# Tommy.net
KiCad netlist of a schematic drawn in EAGLE
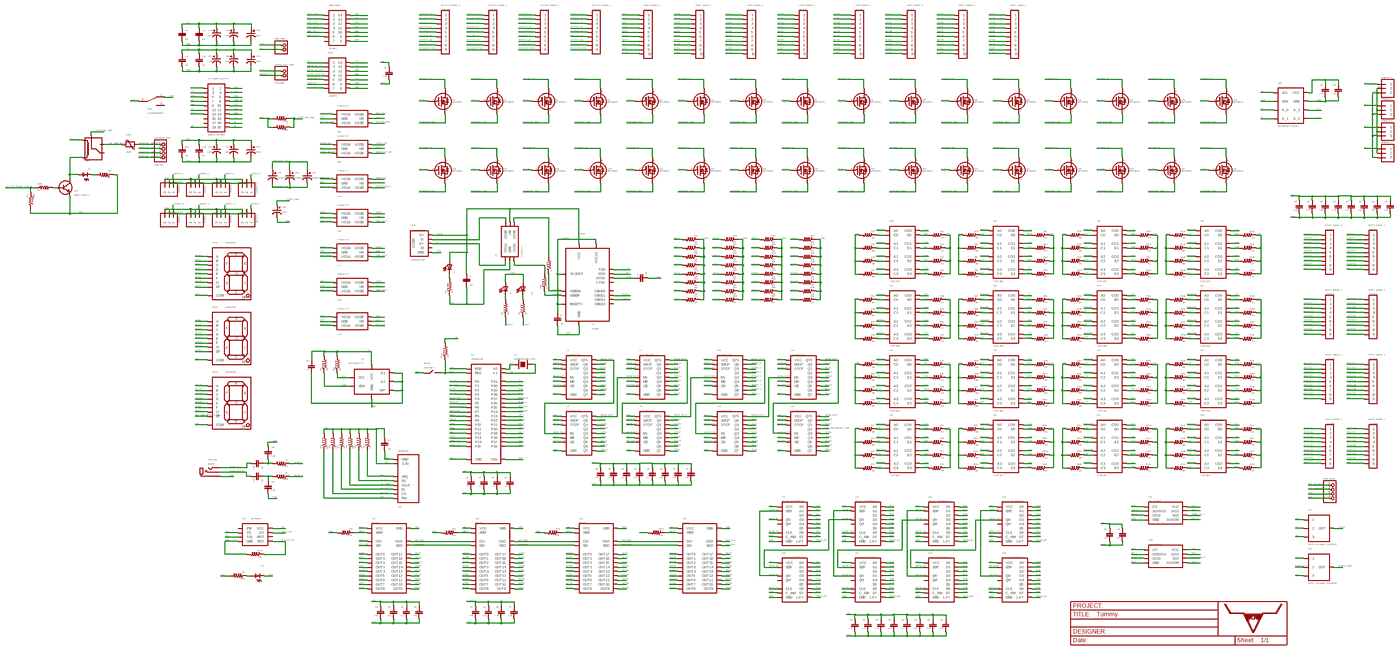
[diagram p0: schematic, sheet 1, overview]
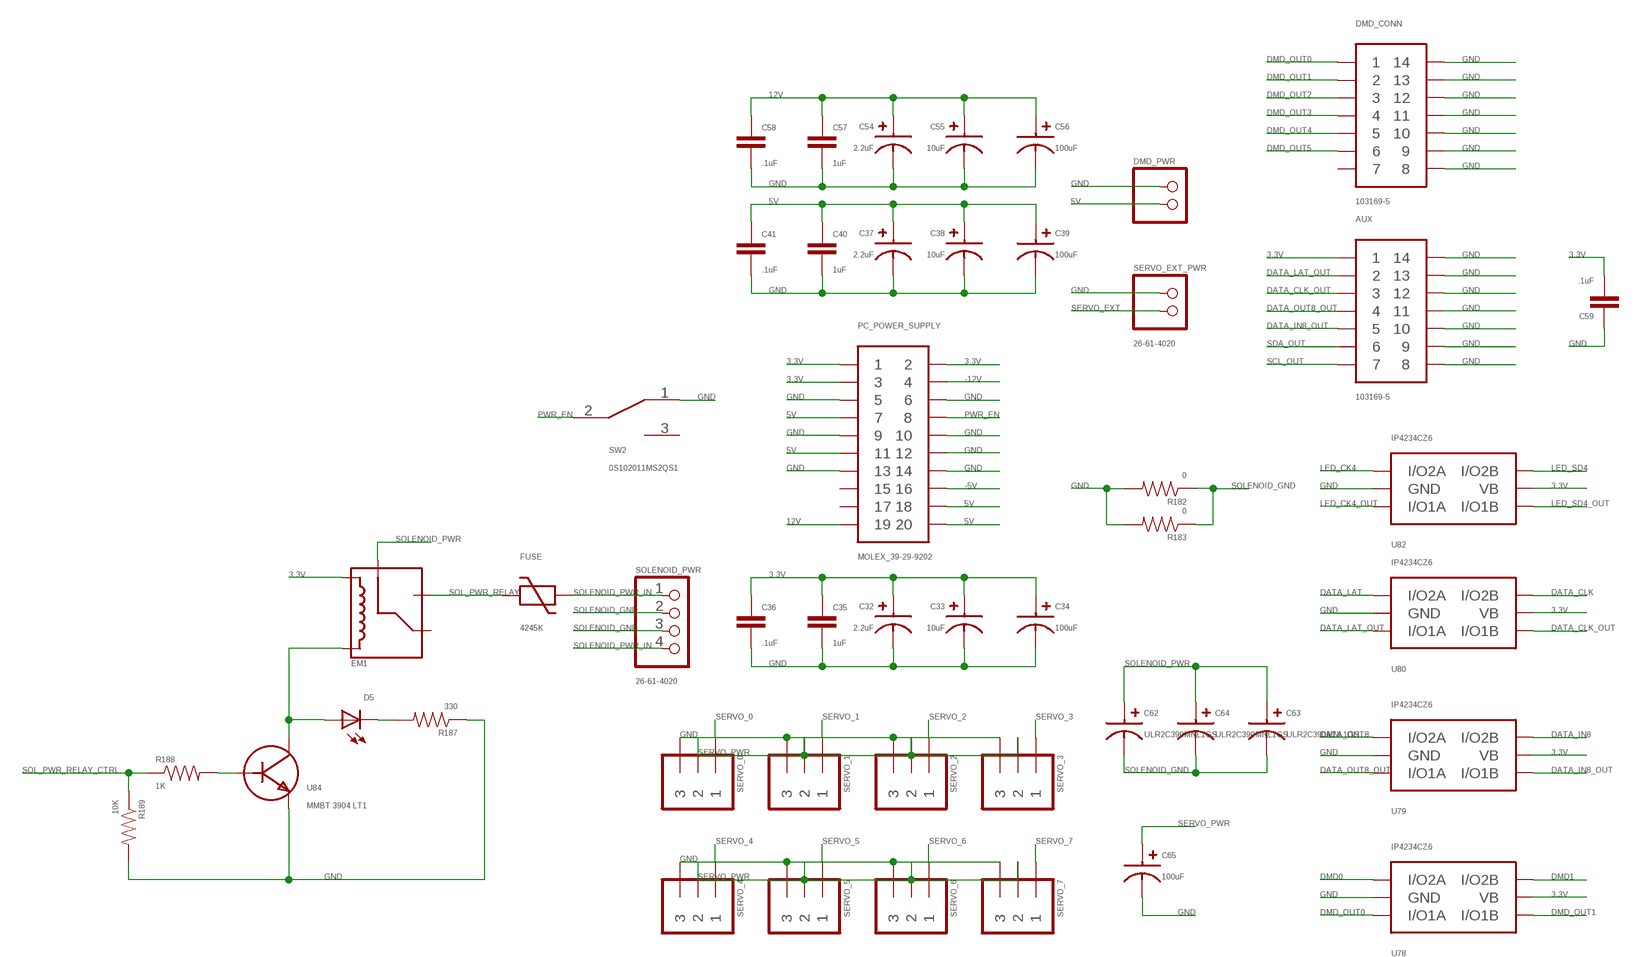
[diagram p1: schematic, sheet 1, part 1 of 9]
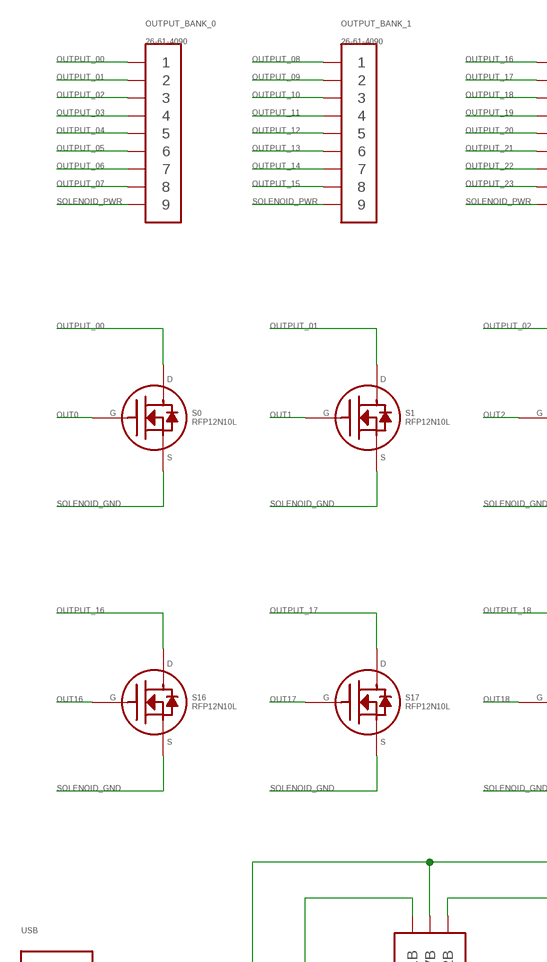
[diagram p2: schematic, sheet 1, part 2 of 9]
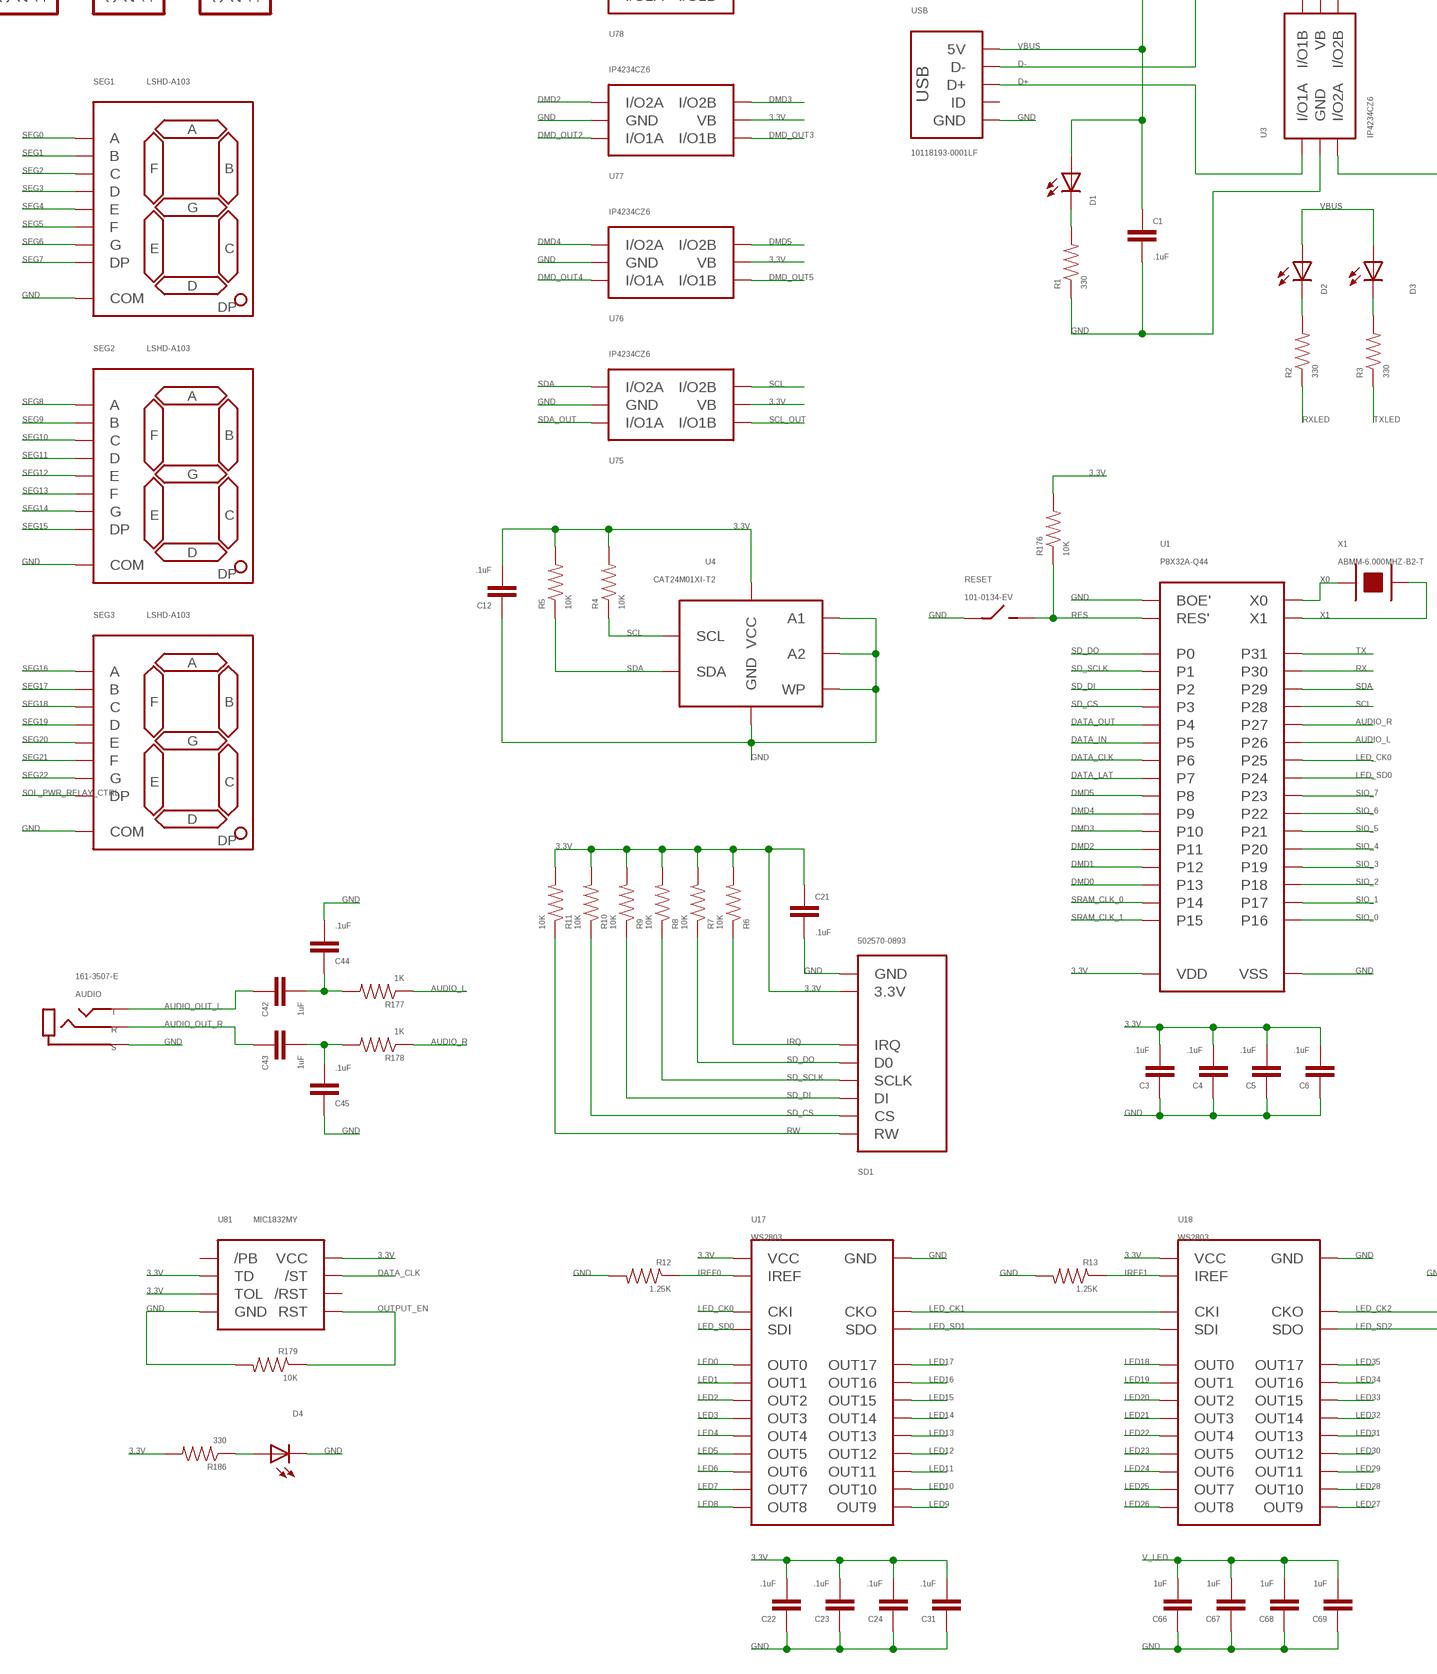
[diagram p3: schematic, sheet 1, part 3 of 9]
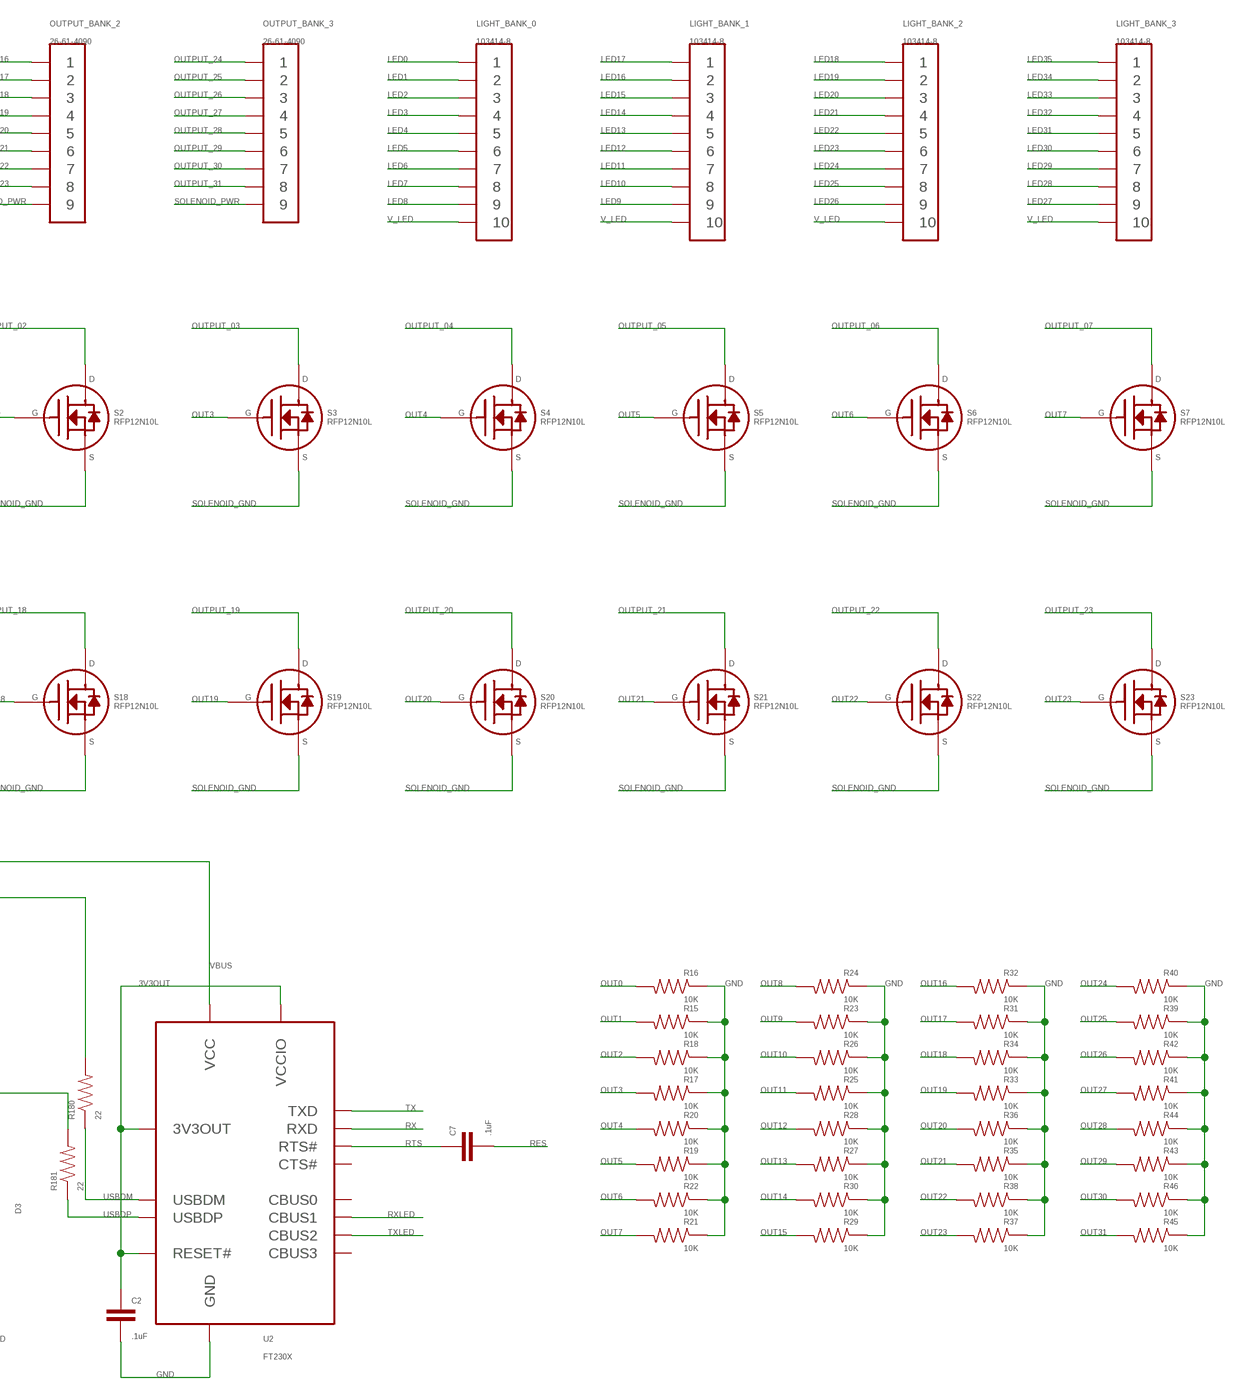
[diagram p4: schematic, sheet 1, part 4 of 9]
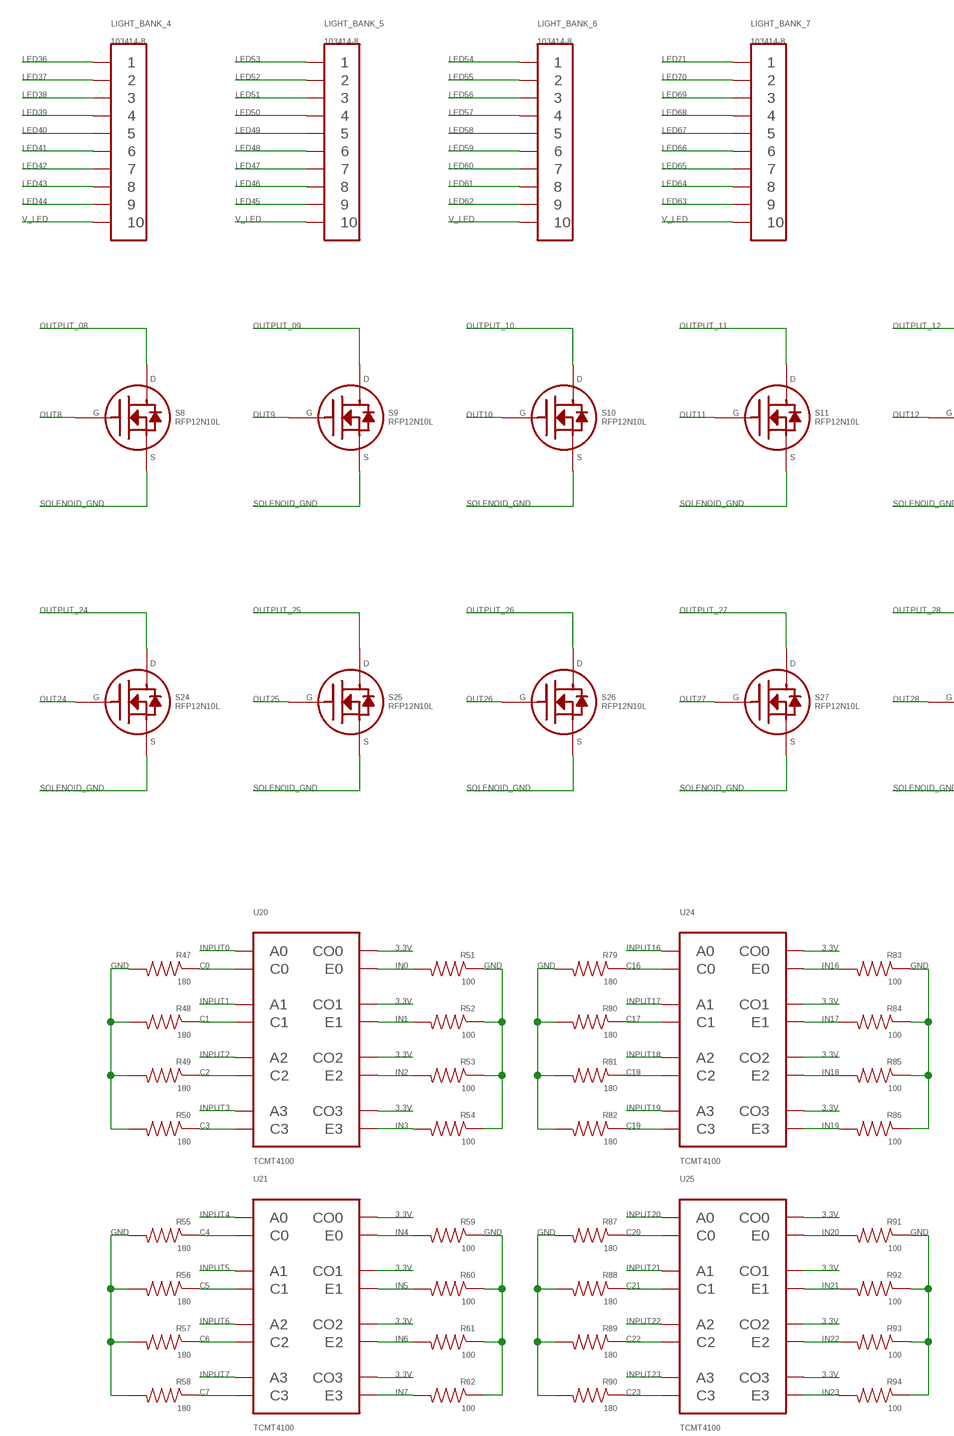
[diagram p5: schematic, sheet 1, part 5 of 9]
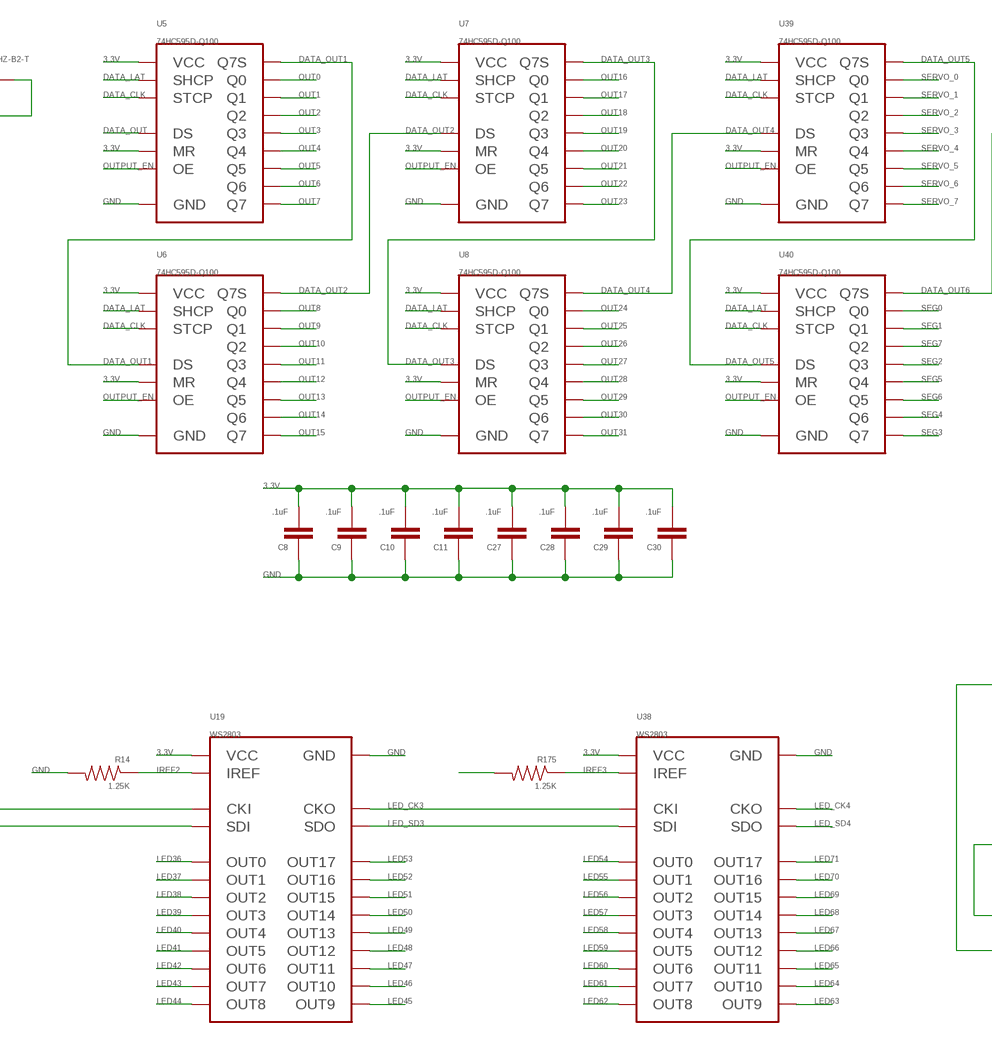
[diagram p6: schematic, sheet 1, part 6 of 9]
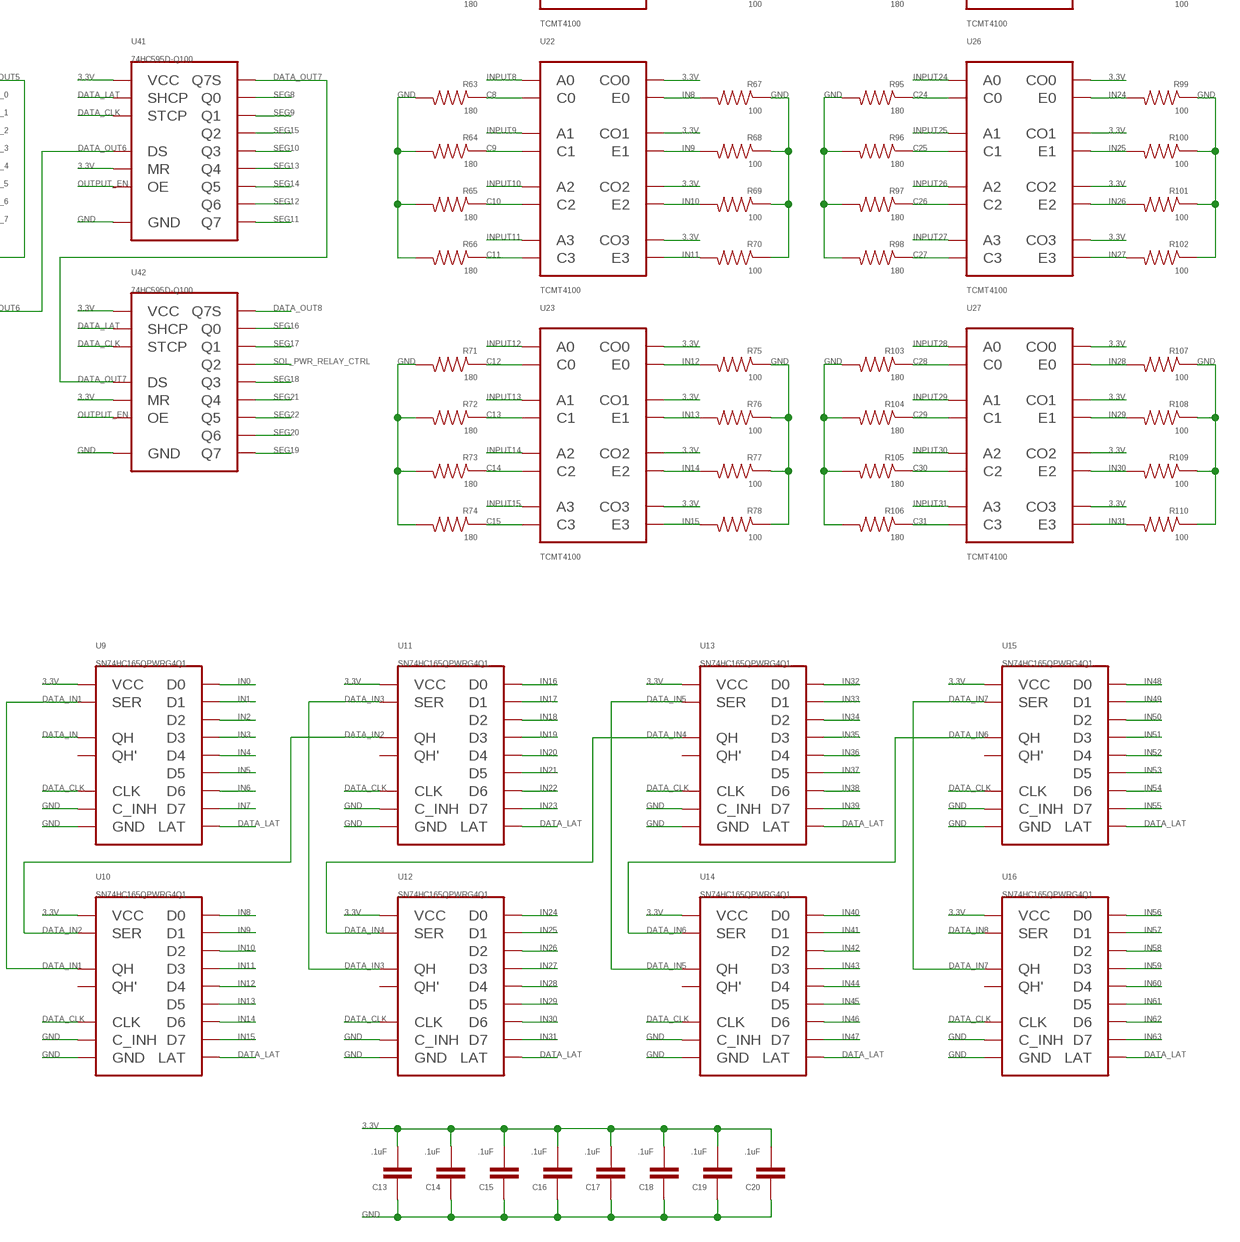
[diagram p7: schematic, sheet 1, part 7 of 9]
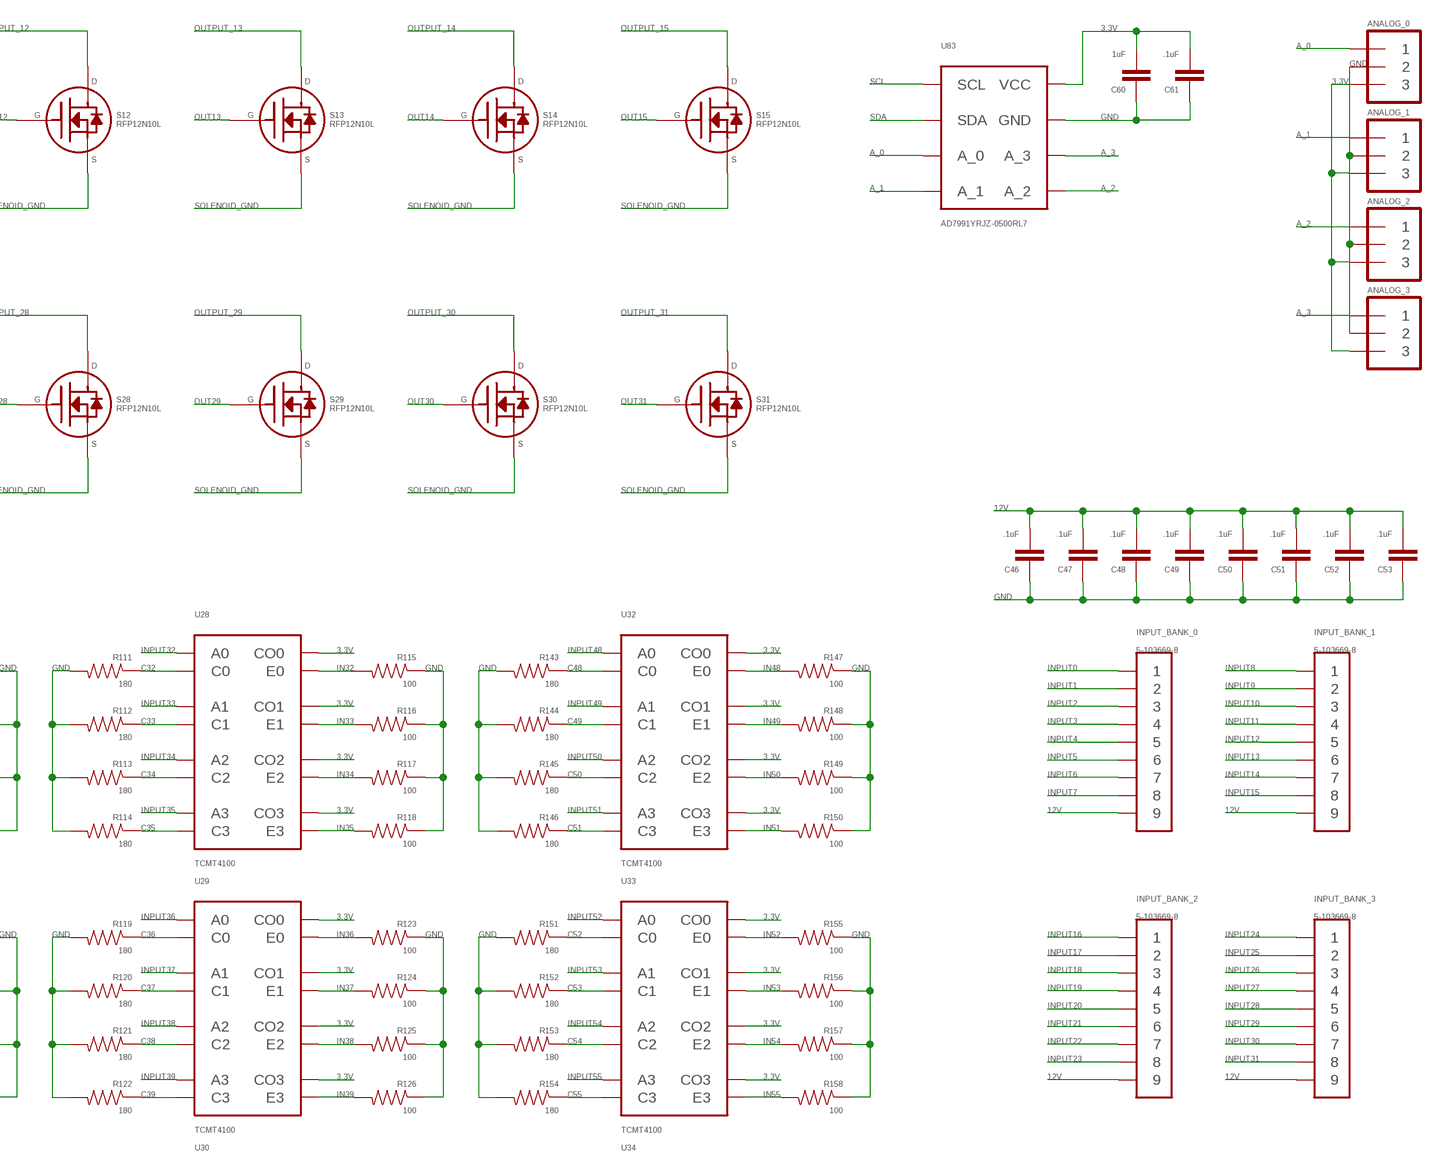
[diagram p8: schematic, sheet 1, part 8 of 9]
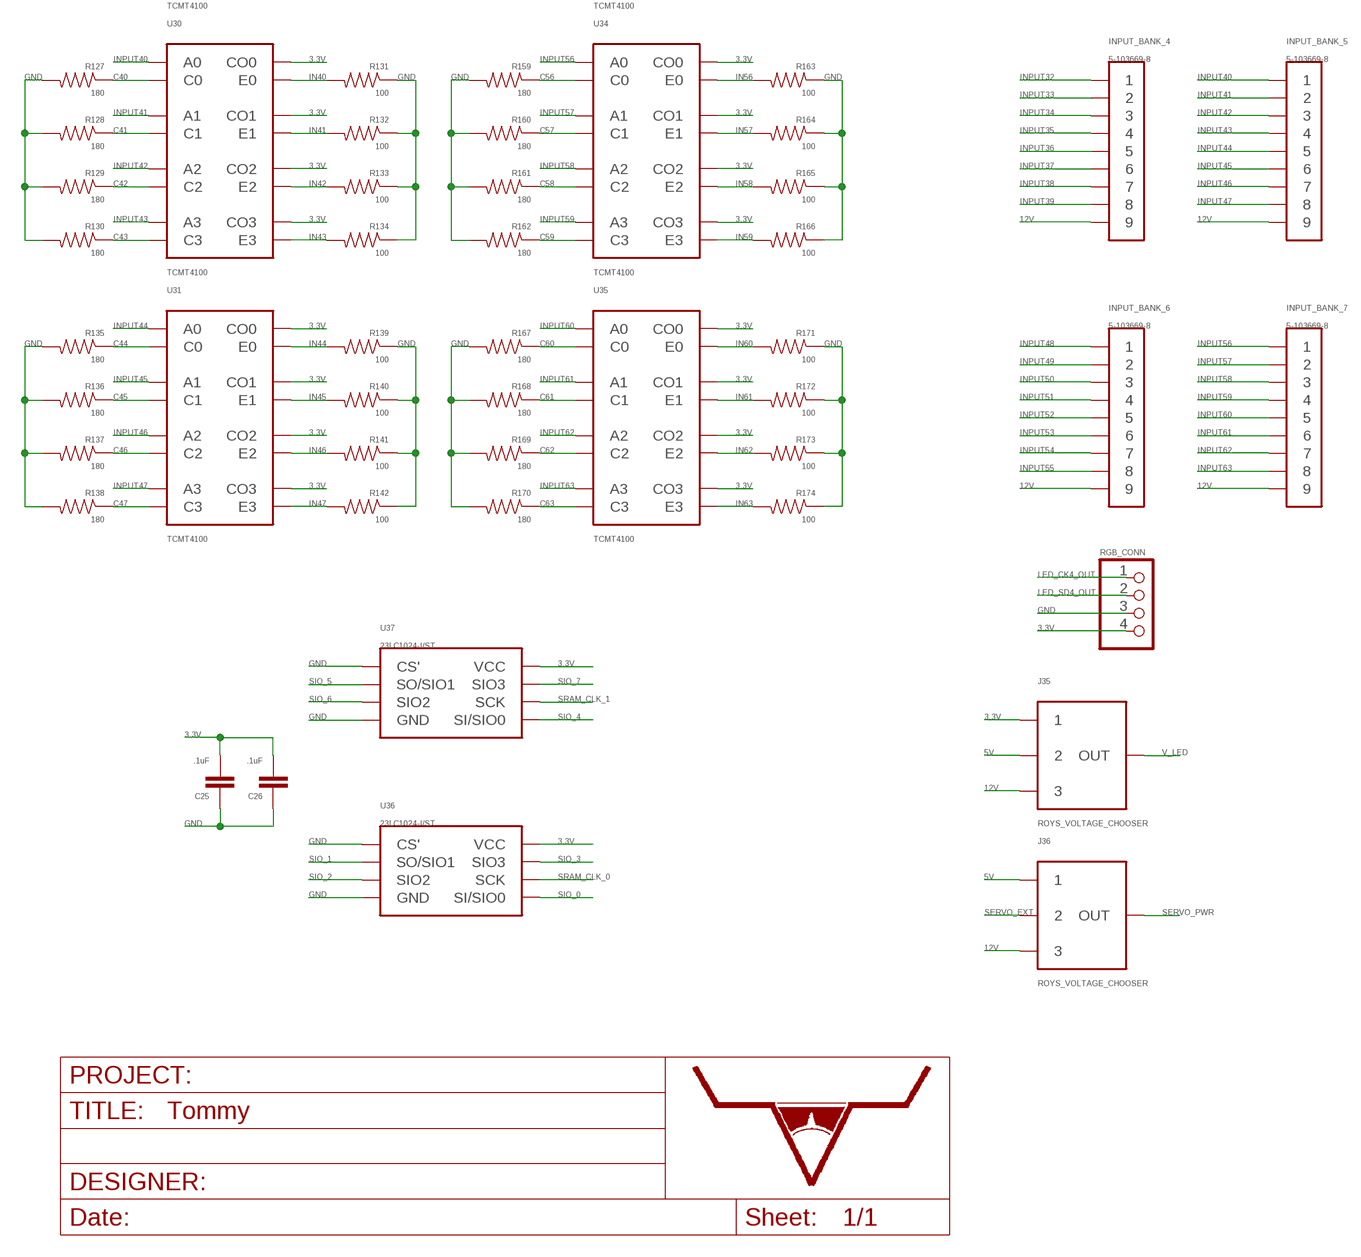
[diagram p9: schematic, sheet 1, part 9 of 9]

(export (version "E")
  (design (tool "Eeschema 10.0.6"))
  (components
    (comp (ref "ANALOG_0")
      (value "PH_1X03HEADER_PTH")
      (footprint "eagle-import:HEADER_01X03_PTH")
      (libsource (lib "eagle-import") (part "PH_1X03HEADER_PTH"))
    )
    (comp (ref "ANALOG_1")
      (value "PH_1X03HEADER_PTH")
      (footprint "eagle-import:HEADER_01X03_PTH")
      (libsource (lib "eagle-import") (part "PH_1X03HEADER_PTH"))
    )
    (comp (ref "ANALOG_2")
      (value "PH_1X03HEADER_PTH")
      (footprint "eagle-import:HEADER_01X03_PTH")
      (libsource (lib "eagle-import") (part "PH_1X03HEADER_PTH"))
    )
    (comp (ref "ANALOG_3")
      (value "PH_1X03HEADER_PTH")
      (footprint "eagle-import:HEADER_01X03_PTH")
      (libsource (lib "eagle-import") (part "PH_1X03HEADER_PTH"))
    )
    (comp (ref "AUDIO")
      (value "161-3507-E")
      (footprint "eagle-import:161-3507-E")
      (libsource (lib "eagle-import") (part "TRS_JACK161-3507-E"))
    )
    (comp (ref "AUX")
      (value "103169-5")
      (footprint "eagle-import:HEADER_02X07_PTH")
      (libsource (lib "eagle-import") (part "PH_2X07PTH"))
    )
    (comp (ref "C1")
      (value ".1uF")
      (footprint "eagle-import:0402")
      (libsource (lib "eagle-import") (part "CAPACITOR_NON_POLAR0402"))
    )
    (comp (ref "C2")
      (value ".1uF")
      (footprint "eagle-import:0402")
      (libsource (lib "eagle-import") (part "CAPACITOR_NON_POLAR0402"))
    )
    (comp (ref "C3")
      (value ".1uF")
      (footprint "eagle-import:0402")
      (libsource (lib "eagle-import") (part "CAPACITOR_NON_POLAR0402"))
    )
    (comp (ref "C4")
      (value ".1uF")
      (footprint "eagle-import:0402")
      (libsource (lib "eagle-import") (part "CAPACITOR_NON_POLAR0402"))
    )
    (comp (ref "C5")
      (value ".1uF")
      (footprint "eagle-import:0402")
      (libsource (lib "eagle-import") (part "CAPACITOR_NON_POLAR0402"))
    )
    (comp (ref "C6")
      (value ".1uF")
      (footprint "eagle-import:0402")
      (libsource (lib "eagle-import") (part "CAPACITOR_NON_POLAR0402"))
    )
    (comp (ref "C7")
      (value ".1uF")
      (footprint "eagle-import:0402")
      (libsource (lib "eagle-import") (part "CAPACITOR_NON_POLAR0402"))
    )
    (comp (ref "C8")
      (value ".1uF")
      (footprint "eagle-import:0402")
      (libsource (lib "eagle-import") (part "CAPACITOR_NON_POLAR0402"))
    )
    (comp (ref "C9")
      (value ".1uF")
      (footprint "eagle-import:0402")
      (libsource (lib "eagle-import") (part "CAPACITOR_NON_POLAR0402"))
    )
    (comp (ref "C10")
      (value ".1uF")
      (footprint "eagle-import:0402")
      (libsource (lib "eagle-import") (part "CAPACITOR_NON_POLAR0402"))
    )
    (comp (ref "C11")
      (value ".1uF")
      (footprint "eagle-import:0402")
      (libsource (lib "eagle-import") (part "CAPACITOR_NON_POLAR0402"))
    )
    (comp (ref "C12")
      (value ".1uF")
      (footprint "eagle-import:0402")
      (libsource (lib "eagle-import") (part "CAPACITOR_NON_POLAR0402"))
    )
    (comp (ref "C13")
      (value ".1uF")
      (footprint "eagle-import:0402")
      (libsource (lib "eagle-import") (part "CAPACITOR_NON_POLAR0402"))
    )
    (comp (ref "C14")
      (value ".1uF")
      (footprint "eagle-import:0402")
      (libsource (lib "eagle-import") (part "CAPACITOR_NON_POLAR0402"))
    )
    (comp (ref "C15")
      (value ".1uF")
      (footprint "eagle-import:0402")
      (libsource (lib "eagle-import") (part "CAPACITOR_NON_POLAR0402"))
    )
    (comp (ref "C16")
      (value ".1uF")
      (footprint "eagle-import:0402")
      (libsource (lib "eagle-import") (part "CAPACITOR_NON_POLAR0402"))
    )
    (comp (ref "C17")
      (value ".1uF")
      (footprint "eagle-import:0402")
      (libsource (lib "eagle-import") (part "CAPACITOR_NON_POLAR0402"))
    )
    (comp (ref "C18")
      (value ".1uF")
      (footprint "eagle-import:0402")
      (libsource (lib "eagle-import") (part "CAPACITOR_NON_POLAR0402"))
    )
    (comp (ref "C19")
      (value ".1uF")
      (footprint "eagle-import:0402")
      (libsource (lib "eagle-import") (part "CAPACITOR_NON_POLAR0402"))
    )
    (comp (ref "C20")
      (value ".1uF")
      (footprint "eagle-import:0402")
      (libsource (lib "eagle-import") (part "CAPACITOR_NON_POLAR0402"))
    )
    (comp (ref "C21")
      (value ".1uF")
      (footprint "eagle-import:0402")
      (libsource (lib "eagle-import") (part "CAPACITOR_NON_POLAR0402"))
    )
    (comp (ref "C22")
      (value ".1uF")
      (footprint "eagle-import:0402")
      (libsource (lib "eagle-import") (part "CAPACITOR_NON_POLAR0402"))
    )
    (comp (ref "C23")
      (value ".1uF")
      (footprint "eagle-import:0402")
      (libsource (lib "eagle-import") (part "CAPACITOR_NON_POLAR0402"))
    )
    (comp (ref "C24")
      (value ".1uF")
      (footprint "eagle-import:0402")
      (libsource (lib "eagle-import") (part "CAPACITOR_NON_POLAR0402"))
    )
    (comp (ref "C25")
      (value ".1uF")
      (footprint "eagle-import:0402")
      (libsource (lib "eagle-import") (part "CAPACITOR_NON_POLAR0402"))
    )
    (comp (ref "C26")
      (value ".1uF")
      (footprint "eagle-import:0402")
      (libsource (lib "eagle-import") (part "CAPACITOR_NON_POLAR0402"))
    )
    (comp (ref "C27")
      (value ".1uF")
      (footprint "eagle-import:0402")
      (libsource (lib "eagle-import") (part "CAPACITOR_NON_POLAR0402"))
    )
    (comp (ref "C28")
      (value ".1uF")
      (footprint "eagle-import:0402")
      (libsource (lib "eagle-import") (part "CAPACITOR_NON_POLAR0402"))
    )
    (comp (ref "C29")
      (value ".1uF")
      (footprint "eagle-import:0402")
      (libsource (lib "eagle-import") (part "CAPACITOR_NON_POLAR0402"))
    )
    (comp (ref "C30")
      (value ".1uF")
      (footprint "eagle-import:0402")
      (libsource (lib "eagle-import") (part "CAPACITOR_NON_POLAR0402"))
    )
    (comp (ref "C31")
      (value ".1uF")
      (footprint "eagle-import:0402")
      (libsource (lib "eagle-import") (part "CAPACITOR_NON_POLAR0402"))
    )
    (comp (ref "C32")
      (value "2.2uF")
      (footprint "eagle-import:1206_POLARIZED")
      (libsource (lib "eagle-import") (part "CAPACITOR_POLARIZED1206"))
    )
    (comp (ref "C33")
      (value "10uF")
      (footprint "eagle-import:1206_POLARIZED")
      (libsource (lib "eagle-import") (part "CAPACITOR_POLARIZED1206"))
    )
    (comp (ref "C34")
      (value "100uF")
      (footprint "eagle-import:6.3MM_CAP_SMD")
      (libsource (lib "eagle-import") (part "CAPACITOR_POLARIZED6.3MM_SMD"))
    )
    (comp (ref "C35")
      (value "1uF")
      (footprint "eagle-import:0402")
      (libsource (lib "eagle-import") (part "CAPACITOR_NON_POLAR0402"))
    )
    (comp (ref "C36")
      (value ".1uF")
      (footprint "eagle-import:0402")
      (libsource (lib "eagle-import") (part "CAPACITOR_NON_POLAR0402"))
    )
    (comp (ref "C37")
      (value "2.2uF")
      (footprint "eagle-import:1206_POLARIZED")
      (libsource (lib "eagle-import") (part "CAPACITOR_POLARIZED1206"))
    )
    (comp (ref "C38")
      (value "10uF")
      (footprint "eagle-import:1206_POLARIZED")
      (libsource (lib "eagle-import") (part "CAPACITOR_POLARIZED1206"))
    )
    (comp (ref "C39")
      (value "100uF")
      (footprint "eagle-import:6.3MM_CAP_SMD")
      (libsource (lib "eagle-import") (part "CAPACITOR_POLARIZED6.3MM_SMD"))
    )
    (comp (ref "C40")
      (value "1uF")
      (footprint "eagle-import:0402")
      (libsource (lib "eagle-import") (part "CAPACITOR_NON_POLAR0402"))
    )
    (comp (ref "C41")
      (value ".1uF")
      (footprint "eagle-import:0402")
      (libsource (lib "eagle-import") (part "CAPACITOR_NON_POLAR0402"))
    )
    (comp (ref "C42")
      (value "1uF")
      (footprint "eagle-import:0402")
      (libsource (lib "eagle-import") (part "CAPACITOR_NON_POLAR0402"))
    )
    (comp (ref "C43")
      (value "1uF")
      (footprint "eagle-import:0402")
      (libsource (lib "eagle-import") (part "CAPACITOR_NON_POLAR0402"))
    )
    (comp (ref "C44")
      (value ".1uF")
      (footprint "eagle-import:0402")
      (libsource (lib "eagle-import") (part "CAPACITOR_NON_POLAR0402"))
    )
    (comp (ref "C45")
      (value ".1uF")
      (footprint "eagle-import:0402")
      (libsource (lib "eagle-import") (part "CAPACITOR_NON_POLAR0402"))
    )
    (comp (ref "C46")
      (value ".1uF")
      (footprint "eagle-import:0402")
      (libsource (lib "eagle-import") (part "CAPACITOR_NON_POLAR0402"))
    )
    (comp (ref "C47")
      (value ".1uF")
      (footprint "eagle-import:0402")
      (libsource (lib "eagle-import") (part "CAPACITOR_NON_POLAR0402"))
    )
    (comp (ref "C48")
      (value ".1uF")
      (footprint "eagle-import:0402")
      (libsource (lib "eagle-import") (part "CAPACITOR_NON_POLAR0402"))
    )
    (comp (ref "C49")
      (value ".1uF")
      (footprint "eagle-import:0402")
      (libsource (lib "eagle-import") (part "CAPACITOR_NON_POLAR0402"))
    )
    (comp (ref "C50")
      (value ".1uF")
      (footprint "eagle-import:0402")
      (libsource (lib "eagle-import") (part "CAPACITOR_NON_POLAR0402"))
    )
    (comp (ref "C51")
      (value ".1uF")
      (footprint "eagle-import:0402")
      (libsource (lib "eagle-import") (part "CAPACITOR_NON_POLAR0402"))
    )
    (comp (ref "C52")
      (value ".1uF")
      (footprint "eagle-import:0402")
      (libsource (lib "eagle-import") (part "CAPACITOR_NON_POLAR0402"))
    )
    (comp (ref "C53")
      (value ".1uF")
      (footprint "eagle-import:0402")
      (libsource (lib "eagle-import") (part "CAPACITOR_NON_POLAR0402"))
    )
    (comp (ref "C54")
      (value "2.2uF")
      (footprint "eagle-import:1206_POLARIZED")
      (libsource (lib "eagle-import") (part "CAPACITOR_POLARIZED1206"))
    )
    (comp (ref "C55")
      (value "10uF")
      (footprint "eagle-import:1206_POLARIZED")
      (libsource (lib "eagle-import") (part "CAPACITOR_POLARIZED1206"))
    )
    (comp (ref "C56")
      (value "100uF")
      (footprint "eagle-import:6.3MM_CAP_SMD")
      (libsource (lib "eagle-import") (part "CAPACITOR_POLARIZED6.3MM_SMD"))
    )
    (comp (ref "C57")
      (value "1uF")
      (footprint "eagle-import:0402")
      (libsource (lib "eagle-import") (part "CAPACITOR_NON_POLAR0402"))
    )
    (comp (ref "C58")
      (value ".1uF")
      (footprint "eagle-import:0402")
      (libsource (lib "eagle-import") (part "CAPACITOR_NON_POLAR0402"))
    )
    (comp (ref "C59")
      (value ".1uF")
      (footprint "eagle-import:0402")
      (libsource (lib "eagle-import") (part "CAPACITOR_NON_POLAR0402"))
    )
    (comp (ref "C60")
      (value "1uF")
      (footprint "eagle-import:0402")
      (libsource (lib "eagle-import") (part "CAPACITOR_NON_POLAR0402"))
    )
    (comp (ref "C61")
      (value ".1uF")
      (footprint "eagle-import:0402")
      (libsource (lib "eagle-import") (part "CAPACITOR_NON_POLAR0402"))
    )
    (comp (ref "C62")
      (value "ULR2C390MNL1GS")
      (footprint "eagle-import:EEH-ZA1V271P")
      (libsource (lib "eagle-import") (part "CAPACITOR_POLARIZEDEEH-ZA1V271P"))
    )
    (comp (ref "C63")
      (value "ULR2C390MNL1GS")
      (footprint "eagle-import:EEH-ZA1V271P")
      (libsource (lib "eagle-import") (part "CAPACITOR_POLARIZEDEEH-ZA1V271P"))
    )
    (comp (ref "C64")
      (value "ULR2C390MNL1GS")
      (footprint "eagle-import:EEH-ZA1V271P")
      (libsource (lib "eagle-import") (part "CAPACITOR_POLARIZEDEEH-ZA1V271P"))
    )
    (comp (ref "C65")
      (value "100uF")
      (footprint "eagle-import:6.3MM_CAP_SMD")
      (libsource (lib "eagle-import") (part "CAPACITOR_POLARIZED6.3MM_SMD"))
    )
    (comp (ref "C66")
      (value "1uF")
      (footprint "eagle-import:0402")
      (libsource (lib "eagle-import") (part "CAPACITOR_NON_POLAR0402"))
    )
    (comp (ref "C67")
      (value "1uF")
      (footprint "eagle-import:0402")
      (libsource (lib "eagle-import") (part "CAPACITOR_NON_POLAR0402"))
    )
    (comp (ref "C68")
      (value "1uF")
      (footprint "eagle-import:0402")
      (libsource (lib "eagle-import") (part "CAPACITOR_NON_POLAR0402"))
    )
    (comp (ref "C69")
      (value "1uF")
      (footprint "eagle-import:0402")
      (libsource (lib "eagle-import") (part "CAPACITOR_NON_POLAR0402"))
    )
    (comp (ref "D1")
      (value "LEDSML0603")
      (footprint "eagle-import:SML0603")
      (libsource (lib "eagle-import") (part "LEDSML0603"))
    )
    (comp (ref "D2")
      (value "LEDSML0603")
      (footprint "eagle-import:SML0603")
      (libsource (lib "eagle-import") (part "LEDSML0603"))
    )
    (comp (ref "D3")
      (value "LEDSML0603")
      (footprint "eagle-import:SML0603")
      (libsource (lib "eagle-import") (part "LEDSML0603"))
    )
    (comp (ref "D4")
      (value "LEDSML0603")
      (footprint "eagle-import:SML0603")
      (libsource (lib "eagle-import") (part "LEDSML0603"))
    )
    (comp (ref "D5")
      (value "LEDSML0603")
      (footprint "eagle-import:SML0603")
      (libsource (lib "eagle-import") (part "LEDSML0603"))
    )
    (comp (ref "DMD_CONN")
      (value "103169-5")
      (footprint "eagle-import:HEADER_02X07_PTH")
      (libsource (lib "eagle-import") (part "PH_2X07PTH"))
    )
    (comp (ref "DMD_PWR")
      (value "PH_1X02MOLEX_26-61-4020")
      (footprint "eagle-import:MOLEX_KK_2")
      (libsource (lib "eagle-import") (part "PH_1X02MOLEX_26-61-4020"))
    )
    (comp (ref "EM1")
      (value "SPDT_RELAYG5LA")
      (footprint "eagle-import:G5LA_PCBRELAY_SPDT")
      (libsource (lib "eagle-import") (part "SPDT_RELAYG5LA"))
    )
    (comp (ref "FUSE")
      (value "4245K")
      (footprint "eagle-import:4245K")
      (libsource (lib "eagle-import") (part "PTC_FUSE4245K"))
    )
    (comp (ref "INPUT_BANK_0")
      (value "5-103669-8")
      (footprint "eagle-import:HEADER_01X09_PTH")
      (libsource (lib "eagle-import") (part "PH_1X09PTH"))
    )
    (comp (ref "INPUT_BANK_1")
      (value "5-103669-8")
      (footprint "eagle-import:HEADER_01X09_PTH")
      (libsource (lib "eagle-import") (part "PH_1X09PTH"))
    )
    (comp (ref "INPUT_BANK_2")
      (value "5-103669-8")
      (footprint "eagle-import:HEADER_01X09_PTH")
      (libsource (lib "eagle-import") (part "PH_1X09PTH"))
    )
    (comp (ref "INPUT_BANK_3")
      (value "5-103669-8")
      (footprint "eagle-import:HEADER_01X09_PTH")
      (libsource (lib "eagle-import") (part "PH_1X09PTH"))
    )
    (comp (ref "INPUT_BANK_4")
      (value "5-103669-8")
      (footprint "eagle-import:HEADER_01X09_PTH")
      (libsource (lib "eagle-import") (part "PH_1X09PTH"))
    )
    (comp (ref "INPUT_BANK_5")
      (value "5-103669-8")
      (footprint "eagle-import:HEADER_01X09_PTH")
      (libsource (lib "eagle-import") (part "PH_1X09PTH"))
    )
    (comp (ref "INPUT_BANK_6")
      (value "5-103669-8")
      (footprint "eagle-import:HEADER_01X09_PTH")
      (libsource (lib "eagle-import") (part "PH_1X09PTH"))
    )
    (comp (ref "INPUT_BANK_7")
      (value "5-103669-8")
      (footprint "eagle-import:HEADER_01X09_PTH")
      (libsource (lib "eagle-import") (part "PH_1X09PTH"))
    )
    (comp (ref "J35")
      (value "ROYS_VOLTAGE_CHOOSER")
      (footprint "eagle-import:ROYS_VOLTAGE_CHOOSER")
      (libsource (lib "eagle-import") (part "ROYS_VOLTAGE_CHOOSER"))
    )
    (comp (ref "J36")
      (value "ROYS_VOLTAGE_CHOOSER")
      (footprint "eagle-import:ROYS_VOLTAGE_CHOOSER")
      (libsource (lib "eagle-import") (part "ROYS_VOLTAGE_CHOOSER"))
    )
    (comp (ref "LIGHT_BANK_0")
      (value "103414-8")
      (footprint "eagle-import:HEADER_01X10_PTH")
      (libsource (lib "eagle-import") (part "PH_1X10PTH"))
    )
    (comp (ref "LIGHT_BANK_1")
      (value "103414-8")
      (footprint "eagle-import:HEADER_01X10_PTH")
      (libsource (lib "eagle-import") (part "PH_1X10PTH"))
    )
    (comp (ref "LIGHT_BANK_2")
      (value "103414-8")
      (footprint "eagle-import:HEADER_01X10_PTH")
      (libsource (lib "eagle-import") (part "PH_1X10PTH"))
    )
    (comp (ref "LIGHT_BANK_3")
      (value "103414-8")
      (footprint "eagle-import:HEADER_01X10_PTH")
      (libsource (lib "eagle-import") (part "PH_1X10PTH"))
    )
    (comp (ref "LIGHT_BANK_4")
      (value "103414-8")
      (footprint "eagle-import:HEADER_01X10_PTH")
      (libsource (lib "eagle-import") (part "PH_1X10PTH"))
    )
    (comp (ref "LIGHT_BANK_5")
      (value "103414-8")
      (footprint "eagle-import:HEADER_01X10_PTH")
      (libsource (lib "eagle-import") (part "PH_1X10PTH"))
    )
    (comp (ref "LIGHT_BANK_6")
      (value "103414-8")
      (footprint "eagle-import:HEADER_01X10_PTH")
      (libsource (lib "eagle-import") (part "PH_1X10PTH"))
    )
    (comp (ref "LIGHT_BANK_7")
      (value "103414-8")
      (footprint "eagle-import:HEADER_01X10_PTH")
      (libsource (lib "eagle-import") (part "PH_1X10PTH"))
    )
    (comp (ref "OUTPUT_BANK_0")
      (value "26-61-4090")
      (footprint "eagle-import:MOLEX_KK_9")
      (libsource (lib "eagle-import") (part "PH_1X09MOLEX_KK_9"))
    )
    (comp (ref "OUTPUT_BANK_1")
      (value "26-61-4090")
      (footprint "eagle-import:MOLEX_KK_9")
      (libsource (lib "eagle-import") (part "PH_1X09MOLEX_KK_9"))
    )
    (comp (ref "OUTPUT_BANK_2")
      (value "26-61-4090")
      (footprint "eagle-import:MOLEX_KK_9")
      (libsource (lib "eagle-import") (part "PH_1X09MOLEX_KK_9"))
    )
    (comp (ref "OUTPUT_BANK_3")
      (value "26-61-4090")
      (footprint "eagle-import:MOLEX_KK_9")
      (libsource (lib "eagle-import") (part "PH_1X09MOLEX_KK_9"))
    )
    (comp (ref "PC_POWER_SUPPLY")
      (value "MOLEX_39-29-9202")
      (footprint "eagle-import:MOLEX_39-29-9202")
      (libsource (lib "eagle-import") (part "PH_2X10MOLEX_39-29-9202"))
    )
    (comp (ref "R1")
      (value "330")
      (footprint "eagle-import:0402")
      (libsource (lib "eagle-import") (part "RESISTOR0402"))
    )
    (comp (ref "R2")
      (value "330")
      (footprint "eagle-import:0402")
      (libsource (lib "eagle-import") (part "RESISTOR0402"))
    )
    (comp (ref "R3")
      (value "330")
      (footprint "eagle-import:0402")
      (libsource (lib "eagle-import") (part "RESISTOR0402"))
    )
    (comp (ref "R4")
      (value "10K")
      (footprint "eagle-import:0402")
      (libsource (lib "eagle-import") (part "RESISTOR0402"))
    )
    (comp (ref "R5")
      (value "10K")
      (footprint "eagle-import:0402")
      (libsource (lib "eagle-import") (part "RESISTOR0402"))
    )
    (comp (ref "R6")
      (value "10K")
      (footprint "eagle-import:0402")
      (libsource (lib "eagle-import") (part "RESISTOR0402"))
    )
    (comp (ref "R7")
      (value "10K")
      (footprint "eagle-import:0402")
      (libsource (lib "eagle-import") (part "RESISTOR0402"))
    )
    (comp (ref "R8")
      (value "10K")
      (footprint "eagle-import:0402")
      (libsource (lib "eagle-import") (part "RESISTOR0402"))
    )
    (comp (ref "R9")
      (value "10K")
      (footprint "eagle-import:0402")
      (libsource (lib "eagle-import") (part "RESISTOR0402"))
    )
    (comp (ref "R10")
      (value "10K")
      (footprint "eagle-import:0402")
      (libsource (lib "eagle-import") (part "RESISTOR0402"))
    )
    (comp (ref "R11")
      (value "10K")
      (footprint "eagle-import:0402")
      (libsource (lib "eagle-import") (part "RESISTOR0402"))
    )
    (comp (ref "R12")
      (value "1.25K")
      (footprint "eagle-import:0402")
      (libsource (lib "eagle-import") (part "RESISTOR0402"))
    )
    (comp (ref "R13")
      (value "1.25K")
      (footprint "eagle-import:0402")
      (libsource (lib "eagle-import") (part "RESISTOR0402"))
    )
    (comp (ref "R14")
      (value "1.25K")
      (footprint "eagle-import:0402")
      (libsource (lib "eagle-import") (part "RESISTOR0402"))
    )
    (comp (ref "R15")
      (value "10K")
      (footprint "eagle-import:0402")
      (libsource (lib "eagle-import") (part "RESISTOR0402"))
    )
    (comp (ref "R16")
      (value "10K")
      (footprint "eagle-import:0402")
      (libsource (lib "eagle-import") (part "RESISTOR0402"))
    )
    (comp (ref "R17")
      (value "10K")
      (footprint "eagle-import:0402")
      (libsource (lib "eagle-import") (part "RESISTOR0402"))
    )
    (comp (ref "R18")
      (value "10K")
      (footprint "eagle-import:0402")
      (libsource (lib "eagle-import") (part "RESISTOR0402"))
    )
    (comp (ref "R19")
      (value "10K")
      (footprint "eagle-import:0402")
      (libsource (lib "eagle-import") (part "RESISTOR0402"))
    )
    (comp (ref "R20")
      (value "10K")
      (footprint "eagle-import:0402")
      (libsource (lib "eagle-import") (part "RESISTOR0402"))
    )
    (comp (ref "R21")
      (value "10K")
      (footprint "eagle-import:0402")
      (libsource (lib "eagle-import") (part "RESISTOR0402"))
    )
    (comp (ref "R22")
      (value "10K")
      (footprint "eagle-import:0402")
      (libsource (lib "eagle-import") (part "RESISTOR0402"))
    )
    (comp (ref "R23")
      (value "10K")
      (footprint "eagle-import:0402")
      (libsource (lib "eagle-import") (part "RESISTOR0402"))
    )
    (comp (ref "R24")
      (value "10K")
      (footprint "eagle-import:0402")
      (libsource (lib "eagle-import") (part "RESISTOR0402"))
    )
    (comp (ref "R25")
      (value "10K")
      (footprint "eagle-import:0402")
      (libsource (lib "eagle-import") (part "RESISTOR0402"))
    )
    (comp (ref "R26")
      (value "10K")
      (footprint "eagle-import:0402")
      (libsource (lib "eagle-import") (part "RESISTOR0402"))
    )
    (comp (ref "R27")
      (value "10K")
      (footprint "eagle-import:0402")
      (libsource (lib "eagle-import") (part "RESISTOR0402"))
    )
    (comp (ref "R28")
      (value "10K")
      (footprint "eagle-import:0402")
      (libsource (lib "eagle-import") (part "RESISTOR0402"))
    )
    (comp (ref "R29")
      (value "10K")
      (footprint "eagle-import:0402")
      (libsource (lib "eagle-import") (part "RESISTOR0402"))
    )
    (comp (ref "R30")
      (value "10K")
      (footprint "eagle-import:0402")
      (libsource (lib "eagle-import") (part "RESISTOR0402"))
    )
    (comp (ref "R31")
      (value "10K")
      (footprint "eagle-import:0402")
      (libsource (lib "eagle-import") (part "RESISTOR0402"))
    )
    (comp (ref "R32")
      (value "10K")
      (footprint "eagle-import:0402")
      (libsource (lib "eagle-import") (part "RESISTOR0402"))
    )
    (comp (ref "R33")
      (value "10K")
      (footprint "eagle-import:0402")
      (libsource (lib "eagle-import") (part "RESISTOR0402"))
    )
    (comp (ref "R34")
      (value "10K")
      (footprint "eagle-import:0402")
      (libsource (lib "eagle-import") (part "RESISTOR0402"))
    )
    (comp (ref "R35")
      (value "10K")
      (footprint "eagle-import:0402")
      (libsource (lib "eagle-import") (part "RESISTOR0402"))
    )
    (comp (ref "R36")
      (value "10K")
      (footprint "eagle-import:0402")
      (libsource (lib "eagle-import") (part "RESISTOR0402"))
    )
    (comp (ref "R37")
      (value "10K")
      (footprint "eagle-import:0402")
      (libsource (lib "eagle-import") (part "RESISTOR0402"))
    )
    (comp (ref "R38")
      (value "10K")
      (footprint "eagle-import:0402")
      (libsource (lib "eagle-import") (part "RESISTOR0402"))
    )
    (comp (ref "R39")
      (value "10K")
      (footprint "eagle-import:0402")
      (libsource (lib "eagle-import") (part "RESISTOR0402"))
    )
    (comp (ref "R40")
      (value "10K")
      (footprint "eagle-import:0402")
      (libsource (lib "eagle-import") (part "RESISTOR0402"))
    )
    (comp (ref "R41")
      (value "10K")
      (footprint "eagle-import:0402")
      (libsource (lib "eagle-import") (part "RESISTOR0402"))
    )
    (comp (ref "R42")
      (value "10K")
      (footprint "eagle-import:0402")
      (libsource (lib "eagle-import") (part "RESISTOR0402"))
    )
    (comp (ref "R43")
      (value "10K")
      (footprint "eagle-import:0402")
      (libsource (lib "eagle-import") (part "RESISTOR0402"))
    )
    (comp (ref "R44")
      (value "10K")
      (footprint "eagle-import:0402")
      (libsource (lib "eagle-import") (part "RESISTOR0402"))
    )
    (comp (ref "R45")
      (value "10K")
      (footprint "eagle-import:0402")
      (libsource (lib "eagle-import") (part "RESISTOR0402"))
    )
    (comp (ref "R46")
      (value "10K")
      (footprint "eagle-import:0402")
      (libsource (lib "eagle-import") (part "RESISTOR0402"))
    )
    (comp (ref "R47")
      (value "180")
      (footprint "eagle-import:0402")
      (libsource (lib "eagle-import") (part "RESISTOR0402"))
    )
    (comp (ref "R48")
      (value "180")
      (footprint "eagle-import:0402")
      (libsource (lib "eagle-import") (part "RESISTOR0402"))
    )
    (comp (ref "R49")
      (value "180")
      (footprint "eagle-import:0402")
      (libsource (lib "eagle-import") (part "RESISTOR0402"))
    )
    (comp (ref "R50")
      (value "180")
      (footprint "eagle-import:0402")
      (libsource (lib "eagle-import") (part "RESISTOR0402"))
    )
    (comp (ref "R51")
      (value "100")
      (footprint "eagle-import:0402")
      (libsource (lib "eagle-import") (part "RESISTOR0402"))
    )
    (comp (ref "R52")
      (value "100")
      (footprint "eagle-import:0402")
      (libsource (lib "eagle-import") (part "RESISTOR0402"))
    )
    (comp (ref "R53")
      (value "100")
      (footprint "eagle-import:0402")
      (libsource (lib "eagle-import") (part "RESISTOR0402"))
    )
    (comp (ref "R54")
      (value "100")
      (footprint "eagle-import:0402")
      (libsource (lib "eagle-import") (part "RESISTOR0402"))
    )
    (comp (ref "R55")
      (value "180")
      (footprint "eagle-import:0402")
      (libsource (lib "eagle-import") (part "RESISTOR0402"))
    )
    (comp (ref "R56")
      (value "180")
      (footprint "eagle-import:0402")
      (libsource (lib "eagle-import") (part "RESISTOR0402"))
    )
    (comp (ref "R57")
      (value "180")
      (footprint "eagle-import:0402")
      (libsource (lib "eagle-import") (part "RESISTOR0402"))
    )
    (comp (ref "R58")
      (value "180")
      (footprint "eagle-import:0402")
      (libsource (lib "eagle-import") (part "RESISTOR0402"))
    )
    (comp (ref "R59")
      (value "100")
      (footprint "eagle-import:0402")
      (libsource (lib "eagle-import") (part "RESISTOR0402"))
    )
    (comp (ref "R60")
      (value "100")
      (footprint "eagle-import:0402")
      (libsource (lib "eagle-import") (part "RESISTOR0402"))
    )
    (comp (ref "R61")
      (value "100")
      (footprint "eagle-import:0402")
      (libsource (lib "eagle-import") (part "RESISTOR0402"))
    )
    (comp (ref "R62")
      (value "100")
      (footprint "eagle-import:0402")
      (libsource (lib "eagle-import") (part "RESISTOR0402"))
    )
    (comp (ref "R63")
      (value "180")
      (footprint "eagle-import:0402")
      (libsource (lib "eagle-import") (part "RESISTOR0402"))
    )
    (comp (ref "R64")
      (value "180")
      (footprint "eagle-import:0402")
      (libsource (lib "eagle-import") (part "RESISTOR0402"))
    )
    (comp (ref "R65")
      (value "180")
      (footprint "eagle-import:0402")
      (libsource (lib "eagle-import") (part "RESISTOR0402"))
    )
    (comp (ref "R66")
      (value "180")
      (footprint "eagle-import:0402")
      (libsource (lib "eagle-import") (part "RESISTOR0402"))
    )
    (comp (ref "R67")
      (value "100")
      (footprint "eagle-import:0402")
      (libsource (lib "eagle-import") (part "RESISTOR0402"))
    )
    (comp (ref "R68")
      (value "100")
      (footprint "eagle-import:0402")
      (libsource (lib "eagle-import") (part "RESISTOR0402"))
    )
    (comp (ref "R69")
      (value "100")
      (footprint "eagle-import:0402")
      (libsource (lib "eagle-import") (part "RESISTOR0402"))
    )
    (comp (ref "R70")
      (value "100")
      (footprint "eagle-import:0402")
      (libsource (lib "eagle-import") (part "RESISTOR0402"))
    )
    (comp (ref "R71")
      (value "180")
      (footprint "eagle-import:0402")
      (libsource (lib "eagle-import") (part "RESISTOR0402"))
    )
    (comp (ref "R72")
      (value "180")
      (footprint "eagle-import:0402")
      (libsource (lib "eagle-import") (part "RESISTOR0402"))
    )
    (comp (ref "R73")
      (value "180")
      (footprint "eagle-import:0402")
      (libsource (lib "eagle-import") (part "RESISTOR0402"))
    )
    (comp (ref "R74")
      (value "180")
      (footprint "eagle-import:0402")
      (libsource (lib "eagle-import") (part "RESISTOR0402"))
    )
    (comp (ref "R75")
      (value "100")
      (footprint "eagle-import:0402")
      (libsource (lib "eagle-import") (part "RESISTOR0402"))
    )
    (comp (ref "R76")
      (value "100")
      (footprint "eagle-import:0402")
      (libsource (lib "eagle-import") (part "RESISTOR0402"))
    )
    (comp (ref "R77")
      (value "100")
      (footprint "eagle-import:0402")
      (libsource (lib "eagle-import") (part "RESISTOR0402"))
    )
    (comp (ref "R78")
      (value "100")
      (footprint "eagle-import:0402")
      (libsource (lib "eagle-import") (part "RESISTOR0402"))
    )
    (comp (ref "R79")
      (value "180")
      (footprint "eagle-import:0402")
      (libsource (lib "eagle-import") (part "RESISTOR0402"))
    )
    (comp (ref "R80")
      (value "180")
      (footprint "eagle-import:0402")
      (libsource (lib "eagle-import") (part "RESISTOR0402"))
    )
    (comp (ref "R81")
      (value "180")
      (footprint "eagle-import:0402")
      (libsource (lib "eagle-import") (part "RESISTOR0402"))
    )
    (comp (ref "R82")
      (value "180")
      (footprint "eagle-import:0402")
      (libsource (lib "eagle-import") (part "RESISTOR0402"))
    )
    (comp (ref "R83")
      (value "100")
      (footprint "eagle-import:0402")
      (libsource (lib "eagle-import") (part "RESISTOR0402"))
    )
    (comp (ref "R84")
      (value "100")
      (footprint "eagle-import:0402")
      (libsource (lib "eagle-import") (part "RESISTOR0402"))
    )
    (comp (ref "R85")
      (value "100")
      (footprint "eagle-import:0402")
      (libsource (lib "eagle-import") (part "RESISTOR0402"))
    )
    (comp (ref "R86")
      (value "100")
      (footprint "eagle-import:0402")
      (libsource (lib "eagle-import") (part "RESISTOR0402"))
    )
    (comp (ref "R87")
      (value "180")
      (footprint "eagle-import:0402")
      (libsource (lib "eagle-import") (part "RESISTOR0402"))
    )
    (comp (ref "R88")
      (value "180")
      (footprint "eagle-import:0402")
      (libsource (lib "eagle-import") (part "RESISTOR0402"))
    )
    (comp (ref "R89")
      (value "180")
      (footprint "eagle-import:0402")
      (libsource (lib "eagle-import") (part "RESISTOR0402"))
    )
    (comp (ref "R90")
      (value "180")
      (footprint "eagle-import:0402")
      (libsource (lib "eagle-import") (part "RESISTOR0402"))
    )
    (comp (ref "R91")
      (value "100")
      (footprint "eagle-import:0402")
      (libsource (lib "eagle-import") (part "RESISTOR0402"))
    )
    (comp (ref "R92")
      (value "100")
      (footprint "eagle-import:0402")
      (libsource (lib "eagle-import") (part "RESISTOR0402"))
    )
    (comp (ref "R93")
      (value "100")
      (footprint "eagle-import:0402")
      (libsource (lib "eagle-import") (part "RESISTOR0402"))
    )
    (comp (ref "R94")
      (value "100")
      (footprint "eagle-import:0402")
      (libsource (lib "eagle-import") (part "RESISTOR0402"))
    )
    (comp (ref "R95")
      (value "180")
      (footprint "eagle-import:0402")
      (libsource (lib "eagle-import") (part "RESISTOR0402"))
    )
    (comp (ref "R96")
      (value "180")
      (footprint "eagle-import:0402")
      (libsource (lib "eagle-import") (part "RESISTOR0402"))
    )
    (comp (ref "R97")
      (value "180")
      (footprint "eagle-import:0402")
      (libsource (lib "eagle-import") (part "RESISTOR0402"))
    )
    (comp (ref "R98")
      (value "180")
      (footprint "eagle-import:0402")
      (libsource (lib "eagle-import") (part "RESISTOR0402"))
    )
    (comp (ref "R99")
      (value "100")
      (footprint "eagle-import:0402")
      (libsource (lib "eagle-import") (part "RESISTOR0402"))
    )
    (comp (ref "R100")
      (value "100")
      (footprint "eagle-import:0402")
      (libsource (lib "eagle-import") (part "RESISTOR0402"))
    )
    (comp (ref "R101")
      (value "100")
      (footprint "eagle-import:0402")
      (libsource (lib "eagle-import") (part "RESISTOR0402"))
    )
    (comp (ref "R102")
      (value "100")
      (footprint "eagle-import:0402")
      (libsource (lib "eagle-import") (part "RESISTOR0402"))
    )
    (comp (ref "R103")
      (value "180")
      (footprint "eagle-import:0402")
      (libsource (lib "eagle-import") (part "RESISTOR0402"))
    )
    (comp (ref "R104")
      (value "180")
      (footprint "eagle-import:0402")
      (libsource (lib "eagle-import") (part "RESISTOR0402"))
    )
    (comp (ref "R105")
      (value "180")
      (footprint "eagle-import:0402")
      (libsource (lib "eagle-import") (part "RESISTOR0402"))
    )
    (comp (ref "R106")
      (value "180")
      (footprint "eagle-import:0402")
      (libsource (lib "eagle-import") (part "RESISTOR0402"))
    )
    (comp (ref "R107")
      (value "100")
      (footprint "eagle-import:0402")
      (libsource (lib "eagle-import") (part "RESISTOR0402"))
    )
    (comp (ref "R108")
      (value "100")
      (footprint "eagle-import:0402")
      (libsource (lib "eagle-import") (part "RESISTOR0402"))
    )
    (comp (ref "R109")
      (value "100")
      (footprint "eagle-import:0402")
      (libsource (lib "eagle-import") (part "RESISTOR0402"))
    )
    (comp (ref "R110")
      (value "100")
      (footprint "eagle-import:0402")
      (libsource (lib "eagle-import") (part "RESISTOR0402"))
    )
    (comp (ref "R111")
      (value "180")
      (footprint "eagle-import:0402")
      (libsource (lib "eagle-import") (part "RESISTOR0402"))
    )
    (comp (ref "R112")
      (value "180")
      (footprint "eagle-import:0402")
      (libsource (lib "eagle-import") (part "RESISTOR0402"))
    )
    (comp (ref "R113")
      (value "180")
      (footprint "eagle-import:0402")
      (libsource (lib "eagle-import") (part "RESISTOR0402"))
    )
    (comp (ref "R114")
      (value "180")
      (footprint "eagle-import:0402")
      (libsource (lib "eagle-import") (part "RESISTOR0402"))
    )
    (comp (ref "R115")
      (value "100")
      (footprint "eagle-import:0402")
      (libsource (lib "eagle-import") (part "RESISTOR0402"))
    )
    (comp (ref "R116")
      (value "100")
      (footprint "eagle-import:0402")
      (libsource (lib "eagle-import") (part "RESISTOR0402"))
    )
    (comp (ref "R117")
      (value "100")
      (footprint "eagle-import:0402")
      (libsource (lib "eagle-import") (part "RESISTOR0402"))
    )
    (comp (ref "R118")
      (value "100")
      (footprint "eagle-import:0402")
      (libsource (lib "eagle-import") (part "RESISTOR0402"))
    )
    (comp (ref "R119")
      (value "180")
      (footprint "eagle-import:0402")
      (libsource (lib "eagle-import") (part "RESISTOR0402"))
    )
    (comp (ref "R120")
      (value "180")
      (footprint "eagle-import:0402")
      (libsource (lib "eagle-import") (part "RESISTOR0402"))
    )
    (comp (ref "R121")
      (value "180")
      (footprint "eagle-import:0402")
      (libsource (lib "eagle-import") (part "RESISTOR0402"))
    )
    (comp (ref "R122")
      (value "180")
      (footprint "eagle-import:0402")
      (libsource (lib "eagle-import") (part "RESISTOR0402"))
    )
    (comp (ref "R123")
      (value "100")
      (footprint "eagle-import:0402")
      (libsource (lib "eagle-import") (part "RESISTOR0402"))
    )
    (comp (ref "R124")
      (value "100")
      (footprint "eagle-import:0402")
      (libsource (lib "eagle-import") (part "RESISTOR0402"))
    )
    (comp (ref "R125")
      (value "100")
      (footprint "eagle-import:0402")
      (libsource (lib "eagle-import") (part "RESISTOR0402"))
    )
    (comp (ref "R126")
      (value "100")
      (footprint "eagle-import:0402")
      (libsource (lib "eagle-import") (part "RESISTOR0402"))
    )
    (comp (ref "R127")
      (value "180")
      (footprint "eagle-import:0402")
      (libsource (lib "eagle-import") (part "RESISTOR0402"))
    )
    (comp (ref "R128")
      (value "180")
      (footprint "eagle-import:0402")
      (libsource (lib "eagle-import") (part "RESISTOR0402"))
    )
    (comp (ref "R129")
      (value "180")
      (footprint "eagle-import:0402")
      (libsource (lib "eagle-import") (part "RESISTOR0402"))
    )
    (comp (ref "R130")
      (value "180")
      (footprint "eagle-import:0402")
      (libsource (lib "eagle-import") (part "RESISTOR0402"))
    )
    (comp (ref "R131")
      (value "100")
      (footprint "eagle-import:0402")
      (libsource (lib "eagle-import") (part "RESISTOR0402"))
    )
    (comp (ref "R132")
      (value "100")
      (footprint "eagle-import:0402")
      (libsource (lib "eagle-import") (part "RESISTOR0402"))
    )
    (comp (ref "R133")
      (value "100")
      (footprint "eagle-import:0402")
      (libsource (lib "eagle-import") (part "RESISTOR0402"))
    )
    (comp (ref "R134")
      (value "100")
      (footprint "eagle-import:0402")
      (libsource (lib "eagle-import") (part "RESISTOR0402"))
    )
    (comp (ref "R135")
      (value "180")
      (footprint "eagle-import:0402")
      (libsource (lib "eagle-import") (part "RESISTOR0402"))
    )
    (comp (ref "R136")
      (value "180")
      (footprint "eagle-import:0402")
      (libsource (lib "eagle-import") (part "RESISTOR0402"))
    )
    (comp (ref "R137")
      (value "180")
      (footprint "eagle-import:0402")
      (libsource (lib "eagle-import") (part "RESISTOR0402"))
    )
    (comp (ref "R138")
      (value "180")
      (footprint "eagle-import:0402")
      (libsource (lib "eagle-import") (part "RESISTOR0402"))
    )
    (comp (ref "R139")
      (value "100")
      (footprint "eagle-import:0402")
      (libsource (lib "eagle-import") (part "RESISTOR0402"))
    )
    (comp (ref "R140")
      (value "100")
      (footprint "eagle-import:0402")
      (libsource (lib "eagle-import") (part "RESISTOR0402"))
    )
    (comp (ref "R141")
      (value "100")
      (footprint "eagle-import:0402")
      (libsource (lib "eagle-import") (part "RESISTOR0402"))
    )
    (comp (ref "R142")
      (value "100")
      (footprint "eagle-import:0402")
      (libsource (lib "eagle-import") (part "RESISTOR0402"))
    )
    (comp (ref "R143")
      (value "180")
      (footprint "eagle-import:0402")
      (libsource (lib "eagle-import") (part "RESISTOR0402"))
    )
    (comp (ref "R144")
      (value "180")
      (footprint "eagle-import:0402")
      (libsource (lib "eagle-import") (part "RESISTOR0402"))
    )
    (comp (ref "R145")
      (value "180")
      (footprint "eagle-import:0402")
      (libsource (lib "eagle-import") (part "RESISTOR0402"))
    )
    (comp (ref "R146")
      (value "180")
      (footprint "eagle-import:0402")
      (libsource (lib "eagle-import") (part "RESISTOR0402"))
    )
    (comp (ref "R147")
      (value "100")
      (footprint "eagle-import:0402")
      (libsource (lib "eagle-import") (part "RESISTOR0402"))
    )
    (comp (ref "R148")
      (value "100")
      (footprint "eagle-import:0402")
      (libsource (lib "eagle-import") (part "RESISTOR0402"))
    )
    (comp (ref "R149")
      (value "100")
      (footprint "eagle-import:0402")
      (libsource (lib "eagle-import") (part "RESISTOR0402"))
    )
    (comp (ref "R150")
      (value "100")
      (footprint "eagle-import:0402")
      (libsource (lib "eagle-import") (part "RESISTOR0402"))
    )
    (comp (ref "R151")
      (value "180")
      (footprint "eagle-import:0402")
      (libsource (lib "eagle-import") (part "RESISTOR0402"))
    )
    (comp (ref "R152")
      (value "180")
      (footprint "eagle-import:0402")
      (libsource (lib "eagle-import") (part "RESISTOR0402"))
    )
    (comp (ref "R153")
      (value "180")
      (footprint "eagle-import:0402")
      (libsource (lib "eagle-import") (part "RESISTOR0402"))
    )
    (comp (ref "R154")
      (value "180")
      (footprint "eagle-import:0402")
      (libsource (lib "eagle-import") (part "RESISTOR0402"))
    )
    (comp (ref "R155")
      (value "100")
      (footprint "eagle-import:0402")
      (libsource (lib "eagle-import") (part "RESISTOR0402"))
    )
    (comp (ref "R156")
      (value "100")
      (footprint "eagle-import:0402")
      (libsource (lib "eagle-import") (part "RESISTOR0402"))
    )
    (comp (ref "R157")
      (value "100")
      (footprint "eagle-import:0402")
      (libsource (lib "eagle-import") (part "RESISTOR0402"))
    )
    (comp (ref "R158")
      (value "100")
      (footprint "eagle-import:0402")
      (libsource (lib "eagle-import") (part "RESISTOR0402"))
    )
    (comp (ref "R159")
      (value "180")
      (footprint "eagle-import:0402")
      (libsource (lib "eagle-import") (part "RESISTOR0402"))
    )
    (comp (ref "R160")
      (value "180")
      (footprint "eagle-import:0402")
      (libsource (lib "eagle-import") (part "RESISTOR0402"))
    )
    (comp (ref "R161")
      (value "180")
      (footprint "eagle-import:0402")
      (libsource (lib "eagle-import") (part "RESISTOR0402"))
    )
    (comp (ref "R162")
      (value "180")
      (footprint "eagle-import:0402")
      (libsource (lib "eagle-import") (part "RESISTOR0402"))
    )
    (comp (ref "R163")
      (value "100")
      (footprint "eagle-import:0402")
      (libsource (lib "eagle-import") (part "RESISTOR0402"))
    )
    (comp (ref "R164")
      (value "100")
      (footprint "eagle-import:0402")
      (libsource (lib "eagle-import") (part "RESISTOR0402"))
    )
    (comp (ref "R165")
      (value "100")
      (footprint "eagle-import:0402")
      (libsource (lib "eagle-import") (part "RESISTOR0402"))
    )
    (comp (ref "R166")
      (value "100")
      (footprint "eagle-import:0402")
      (libsource (lib "eagle-import") (part "RESISTOR0402"))
    )
    (comp (ref "R167")
      (value "180")
      (footprint "eagle-import:0402")
      (libsource (lib "eagle-import") (part "RESISTOR0402"))
    )
    (comp (ref "R168")
      (value "180")
      (footprint "eagle-import:0402")
      (libsource (lib "eagle-import") (part "RESISTOR0402"))
    )
    (comp (ref "R169")
      (value "180")
      (footprint "eagle-import:0402")
      (libsource (lib "eagle-import") (part "RESISTOR0402"))
    )
    (comp (ref "R170")
      (value "180")
      (footprint "eagle-import:0402")
      (libsource (lib "eagle-import") (part "RESISTOR0402"))
    )
    (comp (ref "R171")
      (value "100")
      (footprint "eagle-import:0402")
      (libsource (lib "eagle-import") (part "RESISTOR0402"))
    )
    (comp (ref "R172")
      (value "100")
      (footprint "eagle-import:0402")
      (libsource (lib "eagle-import") (part "RESISTOR0402"))
    )
    (comp (ref "R173")
      (value "100")
      (footprint "eagle-import:0402")
      (libsource (lib "eagle-import") (part "RESISTOR0402"))
    )
    (comp (ref "R174")
      (value "100")
      (footprint "eagle-import:0402")
      (libsource (lib "eagle-import") (part "RESISTOR0402"))
    )
    (comp (ref "R175")
      (value "1.25K")
      (footprint "eagle-import:0402")
      (libsource (lib "eagle-import") (part "RESISTOR0402"))
    )
    (comp (ref "R176")
      (value "10K")
      (footprint "eagle-import:0402")
      (libsource (lib "eagle-import") (part "RESISTOR0402"))
    )
    (comp (ref "R177")
      (value "1K")
      (footprint "eagle-import:0402")
      (libsource (lib "eagle-import") (part "RESISTOR0402"))
    )
    (comp (ref "R178")
      (value "1K")
      (footprint "eagle-import:0402")
      (libsource (lib "eagle-import") (part "RESISTOR0402"))
    )
    (comp (ref "R179")
      (value "10K")
      (footprint "eagle-import:0402")
      (libsource (lib "eagle-import") (part "RESISTOR0402"))
    )
    (comp (ref "R180")
      (value "22")
      (footprint "eagle-import:0402")
      (libsource (lib "eagle-import") (part "RESISTOR0402"))
    )
    (comp (ref "R181")
      (value "22")
      (footprint "eagle-import:0402")
      (libsource (lib "eagle-import") (part "RESISTOR0402"))
    )
    (comp (ref "R182")
      (value "0")
      (footprint "eagle-import:0402")
      (libsource (lib "eagle-import") (part "RESISTOR0402"))
    )
    (comp (ref "R183")
      (value "0")
      (footprint "eagle-import:0402")
      (libsource (lib "eagle-import") (part "RESISTOR0402"))
    )
    (comp (ref "R186")
      (value "330")
      (footprint "eagle-import:0402")
      (libsource (lib "eagle-import") (part "RESISTOR0402"))
    )
    (comp (ref "R187")
      (value "330")
      (footprint "eagle-import:0402")
      (libsource (lib "eagle-import") (part "RESISTOR0402"))
    )
    (comp (ref "R188")
      (value "1K")
      (footprint "eagle-import:0402")
      (libsource (lib "eagle-import") (part "RESISTOR0402"))
    )
    (comp (ref "R189")
      (value "10K")
      (footprint "eagle-import:0402")
      (libsource (lib "eagle-import") (part "RESISTOR0402"))
    )
    (comp (ref "RESET")
      (value "101-0134-EV")
      (footprint "eagle-import:101-0134-EV")
      (libsource (lib "eagle-import") (part "SPST101-0134-EV"))
    )
    (comp (ref "RGB_CONN")
      (value "PH_1X04HEADER_PTH_ROUND")
      (footprint "eagle-import:HEADER_01X04_PTH_ROUND")
      (libsource (lib "eagle-import") (part "PH_1X04HEADER_PTH_ROUND"))
    )
    (comp (ref "S0")
      (value "RFP12N10L")
      (footprint "eagle-import:TO-220AB")
      (libsource (lib "eagle-import") (part "MOSFET_N-CHANNEL_SINGLETO-220AB"))
    )
    (comp (ref "S1")
      (value "RFP12N10L")
      (footprint "eagle-import:TO-220AB")
      (libsource (lib "eagle-import") (part "MOSFET_N-CHANNEL_SINGLETO-220AB"))
    )
    (comp (ref "S2")
      (value "RFP12N10L")
      (footprint "eagle-import:TO-220AB")
      (libsource (lib "eagle-import") (part "MOSFET_N-CHANNEL_SINGLETO-220AB"))
    )
    (comp (ref "S3")
      (value "RFP12N10L")
      (footprint "eagle-import:TO-220AB")
      (libsource (lib "eagle-import") (part "MOSFET_N-CHANNEL_SINGLETO-220AB"))
    )
    (comp (ref "S4")
      (value "RFP12N10L")
      (footprint "eagle-import:TO-220AB")
      (libsource (lib "eagle-import") (part "MOSFET_N-CHANNEL_SINGLETO-220AB"))
    )
    (comp (ref "S5")
      (value "RFP12N10L")
      (footprint "eagle-import:TO-220AB")
      (libsource (lib "eagle-import") (part "MOSFET_N-CHANNEL_SINGLETO-220AB"))
    )
    (comp (ref "S6")
      (value "RFP12N10L")
      (footprint "eagle-import:TO-220AB")
      (libsource (lib "eagle-import") (part "MOSFET_N-CHANNEL_SINGLETO-220AB"))
    )
    (comp (ref "S7")
      (value "RFP12N10L")
      (footprint "eagle-import:TO-220AB")
      (libsource (lib "eagle-import") (part "MOSFET_N-CHANNEL_SINGLETO-220AB"))
    )
    (comp (ref "S8")
      (value "RFP12N10L")
      (footprint "eagle-import:TO-220AB")
      (libsource (lib "eagle-import") (part "MOSFET_N-CHANNEL_SINGLETO-220AB"))
    )
    (comp (ref "S9")
      (value "RFP12N10L")
      (footprint "eagle-import:TO-220AB")
      (libsource (lib "eagle-import") (part "MOSFET_N-CHANNEL_SINGLETO-220AB"))
    )
    (comp (ref "S10")
      (value "RFP12N10L")
      (footprint "eagle-import:TO-220AB")
      (libsource (lib "eagle-import") (part "MOSFET_N-CHANNEL_SINGLETO-220AB"))
    )
    (comp (ref "S11")
      (value "RFP12N10L")
      (footprint "eagle-import:TO-220AB")
      (libsource (lib "eagle-import") (part "MOSFET_N-CHANNEL_SINGLETO-220AB"))
    )
    (comp (ref "S12")
      (value "RFP12N10L")
      (footprint "eagle-import:TO-220AB")
      (libsource (lib "eagle-import") (part "MOSFET_N-CHANNEL_SINGLETO-220AB"))
    )
    (comp (ref "S13")
      (value "RFP12N10L")
      (footprint "eagle-import:TO-220AB")
      (libsource (lib "eagle-import") (part "MOSFET_N-CHANNEL_SINGLETO-220AB"))
    )
    (comp (ref "S14")
      (value "RFP12N10L")
      (footprint "eagle-import:TO-220AB")
      (libsource (lib "eagle-import") (part "MOSFET_N-CHANNEL_SINGLETO-220AB"))
    )
    (comp (ref "S15")
      (value "RFP12N10L")
      (footprint "eagle-import:TO-220AB")
      (libsource (lib "eagle-import") (part "MOSFET_N-CHANNEL_SINGLETO-220AB"))
    )
    (comp (ref "S16")
      (value "RFP12N10L")
      (footprint "eagle-import:TO-220AB")
      (libsource (lib "eagle-import") (part "MOSFET_N-CHANNEL_SINGLETO-220AB"))
    )
    (comp (ref "S17")
      (value "RFP12N10L")
      (footprint "eagle-import:TO-220AB")
      (libsource (lib "eagle-import") (part "MOSFET_N-CHANNEL_SINGLETO-220AB"))
    )
    (comp (ref "S18")
      (value "RFP12N10L")
      (footprint "eagle-import:TO-220AB")
      (libsource (lib "eagle-import") (part "MOSFET_N-CHANNEL_SINGLETO-220AB"))
    )
    (comp (ref "S19")
      (value "RFP12N10L")
      (footprint "eagle-import:TO-220AB")
      (libsource (lib "eagle-import") (part "MOSFET_N-CHANNEL_SINGLETO-220AB"))
    )
    (comp (ref "S20")
      (value "RFP12N10L")
      (footprint "eagle-import:TO-220AB")
      (libsource (lib "eagle-import") (part "MOSFET_N-CHANNEL_SINGLETO-220AB"))
    )
    (comp (ref "S21")
      (value "RFP12N10L")
      (footprint "eagle-import:TO-220AB")
      (libsource (lib "eagle-import") (part "MOSFET_N-CHANNEL_SINGLETO-220AB"))
    )
    (comp (ref "S22")
      (value "RFP12N10L")
      (footprint "eagle-import:TO-220AB")
      (libsource (lib "eagle-import") (part "MOSFET_N-CHANNEL_SINGLETO-220AB"))
    )
    (comp (ref "S23")
      (value "RFP12N10L")
      (footprint "eagle-import:TO-220AB")
      (libsource (lib "eagle-import") (part "MOSFET_N-CHANNEL_SINGLETO-220AB"))
    )
    (comp (ref "S24")
      (value "RFP12N10L")
      (footprint "eagle-import:TO-220AB")
      (libsource (lib "eagle-import") (part "MOSFET_N-CHANNEL_SINGLETO-220AB"))
    )
    (comp (ref "S25")
      (value "RFP12N10L")
      (footprint "eagle-import:TO-220AB")
      (libsource (lib "eagle-import") (part "MOSFET_N-CHANNEL_SINGLETO-220AB"))
    )
    (comp (ref "S26")
      (value "RFP12N10L")
      (footprint "eagle-import:TO-220AB")
      (libsource (lib "eagle-import") (part "MOSFET_N-CHANNEL_SINGLETO-220AB"))
    )
    (comp (ref "S27")
      (value "RFP12N10L")
      (footprint "eagle-import:TO-220AB")
      (libsource (lib "eagle-import") (part "MOSFET_N-CHANNEL_SINGLETO-220AB"))
    )
    (comp (ref "S28")
      (value "RFP12N10L")
      (footprint "eagle-import:TO-220AB")
      (libsource (lib "eagle-import") (part "MOSFET_N-CHANNEL_SINGLETO-220AB"))
    )
    (comp (ref "S29")
      (value "RFP12N10L")
      (footprint "eagle-import:TO-220AB")
      (libsource (lib "eagle-import") (part "MOSFET_N-CHANNEL_SINGLETO-220AB"))
    )
    (comp (ref "S30")
      (value "RFP12N10L")
      (footprint "eagle-import:TO-220AB")
      (libsource (lib "eagle-import") (part "MOSFET_N-CHANNEL_SINGLETO-220AB"))
    )
    (comp (ref "S31")
      (value "RFP12N10L")
      (footprint "eagle-import:TO-220AB")
      (libsource (lib "eagle-import") (part "MOSFET_N-CHANNEL_SINGLETO-220AB"))
    )
    (comp (ref "SD1")
      (value "502570-0893")
      (footprint "eagle-import:502570-0893")
      (libsource (lib "eagle-import") (part "SD_CARD502570-0893"))
    )
    (comp (ref "SEG1")
      (value "LSHD-A103")
      (footprint "eagle-import:LSHD-A103")
      (libsource (lib "eagle-import") (part "7-SEGMENT_SINGLELSHD-A103"))
    )
    (comp (ref "SEG2")
      (value "LSHD-A103")
      (footprint "eagle-import:LSHD-A103")
      (libsource (lib "eagle-import") (part "7-SEGMENT_SINGLELSHD-A103"))
    )
    (comp (ref "SEG3")
      (value "LSHD-A103")
      (footprint "eagle-import:LSHD-A103")
      (libsource (lib "eagle-import") (part "7-SEGMENT_SINGLELSHD-A103"))
    )
    (comp (ref "SERVO_0")
      (value "PH_1X03HEADER_PTH")
      (footprint "eagle-import:HEADER_01X03_PTH")
      (libsource (lib "eagle-import") (part "PH_1X03HEADER_PTH"))
    )
    (comp (ref "SERVO_1")
      (value "PH_1X03HEADER_PTH")
      (footprint "eagle-import:HEADER_01X03_PTH")
      (libsource (lib "eagle-import") (part "PH_1X03HEADER_PTH"))
    )
    (comp (ref "SERVO_2")
      (value "PH_1X03HEADER_PTH")
      (footprint "eagle-import:HEADER_01X03_PTH")
      (libsource (lib "eagle-import") (part "PH_1X03HEADER_PTH"))
    )
    (comp (ref "SERVO_3")
      (value "PH_1X03HEADER_PTH")
      (footprint "eagle-import:HEADER_01X03_PTH")
      (libsource (lib "eagle-import") (part "PH_1X03HEADER_PTH"))
    )
    (comp (ref "SERVO_4")
      (value "PH_1X03HEADER_PTH")
      (footprint "eagle-import:HEADER_01X03_PTH")
      (libsource (lib "eagle-import") (part "PH_1X03HEADER_PTH"))
    )
    (comp (ref "SERVO_5")
      (value "PH_1X03HEADER_PTH")
      (footprint "eagle-import:HEADER_01X03_PTH")
      (libsource (lib "eagle-import") (part "PH_1X03HEADER_PTH"))
    )
    (comp (ref "SERVO_6")
      (value "PH_1X03HEADER_PTH")
      (footprint "eagle-import:HEADER_01X03_PTH")
      (libsource (lib "eagle-import") (part "PH_1X03HEADER_PTH"))
    )
    (comp (ref "SERVO_7")
      (value "PH_1X03HEADER_PTH")
      (footprint "eagle-import:HEADER_01X03_PTH")
      (libsource (lib "eagle-import") (part "PH_1X03HEADER_PTH"))
    )
    (comp (ref "SERVO_EXT_PWR")
      (value "26-61-4020")
      (footprint "eagle-import:MOLEX_KK_2")
      (libsource (lib "eagle-import") (part "PH_1X02MOLEX_26-61-4020"))
    )
    (comp (ref "SOLENOID_PWR")
      (value "26-61-4020")
      (footprint "eagle-import:MOLEX_KK_4")
      (libsource (lib "eagle-import") (part "PH_1X04KK_4"))
    )
    (comp (ref "SW2")
      (value "0S102011MS2QS1")
      (footprint "eagle-import:0S102011MS2QS1")
      (libsource (lib "eagle-import") (part "SPDT0S102011MS2QS1"))
    )
    (comp (ref "U$1")
      (value "LHE_FRAME")
      (footprint "eagle-import:LHE_FRAME")
      (fields
        (field (name "DNAME") "Parker Dillmann")
        (field (name "PNAME") "Main_Board_Tommy_System")
        (field (name "REVNUM") "REV 1")
      )
      (libsource (lib "eagle-import") (part "LHE_FRAME"))
    )
    (comp (ref "U1")
      (value "P8X32A-Q44")
      (footprint "eagle-import:LQFP-44")
      (libsource (lib "eagle-import") (part "P8X32A_PROPELLERLQFP-44"))
    )
    (comp (ref "U2")
      (value "FT230X")
      (footprint "eagle-import:SSOP-16")
      (libsource (lib "eagle-import") (part "FT230XSSOP-16"))
    )
    (comp (ref "U3")
      (value "IP4234CZ6")
      (footprint "eagle-import:SOT-457")
      (libsource (lib "eagle-import") (part "IP4234CZ6SOT-457"))
    )
    (comp (ref "U4")
      (value "CAT24M01XI-T2")
      (footprint "eagle-import:SOIC-8_W")
      (libsource (lib "eagle-import") (part "CAT24M01XI-T2SOIC-8_W"))
    )
    (comp (ref "U5")
      (value "74HC595D-Q100")
      (footprint "eagle-import:TTSOP-16")
      (libsource (lib "eagle-import") (part "74HC595TTSOP-16"))
    )
    (comp (ref "U6")
      (value "74HC595D-Q100")
      (footprint "eagle-import:TTSOP-16")
      (libsource (lib "eagle-import") (part "74HC595TTSOP-16"))
    )
    (comp (ref "U7")
      (value "74HC595D-Q100")
      (footprint "eagle-import:TTSOP-16")
      (libsource (lib "eagle-import") (part "74HC595TTSOP-16"))
    )
    (comp (ref "U8")
      (value "74HC595D-Q100")
      (footprint "eagle-import:TTSOP-16")
      (libsource (lib "eagle-import") (part "74HC595TTSOP-16"))
    )
    (comp (ref "U9")
      (value "SN74HC165QPWRG4Q1")
      (footprint "eagle-import:TTSOP-16")
      (libsource (lib "eagle-import") (part "74HC165TTSOP-16"))
    )
    (comp (ref "U10")
      (value "SN74HC165QPWRG4Q1")
      (footprint "eagle-import:TTSOP-16")
      (libsource (lib "eagle-import") (part "74HC165TTSOP-16"))
    )
    (comp (ref "U11")
      (value "SN74HC165QPWRG4Q1")
      (footprint "eagle-import:TTSOP-16")
      (libsource (lib "eagle-import") (part "74HC165TTSOP-16"))
    )
    (comp (ref "U12")
      (value "SN74HC165QPWRG4Q1")
      (footprint "eagle-import:TTSOP-16")
      (libsource (lib "eagle-import") (part "74HC165TTSOP-16"))
    )
    (comp (ref "U13")
      (value "SN74HC165QPWRG4Q1")
      (footprint "eagle-import:TTSOP-16")
      (libsource (lib "eagle-import") (part "74HC165TTSOP-16"))
    )
    (comp (ref "U14")
      (value "SN74HC165QPWRG4Q1")
      (footprint "eagle-import:TTSOP-16")
      (libsource (lib "eagle-import") (part "74HC165TTSOP-16"))
    )
    (comp (ref "U15")
      (value "SN74HC165QPWRG4Q1")
      (footprint "eagle-import:TTSOP-16")
      (libsource (lib "eagle-import") (part "74HC165TTSOP-16"))
    )
    (comp (ref "U16")
      (value "SN74HC165QPWRG4Q1")
      (footprint "eagle-import:TTSOP-16")
      (libsource (lib "eagle-import") (part "74HC165TTSOP-16"))
    )
    (comp (ref "U17")
      (value "WS2803")
      (footprint "eagle-import:SOP-28")
      (libsource (lib "eagle-import") (part "WS2803SOP-28"))
    )
    (comp (ref "U18")
      (value "WS2803")
      (footprint "eagle-import:SOP-28")
      (libsource (lib "eagle-import") (part "WS2803SOP-28"))
    )
    (comp (ref "U19")
      (value "WS2803")
      (footprint "eagle-import:SOP-28")
      (libsource (lib "eagle-import") (part "WS2803SOP-28"))
    )
    (comp (ref "U20")
      (value "TCMT4100")
      (footprint "eagle-import:SOP-16")
      (libsource (lib "eagle-import") (part "TCMT4100SOP-16"))
    )
    (comp (ref "U21")
      (value "TCMT4100")
      (footprint "eagle-import:SOP-16")
      (libsource (lib "eagle-import") (part "TCMT4100SOP-16"))
    )
    (comp (ref "U22")
      (value "TCMT4100")
      (footprint "eagle-import:SOP-16")
      (libsource (lib "eagle-import") (part "TCMT4100SOP-16"))
    )
    (comp (ref "U23")
      (value "TCMT4100")
      (footprint "eagle-import:SOP-16")
      (libsource (lib "eagle-import") (part "TCMT4100SOP-16"))
    )
    (comp (ref "U24")
      (value "TCMT4100")
      (footprint "eagle-import:SOP-16")
      (libsource (lib "eagle-import") (part "TCMT4100SOP-16"))
    )
    (comp (ref "U25")
      (value "TCMT4100")
      (footprint "eagle-import:SOP-16")
      (libsource (lib "eagle-import") (part "TCMT4100SOP-16"))
    )
    (comp (ref "U26")
      (value "TCMT4100")
      (footprint "eagle-import:SOP-16")
      (libsource (lib "eagle-import") (part "TCMT4100SOP-16"))
    )
    (comp (ref "U27")
      (value "TCMT4100")
      (footprint "eagle-import:SOP-16")
      (libsource (lib "eagle-import") (part "TCMT4100SOP-16"))
    )
    (comp (ref "U28")
      (value "TCMT4100")
      (footprint "eagle-import:SOP-16")
      (libsource (lib "eagle-import") (part "TCMT4100SOP-16"))
    )
    (comp (ref "U29")
      (value "TCMT4100")
      (footprint "eagle-import:SOP-16")
      (libsource (lib "eagle-import") (part "TCMT4100SOP-16"))
    )
    (comp (ref "U30")
      (value "TCMT4100")
      (footprint "eagle-import:SOP-16")
      (libsource (lib "eagle-import") (part "TCMT4100SOP-16"))
    )
    (comp (ref "U31")
      (value "TCMT4100")
      (footprint "eagle-import:SOP-16")
      (libsource (lib "eagle-import") (part "TCMT4100SOP-16"))
    )
    (comp (ref "U32")
      (value "TCMT4100")
      (footprint "eagle-import:SOP-16")
      (libsource (lib "eagle-import") (part "TCMT4100SOP-16"))
    )
    (comp (ref "U33")
      (value "TCMT4100")
      (footprint "eagle-import:SOP-16")
      (libsource (lib "eagle-import") (part "TCMT4100SOP-16"))
    )
    (comp (ref "U34")
      (value "TCMT4100")
      (footprint "eagle-import:SOP-16")
      (libsource (lib "eagle-import") (part "TCMT4100SOP-16"))
    )
    (comp (ref "U35")
      (value "TCMT4100")
      (footprint "eagle-import:SOP-16")
      (libsource (lib "eagle-import") (part "TCMT4100SOP-16"))
    )
    (comp (ref "U36")
      (value "23LC1024-I/ST")
      (footprint "eagle-import:TTSOP-8")
      (libsource (lib "eagle-import") (part "23A1024/23LC1024TTSOP-8"))
    )
    (comp (ref "U37")
      (value "23LC1024-I/ST")
      (footprint "eagle-import:TTSOP-8")
      (libsource (lib "eagle-import") (part "23A1024/23LC1024TTSOP-8"))
    )
    (comp (ref "U38")
      (value "WS2803")
      (footprint "eagle-import:SOP-28")
      (libsource (lib "eagle-import") (part "WS2803SOP-28"))
    )
    (comp (ref "U39")
      (value "74HC595D-Q100")
      (footprint "eagle-import:TTSOP-16")
      (libsource (lib "eagle-import") (part "74HC595TTSOP-16"))
    )
    (comp (ref "U40")
      (value "74HC595D-Q100")
      (footprint "eagle-import:TTSOP-16")
      (libsource (lib "eagle-import") (part "74HC595TTSOP-16"))
    )
    (comp (ref "U41")
      (value "74HC595D-Q100")
      (footprint "eagle-import:TTSOP-16")
      (libsource (lib "eagle-import") (part "74HC595TTSOP-16"))
    )
    (comp (ref "U42")
      (value "74HC595D-Q100")
      (footprint "eagle-import:TTSOP-16")
      (libsource (lib "eagle-import") (part "74HC595TTSOP-16"))
    )
    (comp (ref "U75")
      (value "IP4234CZ6")
      (footprint "eagle-import:SOT-457")
      (libsource (lib "eagle-import") (part "IP4234CZ6SOT-457"))
    )
    (comp (ref "U76")
      (value "IP4234CZ6")
      (footprint "eagle-import:SOT-457")
      (libsource (lib "eagle-import") (part "IP4234CZ6SOT-457"))
    )
    (comp (ref "U77")
      (value "IP4234CZ6")
      (footprint "eagle-import:SOT-457")
      (libsource (lib "eagle-import") (part "IP4234CZ6SOT-457"))
    )
    (comp (ref "U78")
      (value "IP4234CZ6")
      (footprint "eagle-import:SOT-457")
      (libsource (lib "eagle-import") (part "IP4234CZ6SOT-457"))
    )
    (comp (ref "U79")
      (value "IP4234CZ6")
      (footprint "eagle-import:SOT-457")
      (libsource (lib "eagle-import") (part "IP4234CZ6SOT-457"))
    )
    (comp (ref "U80")
      (value "IP4234CZ6")
      (footprint "eagle-import:SOT-457")
      (libsource (lib "eagle-import") (part "IP4234CZ6SOT-457"))
    )
    (comp (ref "U81")
      (value "MIC1832MY")
      (footprint "eagle-import:SOIC-8")
      (libsource (lib "eagle-import") (part "MIC1232MYSOIC-8"))
    )
    (comp (ref "U82")
      (value "IP4234CZ6")
      (footprint "eagle-import:SOT-457")
      (libsource (lib "eagle-import") (part "IP4234CZ6SOT-457"))
    )
    (comp (ref "U83")
      (value "AD7991YRJZ-0500RL7")
      (footprint "eagle-import:SOT-23-8")
      (libsource (lib "eagle-import") (part "AD799XSOT-23-8"))
    )
    (comp (ref "U84")
      (value "MMBT 3904 LT1")
      (footprint "eagle-import:SOT-23")
      (libsource (lib "eagle-import") (part "BJT_NPN_SINGLESOT-23"))
    )
    (comp (ref "USB")
      (value "10118193-0001LF")
      (footprint "eagle-import:10118193-0001LF")
      (libsource (lib "eagle-import") (part "USB10118193-0001LF"))
    )
    (comp (ref "X1")
      (value "ABMM-6.000MHZ-B2-T")
      (footprint "eagle-import:7MM_X_5MM")
      (libsource (lib "eagle-import") (part "CRYSTAL7MM_X_5MM"))
    )
  )
  (nets
    (net (code "1") (name "/-5V") (class "Default")
      (node (ref "PC_POWER_SUPPLY") (pin "16") (pinfunction "16_16") (pintype "bidirectional"))
    )
    (net (code "2") (name "/-12V") (class "Default")
      (node (ref "PC_POWER_SUPPLY") (pin "4") (pinfunction "4_4") (pintype "bidirectional"))
    )
    (net (code "3") (name "/3.3V") (class "Default")
      (node (ref "ANALOG_0") (pin "3") (pinfunction "3_3") (pintype "passive"))
      (node (ref "ANALOG_1") (pin "3") (pinfunction "3_3") (pintype "passive"))
      (node (ref "ANALOG_2") (pin "3") (pinfunction "3_3") (pintype "passive"))
      (node (ref "ANALOG_3") (pin "3") (pinfunction "3_3") (pintype "passive"))
      (node (ref "AUX") (pin "1") (pinfunction "1_1") (pintype "bidirectional"))
      (node (ref "C10") (pin "2") (pinfunction "2_2") (pintype "passive"))
      (node (ref "C11") (pin "2") (pinfunction "2_2") (pintype "passive"))
      (node (ref "C12") (pin "2") (pinfunction "2_2") (pintype "passive"))
      (node (ref "C13") (pin "2") (pinfunction "2_2") (pintype "passive"))
      (node (ref "C14") (pin "2") (pinfunction "2_2") (pintype "passive"))
      (node (ref "C15") (pin "2") (pinfunction "2_2") (pintype "passive"))
      (node (ref "C16") (pin "2") (pinfunction "2_2") (pintype "passive"))
      (node (ref "C17") (pin "2") (pinfunction "2_2") (pintype "passive"))
      (node (ref "C18") (pin "2") (pinfunction "2_2") (pintype "passive"))
      (node (ref "C19") (pin "2") (pinfunction "2_2") (pintype "passive"))
      (node (ref "C20") (pin "2") (pinfunction "2_2") (pintype "passive"))
      (node (ref "C21") (pin "1") (pinfunction "1_1") (pintype "passive"))
      (node (ref "C22") (pin "2") (pinfunction "2_2") (pintype "passive"))
      (node (ref "C23") (pin "2") (pinfunction "2_2") (pintype "passive"))
      (node (ref "C24") (pin "2") (pinfunction "2_2") (pintype "passive"))
      (node (ref "C25") (pin "2") (pinfunction "2_2") (pintype "passive"))
      (node (ref "C26") (pin "2") (pinfunction "2_2") (pintype "passive"))
      (node (ref "C27") (pin "2") (pinfunction "2_2") (pintype "passive"))
      (node (ref "C28") (pin "2") (pinfunction "2_2") (pintype "passive"))
      (node (ref "C29") (pin "2") (pinfunction "2_2") (pintype "passive"))
      (node (ref "C3") (pin "2") (pinfunction "2_2") (pintype "passive"))
      (node (ref "C30") (pin "2") (pinfunction "2_2") (pintype "passive"))
      (node (ref "C31") (pin "2") (pinfunction "2_2") (pintype "passive"))
      (node (ref "C32") (pin "+") (pinfunction "POS_+") (pintype "bidirectional"))
      (node (ref "C33") (pin "+") (pinfunction "POS_+") (pintype "bidirectional"))
      (node (ref "C34") (pin "POS") (pinfunction "POS_POS") (pintype "bidirectional"))
      (node (ref "C35") (pin "1") (pinfunction "1_1") (pintype "passive"))
      (node (ref "C36") (pin "1") (pinfunction "1_1") (pintype "passive"))
      (node (ref "C4") (pin "2") (pinfunction "2_2") (pintype "passive"))
      (node (ref "C5") (pin "2") (pinfunction "2_2") (pintype "passive"))
      (node (ref "C59") (pin "2") (pinfunction "2_2") (pintype "passive"))
      (node (ref "C6") (pin "2") (pinfunction "2_2") (pintype "passive"))
      (node (ref "C60") (pin "2") (pinfunction "2_2") (pintype "passive"))
      (node (ref "C61") (pin "2") (pinfunction "2_2") (pintype "passive"))
      (node (ref "C8") (pin "2") (pinfunction "2_2") (pintype "passive"))
      (node (ref "C9") (pin "2") (pinfunction "2_2") (pintype "passive"))
      (node (ref "EM1") (pin "2") (pinfunction "2_2") (pintype "bidirectional"))
      (node (ref "J35") (pin "1") (pinfunction "1_1") (pintype "bidirectional"))
      (node (ref "PC_POWER_SUPPLY") (pin "1") (pinfunction "1_1") (pintype "bidirectional"))
      (node (ref "PC_POWER_SUPPLY") (pin "2") (pinfunction "2_2") (pintype "bidirectional"))
      (node (ref "PC_POWER_SUPPLY") (pin "3") (pinfunction "3_3") (pintype "bidirectional"))
      (node (ref "R10") (pin "2") (pinfunction "2_2") (pintype "passive"))
      (node (ref "R11") (pin "2") (pinfunction "2_2") (pintype "passive"))
      (node (ref "R176") (pin "2") (pinfunction "2_2") (pintype "passive"))
      (node (ref "R186") (pin "2") (pinfunction "2_2") (pintype "passive"))
      (node (ref "R4") (pin "2") (pinfunction "2_2") (pintype "passive"))
      (node (ref "R5") (pin "2") (pinfunction "2_2") (pintype "passive"))
      (node (ref "R6") (pin "2") (pinfunction "2_2") (pintype "passive"))
      (node (ref "R7") (pin "2") (pinfunction "2_2") (pintype "passive"))
      (node (ref "R8") (pin "2") (pinfunction "2_2") (pintype "passive"))
      (node (ref "R9") (pin "2") (pinfunction "2_2") (pintype "passive"))
      (node (ref "RGB_CONN") (pin "4") (pinfunction "4_4") (pintype "passive"))
      (node (ref "SD1") (pin "5") (pinfunction "3.3V_5") (pintype "bidirectional"))
      (node (ref "U1") (pin "18") (pinfunction "VDD_18") (pintype "bidirectional"))
      (node (ref "U1") (pin "30") (pinfunction "VDD_30") (pintype "bidirectional"))
      (node (ref "U1") (pin "40") (pinfunction "VDD_40") (pintype "bidirectional"))
      (node (ref "U1") (pin "8") (pinfunction "VDD_8") (pintype "bidirectional"))
      (node (ref "U10") (pin "16") (pinfunction "VCC_16") (pintype "bidirectional"))
      (node (ref "U11") (pin "16") (pinfunction "VCC_16") (pintype "bidirectional"))
      (node (ref "U12") (pin "16") (pinfunction "VCC_16") (pintype "bidirectional"))
      (node (ref "U13") (pin "16") (pinfunction "VCC_16") (pintype "bidirectional"))
      (node (ref "U14") (pin "16") (pinfunction "VCC_16") (pintype "bidirectional"))
      (node (ref "U15") (pin "16") (pinfunction "VCC_16") (pintype "bidirectional"))
      (node (ref "U16") (pin "16") (pinfunction "VCC_16") (pintype "bidirectional"))
      (node (ref "U17") (pin "28") (pinfunction "VCC_28") (pintype "bidirectional"))
      (node (ref "U18") (pin "28") (pinfunction "VCC_28") (pintype "bidirectional"))
      (node (ref "U19") (pin "28") (pinfunction "VCC_28") (pintype "bidirectional"))
      (node (ref "U20") (pin "10") (pinfunction "CO3_10") (pintype "bidirectional"))
      (node (ref "U20") (pin "12") (pinfunction "CO2_12") (pintype "bidirectional"))
      (node (ref "U20") (pin "14") (pinfunction "CO1_14") (pintype "bidirectional"))
      (node (ref "U20") (pin "16") (pinfunction "CO0_16") (pintype "bidirectional"))
      (node (ref "U21") (pin "10") (pinfunction "CO3_10") (pintype "bidirectional"))
      (node (ref "U21") (pin "12") (pinfunction "CO2_12") (pintype "bidirectional"))
      (node (ref "U21") (pin "14") (pinfunction "CO1_14") (pintype "bidirectional"))
      (node (ref "U21") (pin "16") (pinfunction "CO0_16") (pintype "bidirectional"))
      (node (ref "U22") (pin "10") (pinfunction "CO3_10") (pintype "bidirectional"))
      (node (ref "U22") (pin "12") (pinfunction "CO2_12") (pintype "bidirectional"))
      (node (ref "U22") (pin "14") (pinfunction "CO1_14") (pintype "bidirectional"))
      (node (ref "U22") (pin "16") (pinfunction "CO0_16") (pintype "bidirectional"))
      (node (ref "U23") (pin "10") (pinfunction "CO3_10") (pintype "bidirectional"))
      (node (ref "U23") (pin "12") (pinfunction "CO2_12") (pintype "bidirectional"))
      (node (ref "U23") (pin "14") (pinfunction "CO1_14") (pintype "bidirectional"))
      (node (ref "U23") (pin "16") (pinfunction "CO0_16") (pintype "bidirectional"))
      (node (ref "U24") (pin "10") (pinfunction "CO3_10") (pintype "bidirectional"))
      (node (ref "U24") (pin "12") (pinfunction "CO2_12") (pintype "bidirectional"))
      (node (ref "U24") (pin "14") (pinfunction "CO1_14") (pintype "bidirectional"))
      (node (ref "U24") (pin "16") (pinfunction "CO0_16") (pintype "bidirectional"))
      (node (ref "U25") (pin "10") (pinfunction "CO3_10") (pintype "bidirectional"))
      (node (ref "U25") (pin "12") (pinfunction "CO2_12") (pintype "bidirectional"))
      (node (ref "U25") (pin "14") (pinfunction "CO1_14") (pintype "bidirectional"))
      (node (ref "U25") (pin "16") (pinfunction "CO0_16") (pintype "bidirectional"))
      (node (ref "U26") (pin "10") (pinfunction "CO3_10") (pintype "bidirectional"))
      (node (ref "U26") (pin "12") (pinfunction "CO2_12") (pintype "bidirectional"))
      (node (ref "U26") (pin "14") (pinfunction "CO1_14") (pintype "bidirectional"))
      (node (ref "U26") (pin "16") (pinfunction "CO0_16") (pintype "bidirectional"))
      (node (ref "U27") (pin "10") (pinfunction "CO3_10") (pintype "bidirectional"))
      (node (ref "U27") (pin "12") (pinfunction "CO2_12") (pintype "bidirectional"))
      (node (ref "U27") (pin "14") (pinfunction "CO1_14") (pintype "bidirectional"))
      (node (ref "U27") (pin "16") (pinfunction "CO0_16") (pintype "bidirectional"))
      (node (ref "U28") (pin "10") (pinfunction "CO3_10") (pintype "bidirectional"))
      (node (ref "U28") (pin "12") (pinfunction "CO2_12") (pintype "bidirectional"))
      (node (ref "U28") (pin "14") (pinfunction "CO1_14") (pintype "bidirectional"))
      (node (ref "U28") (pin "16") (pinfunction "CO0_16") (pintype "bidirectional"))
      (node (ref "U29") (pin "10") (pinfunction "CO3_10") (pintype "bidirectional"))
      (node (ref "U29") (pin "12") (pinfunction "CO2_12") (pintype "bidirectional"))
      (node (ref "U29") (pin "14") (pinfunction "CO1_14") (pintype "bidirectional"))
      (node (ref "U29") (pin "16") (pinfunction "CO0_16") (pintype "bidirectional"))
      (node (ref "U30") (pin "10") (pinfunction "CO3_10") (pintype "bidirectional"))
      (node (ref "U30") (pin "12") (pinfunction "CO2_12") (pintype "bidirectional"))
      (node (ref "U30") (pin "14") (pinfunction "CO1_14") (pintype "bidirectional"))
      (node (ref "U30") (pin "16") (pinfunction "CO0_16") (pintype "bidirectional"))
      (node (ref "U31") (pin "10") (pinfunction "CO3_10") (pintype "bidirectional"))
      (node (ref "U31") (pin "12") (pinfunction "CO2_12") (pintype "bidirectional"))
      (node (ref "U31") (pin "14") (pinfunction "CO1_14") (pintype "bidirectional"))
      (node (ref "U31") (pin "16") (pinfunction "CO0_16") (pintype "bidirectional"))
      (node (ref "U32") (pin "10") (pinfunction "CO3_10") (pintype "bidirectional"))
      (node (ref "U32") (pin "12") (pinfunction "CO2_12") (pintype "bidirectional"))
      (node (ref "U32") (pin "14") (pinfunction "CO1_14") (pintype "bidirectional"))
      (node (ref "U32") (pin "16") (pinfunction "CO0_16") (pintype "bidirectional"))
      (node (ref "U33") (pin "10") (pinfunction "CO3_10") (pintype "bidirectional"))
      (node (ref "U33") (pin "12") (pinfunction "CO2_12") (pintype "bidirectional"))
      (node (ref "U33") (pin "14") (pinfunction "CO1_14") (pintype "bidirectional"))
      (node (ref "U33") (pin "16") (pinfunction "CO0_16") (pintype "bidirectional"))
      (node (ref "U34") (pin "10") (pinfunction "CO3_10") (pintype "bidirectional"))
      (node (ref "U34") (pin "12") (pinfunction "CO2_12") (pintype "bidirectional"))
      (node (ref "U34") (pin "14") (pinfunction "CO1_14") (pintype "bidirectional"))
      (node (ref "U34") (pin "16") (pinfunction "CO0_16") (pintype "bidirectional"))
      (node (ref "U35") (pin "10") (pinfunction "CO3_10") (pintype "bidirectional"))
      (node (ref "U35") (pin "12") (pinfunction "CO2_12") (pintype "bidirectional"))
      (node (ref "U35") (pin "14") (pinfunction "CO1_14") (pintype "bidirectional"))
      (node (ref "U35") (pin "16") (pinfunction "CO0_16") (pintype "bidirectional"))
      (node (ref "U36") (pin "8") (pinfunction "VCC_8") (pintype "bidirectional"))
      (node (ref "U37") (pin "8") (pinfunction "VCC_8") (pintype "bidirectional"))
      (node (ref "U38") (pin "28") (pinfunction "VCC_28") (pintype "bidirectional"))
      (node (ref "U39") (pin "10") (pinfunction "MR_10") (pintype "bidirectional"))
      (node (ref "U39") (pin "16") (pinfunction "VCC_16") (pintype "bidirectional"))
      (node (ref "U4") (pin "8") (pinfunction "VCC_8") (pintype "bidirectional"))
      (node (ref "U40") (pin "10") (pinfunction "MR_10") (pintype "bidirectional"))
      (node (ref "U40") (pin "16") (pinfunction "VCC_16") (pintype "bidirectional"))
      (node (ref "U41") (pin "10") (pinfunction "MR_10") (pintype "bidirectional"))
      (node (ref "U41") (pin "16") (pinfunction "VCC_16") (pintype "bidirectional"))
      (node (ref "U42") (pin "10") (pinfunction "MR_10") (pintype "bidirectional"))
      (node (ref "U42") (pin "16") (pinfunction "VCC_16") (pintype "bidirectional"))
      (node (ref "U5") (pin "10") (pinfunction "MR_10") (pintype "bidirectional"))
      (node (ref "U5") (pin "16") (pinfunction "VCC_16") (pintype "bidirectional"))
      (node (ref "U6") (pin "10") (pinfunction "MR_10") (pintype "bidirectional"))
      (node (ref "U6") (pin "16") (pinfunction "VCC_16") (pintype "bidirectional"))
      (node (ref "U7") (pin "10") (pinfunction "MR_10") (pintype "bidirectional"))
      (node (ref "U7") (pin "16") (pinfunction "VCC_16") (pintype "bidirectional"))
      (node (ref "U75") (pin "5") (pinfunction "VB_5") (pintype "bidirectional"))
      (node (ref "U76") (pin "5") (pinfunction "VB_5") (pintype "bidirectional"))
      (node (ref "U77") (pin "5") (pinfunction "VB_5") (pintype "bidirectional"))
      (node (ref "U78") (pin "5") (pinfunction "VB_5") (pintype "bidirectional"))
      (node (ref "U79") (pin "5") (pinfunction "VB_5") (pintype "bidirectional"))
      (node (ref "U8") (pin "10") (pinfunction "MR_10") (pintype "bidirectional"))
      (node (ref "U8") (pin "16") (pinfunction "VCC_16") (pintype "bidirectional"))
      (node (ref "U80") (pin "5") (pinfunction "VB_5") (pintype "bidirectional"))
      (node (ref "U81") (pin "2") (pinfunction "TD_2") (pintype "bidirectional"))
      (node (ref "U81") (pin "3") (pinfunction "TOL_3") (pintype "bidirectional"))
      (node (ref "U81") (pin "8") (pinfunction "VCC_8") (pintype "bidirectional"))
      (node (ref "U82") (pin "5") (pinfunction "VB_5") (pintype "bidirectional"))
      (node (ref "U83") (pin "8") (pinfunction "VCC_8") (pintype "bidirectional"))
      (node (ref "U9") (pin "16") (pinfunction "VCC_16") (pintype "bidirectional"))
    )
    (net (code "4") (name "/3V3OUT") (class "Default")
      (node (ref "C2") (pin "1") (pinfunction "1_1") (pintype "passive"))
      (node (ref "U2") (pin "10") (pinfunction "3V3OUT_10") (pintype "bidirectional"))
      (node (ref "U2") (pin "11") (pinfunction "RESET#_11") (pintype "bidirectional"))
      (node (ref "U2") (pin "3") (pinfunction "VCCIO_3") (pintype "bidirectional"))
    )
    (net (code "5") (name "/5V") (class "Default")
      (node (ref "C37") (pin "+") (pinfunction "POS_+") (pintype "bidirectional"))
      (node (ref "C38") (pin "+") (pinfunction "POS_+") (pintype "bidirectional"))
      (node (ref "C39") (pin "POS") (pinfunction "POS_POS") (pintype "bidirectional"))
      (node (ref "C40") (pin "1") (pinfunction "1_1") (pintype "passive"))
      (node (ref "C41") (pin "1") (pinfunction "1_1") (pintype "passive"))
      (node (ref "DMD_PWR") (pin "P$2") (pinfunction "2_P$2") (pintype "passive"))
      (node (ref "J35") (pin "2") (pinfunction "2_2") (pintype "bidirectional"))
      (node (ref "J36") (pin "1") (pinfunction "1_1") (pintype "bidirectional"))
      (node (ref "PC_POWER_SUPPLY") (pin "11") (pinfunction "11_11") (pintype "bidirectional"))
      (node (ref "PC_POWER_SUPPLY") (pin "18") (pinfunction "18_18") (pintype "bidirectional"))
      (node (ref "PC_POWER_SUPPLY") (pin "20") (pinfunction "20_20") (pintype "bidirectional"))
      (node (ref "PC_POWER_SUPPLY") (pin "7") (pinfunction "7_7") (pintype "bidirectional"))
    )
    (net (code "6") (name "/12V") (class "Default")
      (node (ref "C46") (pin "2") (pinfunction "2_2") (pintype "passive"))
      (node (ref "C47") (pin "2") (pinfunction "2_2") (pintype "passive"))
      (node (ref "C48") (pin "2") (pinfunction "2_2") (pintype "passive"))
      (node (ref "C49") (pin "2") (pinfunction "2_2") (pintype "passive"))
      (node (ref "C50") (pin "2") (pinfunction "2_2") (pintype "passive"))
      (node (ref "C51") (pin "2") (pinfunction "2_2") (pintype "passive"))
      (node (ref "C52") (pin "2") (pinfunction "2_2") (pintype "passive"))
      (node (ref "C53") (pin "2") (pinfunction "2_2") (pintype "passive"))
      (node (ref "C54") (pin "+") (pinfunction "POS_+") (pintype "bidirectional"))
      (node (ref "C55") (pin "+") (pinfunction "POS_+") (pintype "bidirectional"))
      (node (ref "C56") (pin "POS") (pinfunction "POS_POS") (pintype "bidirectional"))
      (node (ref "C57") (pin "1") (pinfunction "1_1") (pintype "passive"))
      (node (ref "C58") (pin "1") (pinfunction "1_1") (pintype "passive"))
      (node (ref "INPUT_BANK_0") (pin "9") (pinfunction "9_9") (pintype "bidirectional"))
      (node (ref "INPUT_BANK_1") (pin "9") (pinfunction "9_9") (pintype "bidirectional"))
      (node (ref "INPUT_BANK_2") (pin "9") (pinfunction "9_9") (pintype "bidirectional"))
      (node (ref "INPUT_BANK_3") (pin "9") (pinfunction "9_9") (pintype "bidirectional"))
      (node (ref "INPUT_BANK_4") (pin "9") (pinfunction "9_9") (pintype "bidirectional"))
      (node (ref "INPUT_BANK_5") (pin "9") (pinfunction "9_9") (pintype "bidirectional"))
      (node (ref "INPUT_BANK_6") (pin "9") (pinfunction "9_9") (pintype "bidirectional"))
      (node (ref "INPUT_BANK_7") (pin "9") (pinfunction "9_9") (pintype "bidirectional"))
      (node (ref "J35") (pin "3") (pinfunction "3_3") (pintype "bidirectional"))
      (node (ref "J36") (pin "3") (pinfunction "3_3") (pintype "bidirectional"))
      (node (ref "PC_POWER_SUPPLY") (pin "19") (pinfunction "19_19") (pintype "bidirectional"))
    )
    (net (code "7") (name "/AUDIO_L") (class "Default")
      (node (ref "R177") (pin "1") (pinfunction "1_1") (pintype "passive"))
      (node (ref "U1") (pin "33") (pinfunction "P26_33") (pintype "bidirectional"))
    )
    (net (code "8") (name "/AUDIO_OUT_L") (class "Default")
      (node (ref "AUDIO") (pin "5") (pinfunction "T_5") (pintype "bidirectional"))
      (node (ref "C42") (pin "1") (pinfunction "1_1") (pintype "passive"))
    )
    (net (code "9") (name "/AUDIO_OUT_R") (class "Default")
      (node (ref "AUDIO") (pin "2") (pinfunction "R_2") (pintype "bidirectional"))
      (node (ref "C43") (pin "1") (pinfunction "1_1") (pintype "passive"))
    )
    (net (code "10") (name "/AUDIO_R") (class "Default")
      (node (ref "R178") (pin "1") (pinfunction "1_1") (pintype "passive"))
      (node (ref "U1") (pin "34") (pinfunction "P27_34") (pintype "bidirectional"))
    )
    (net (code "11") (name "/A_0") (class "Default")
      (node (ref "ANALOG_0") (pin "1") (pinfunction "1_1") (pintype "passive"))
      (node (ref "U83") (pin "3") (pinfunction "A_0_3") (pintype "bidirectional"))
    )
    (net (code "12") (name "/A_1") (class "Default")
      (node (ref "ANALOG_1") (pin "1") (pinfunction "1_1") (pintype "passive"))
      (node (ref "U83") (pin "4") (pinfunction "A_1_4") (pintype "bidirectional"))
    )
    (net (code "13") (name "/A_2") (class "Default")
      (node (ref "ANALOG_2") (pin "1") (pinfunction "1_1") (pintype "passive"))
      (node (ref "U83") (pin "5") (pinfunction "A_2_5") (pintype "bidirectional"))
    )
    (net (code "14") (name "/A_3") (class "Default")
      (node (ref "ANALOG_3") (pin "1") (pinfunction "1_1") (pintype "passive"))
      (node (ref "U83") (pin "6") (pinfunction "A_3_6") (pintype "bidirectional"))
    )
    (net (code "15") (name "/C0") (class "Default")
      (node (ref "R47") (pin "1") (pinfunction "1_1") (pintype "passive"))
      (node (ref "U20") (pin "2") (pinfunction "C0_2") (pintype "bidirectional"))
    )
    (net (code "16") (name "/C1") (class "Default")
      (node (ref "R48") (pin "1") (pinfunction "1_1") (pintype "passive"))
      (node (ref "U20") (pin "4") (pinfunction "C1_4") (pintype "bidirectional"))
    )
    (net (code "17") (name "/C2") (class "Default")
      (node (ref "R49") (pin "1") (pinfunction "1_1") (pintype "passive"))
      (node (ref "U20") (pin "6") (pinfunction "C2_6") (pintype "bidirectional"))
    )
    (net (code "18") (name "/C3") (class "Default")
      (node (ref "R50") (pin "1") (pinfunction "1_1") (pintype "passive"))
      (node (ref "U20") (pin "8") (pinfunction "C3_8") (pintype "bidirectional"))
    )
    (net (code "19") (name "/C4") (class "Default")
      (node (ref "R55") (pin "1") (pinfunction "1_1") (pintype "passive"))
      (node (ref "U21") (pin "2") (pinfunction "C0_2") (pintype "bidirectional"))
    )
    (net (code "20") (name "/C5") (class "Default")
      (node (ref "R56") (pin "1") (pinfunction "1_1") (pintype "passive"))
      (node (ref "U21") (pin "4") (pinfunction "C1_4") (pintype "bidirectional"))
    )
    (net (code "21") (name "/C6") (class "Default")
      (node (ref "R57") (pin "1") (pinfunction "1_1") (pintype "passive"))
      (node (ref "U21") (pin "6") (pinfunction "C2_6") (pintype "bidirectional"))
    )
    (net (code "22") (name "/C7") (class "Default")
      (node (ref "R58") (pin "1") (pinfunction "1_1") (pintype "passive"))
      (node (ref "U21") (pin "8") (pinfunction "C3_8") (pintype "bidirectional"))
    )
    (net (code "23") (name "/C8") (class "Default")
      (node (ref "R63") (pin "1") (pinfunction "1_1") (pintype "passive"))
      (node (ref "U22") (pin "2") (pinfunction "C0_2") (pintype "bidirectional"))
    )
    (net (code "24") (name "/C9") (class "Default")
      (node (ref "R64") (pin "1") (pinfunction "1_1") (pintype "passive"))
      (node (ref "U22") (pin "4") (pinfunction "C1_4") (pintype "bidirectional"))
    )
    (net (code "25") (name "/C10") (class "Default")
      (node (ref "R65") (pin "1") (pinfunction "1_1") (pintype "passive"))
      (node (ref "U22") (pin "6") (pinfunction "C2_6") (pintype "bidirectional"))
    )
    (net (code "26") (name "/C11") (class "Default")
      (node (ref "R66") (pin "1") (pinfunction "1_1") (pintype "passive"))
      (node (ref "U22") (pin "8") (pinfunction "C3_8") (pintype "bidirectional"))
    )
    (net (code "27") (name "/C12") (class "Default")
      (node (ref "R71") (pin "1") (pinfunction "1_1") (pintype "passive"))
      (node (ref "U23") (pin "2") (pinfunction "C0_2") (pintype "bidirectional"))
    )
    (net (code "28") (name "/C13") (class "Default")
      (node (ref "R72") (pin "1") (pinfunction "1_1") (pintype "passive"))
      (node (ref "U23") (pin "4") (pinfunction "C1_4") (pintype "bidirectional"))
    )
    (net (code "29") (name "/C14") (class "Default")
      (node (ref "R73") (pin "1") (pinfunction "1_1") (pintype "passive"))
      (node (ref "U23") (pin "6") (pinfunction "C2_6") (pintype "bidirectional"))
    )
    (net (code "30") (name "/C15") (class "Default")
      (node (ref "R74") (pin "1") (pinfunction "1_1") (pintype "passive"))
      (node (ref "U23") (pin "8") (pinfunction "C3_8") (pintype "bidirectional"))
    )
    (net (code "31") (name "/C16") (class "Default")
      (node (ref "R79") (pin "1") (pinfunction "1_1") (pintype "passive"))
      (node (ref "U24") (pin "2") (pinfunction "C0_2") (pintype "bidirectional"))
    )
    (net (code "32") (name "/C17") (class "Default")
      (node (ref "R80") (pin "1") (pinfunction "1_1") (pintype "passive"))
      (node (ref "U24") (pin "4") (pinfunction "C1_4") (pintype "bidirectional"))
    )
    (net (code "33") (name "/C18") (class "Default")
      (node (ref "R81") (pin "1") (pinfunction "1_1") (pintype "passive"))
      (node (ref "U24") (pin "6") (pinfunction "C2_6") (pintype "bidirectional"))
    )
    (net (code "34") (name "/C19") (class "Default")
      (node (ref "R82") (pin "1") (pinfunction "1_1") (pintype "passive"))
      (node (ref "U24") (pin "8") (pinfunction "C3_8") (pintype "bidirectional"))
    )
    (net (code "35") (name "/C20") (class "Default")
      (node (ref "R87") (pin "1") (pinfunction "1_1") (pintype "passive"))
      (node (ref "U25") (pin "2") (pinfunction "C0_2") (pintype "bidirectional"))
    )
    (net (code "36") (name "/C21") (class "Default")
      (node (ref "R88") (pin "1") (pinfunction "1_1") (pintype "passive"))
      (node (ref "U25") (pin "4") (pinfunction "C1_4") (pintype "bidirectional"))
    )
    (net (code "37") (name "/C22") (class "Default")
      (node (ref "R89") (pin "1") (pinfunction "1_1") (pintype "passive"))
      (node (ref "U25") (pin "6") (pinfunction "C2_6") (pintype "bidirectional"))
    )
    (net (code "38") (name "/C23") (class "Default")
      (node (ref "R90") (pin "1") (pinfunction "1_1") (pintype "passive"))
      (node (ref "U25") (pin "8") (pinfunction "C3_8") (pintype "bidirectional"))
    )
    (net (code "39") (name "/C24") (class "Default")
      (node (ref "R95") (pin "1") (pinfunction "1_1") (pintype "passive"))
      (node (ref "U26") (pin "2") (pinfunction "C0_2") (pintype "bidirectional"))
    )
    (net (code "40") (name "/C25") (class "Default")
      (node (ref "R96") (pin "1") (pinfunction "1_1") (pintype "passive"))
      (node (ref "U26") (pin "4") (pinfunction "C1_4") (pintype "bidirectional"))
    )
    (net (code "41") (name "/C26") (class "Default")
      (node (ref "R97") (pin "1") (pinfunction "1_1") (pintype "passive"))
      (node (ref "U26") (pin "6") (pinfunction "C2_6") (pintype "bidirectional"))
    )
    (net (code "42") (name "/C27") (class "Default")
      (node (ref "R98") (pin "1") (pinfunction "1_1") (pintype "passive"))
      (node (ref "U26") (pin "8") (pinfunction "C3_8") (pintype "bidirectional"))
    )
    (net (code "43") (name "/C28") (class "Default")
      (node (ref "R103") (pin "1") (pinfunction "1_1") (pintype "passive"))
      (node (ref "U27") (pin "2") (pinfunction "C0_2") (pintype "bidirectional"))
    )
    (net (code "44") (name "/C29") (class "Default")
      (node (ref "R104") (pin "1") (pinfunction "1_1") (pintype "passive"))
      (node (ref "U27") (pin "4") (pinfunction "C1_4") (pintype "bidirectional"))
    )
    (net (code "45") (name "/C30") (class "Default")
      (node (ref "R105") (pin "1") (pinfunction "1_1") (pintype "passive"))
      (node (ref "U27") (pin "6") (pinfunction "C2_6") (pintype "bidirectional"))
    )
    (net (code "46") (name "/C31") (class "Default")
      (node (ref "R106") (pin "1") (pinfunction "1_1") (pintype "passive"))
      (node (ref "U27") (pin "8") (pinfunction "C3_8") (pintype "bidirectional"))
    )
    (net (code "47") (name "/C32") (class "Default")
      (node (ref "R111") (pin "1") (pinfunction "1_1") (pintype "passive"))
      (node (ref "U28") (pin "2") (pinfunction "C0_2") (pintype "bidirectional"))
    )
    (net (code "48") (name "/C33") (class "Default")
      (node (ref "R112") (pin "1") (pinfunction "1_1") (pintype "passive"))
      (node (ref "U28") (pin "4") (pinfunction "C1_4") (pintype "bidirectional"))
    )
    (net (code "49") (name "/C34") (class "Default")
      (node (ref "R113") (pin "1") (pinfunction "1_1") (pintype "passive"))
      (node (ref "U28") (pin "6") (pinfunction "C2_6") (pintype "bidirectional"))
    )
    (net (code "50") (name "/C35") (class "Default")
      (node (ref "R114") (pin "1") (pinfunction "1_1") (pintype "passive"))
      (node (ref "U28") (pin "8") (pinfunction "C3_8") (pintype "bidirectional"))
    )
    (net (code "51") (name "/C36") (class "Default")
      (node (ref "R119") (pin "1") (pinfunction "1_1") (pintype "passive"))
      (node (ref "U29") (pin "2") (pinfunction "C0_2") (pintype "bidirectional"))
    )
    (net (code "52") (name "/C37") (class "Default")
      (node (ref "R120") (pin "1") (pinfunction "1_1") (pintype "passive"))
      (node (ref "U29") (pin "4") (pinfunction "C1_4") (pintype "bidirectional"))
    )
    (net (code "53") (name "/C38") (class "Default")
      (node (ref "R121") (pin "1") (pinfunction "1_1") (pintype "passive"))
      (node (ref "U29") (pin "6") (pinfunction "C2_6") (pintype "bidirectional"))
    )
    (net (code "54") (name "/C39") (class "Default")
      (node (ref "R122") (pin "1") (pinfunction "1_1") (pintype "passive"))
      (node (ref "U29") (pin "8") (pinfunction "C3_8") (pintype "bidirectional"))
    )
    (net (code "55") (name "/C40") (class "Default")
      (node (ref "R127") (pin "1") (pinfunction "1_1") (pintype "passive"))
      (node (ref "U30") (pin "2") (pinfunction "C0_2") (pintype "bidirectional"))
    )
    (net (code "56") (name "/C41") (class "Default")
      (node (ref "R128") (pin "1") (pinfunction "1_1") (pintype "passive"))
      (node (ref "U30") (pin "4") (pinfunction "C1_4") (pintype "bidirectional"))
    )
    (net (code "57") (name "/C42") (class "Default")
      (node (ref "R129") (pin "1") (pinfunction "1_1") (pintype "passive"))
      (node (ref "U30") (pin "6") (pinfunction "C2_6") (pintype "bidirectional"))
    )
    (net (code "58") (name "/C43") (class "Default")
      (node (ref "R130") (pin "1") (pinfunction "1_1") (pintype "passive"))
      (node (ref "U30") (pin "8") (pinfunction "C3_8") (pintype "bidirectional"))
    )
    (net (code "59") (name "/C44") (class "Default")
      (node (ref "R135") (pin "1") (pinfunction "1_1") (pintype "passive"))
      (node (ref "U31") (pin "2") (pinfunction "C0_2") (pintype "bidirectional"))
    )
    (net (code "60") (name "/C45") (class "Default")
      (node (ref "R136") (pin "1") (pinfunction "1_1") (pintype "passive"))
      (node (ref "U31") (pin "4") (pinfunction "C1_4") (pintype "bidirectional"))
    )
    (net (code "61") (name "/C46") (class "Default")
      (node (ref "R137") (pin "1") (pinfunction "1_1") (pintype "passive"))
      (node (ref "U31") (pin "6") (pinfunction "C2_6") (pintype "bidirectional"))
    )
    (net (code "62") (name "/C47") (class "Default")
      (node (ref "R138") (pin "1") (pinfunction "1_1") (pintype "passive"))
      (node (ref "U31") (pin "8") (pinfunction "C3_8") (pintype "bidirectional"))
    )
    (net (code "63") (name "/C48") (class "Default")
      (node (ref "R143") (pin "1") (pinfunction "1_1") (pintype "passive"))
      (node (ref "U32") (pin "2") (pinfunction "C0_2") (pintype "bidirectional"))
    )
    (net (code "64") (name "/C49") (class "Default")
      (node (ref "R144") (pin "1") (pinfunction "1_1") (pintype "passive"))
      (node (ref "U32") (pin "4") (pinfunction "C1_4") (pintype "bidirectional"))
    )
    (net (code "65") (name "/C50") (class "Default")
      (node (ref "R145") (pin "1") (pinfunction "1_1") (pintype "passive"))
      (node (ref "U32") (pin "6") (pinfunction "C2_6") (pintype "bidirectional"))
    )
    (net (code "66") (name "/C51") (class "Default")
      (node (ref "R146") (pin "1") (pinfunction "1_1") (pintype "passive"))
      (node (ref "U32") (pin "8") (pinfunction "C3_8") (pintype "bidirectional"))
    )
    (net (code "67") (name "/C52") (class "Default")
      (node (ref "R151") (pin "1") (pinfunction "1_1") (pintype "passive"))
      (node (ref "U33") (pin "2") (pinfunction "C0_2") (pintype "bidirectional"))
    )
    (net (code "68") (name "/C53") (class "Default")
      (node (ref "R152") (pin "1") (pinfunction "1_1") (pintype "passive"))
      (node (ref "U33") (pin "4") (pinfunction "C1_4") (pintype "bidirectional"))
    )
    (net (code "69") (name "/C54") (class "Default")
      (node (ref "R153") (pin "1") (pinfunction "1_1") (pintype "passive"))
      (node (ref "U33") (pin "6") (pinfunction "C2_6") (pintype "bidirectional"))
    )
    (net (code "70") (name "/C55") (class "Default")
      (node (ref "R154") (pin "1") (pinfunction "1_1") (pintype "passive"))
      (node (ref "U33") (pin "8") (pinfunction "C3_8") (pintype "bidirectional"))
    )
    (net (code "71") (name "/C56") (class "Default")
      (node (ref "R159") (pin "1") (pinfunction "1_1") (pintype "passive"))
      (node (ref "U34") (pin "2") (pinfunction "C0_2") (pintype "bidirectional"))
    )
    (net (code "72") (name "/C57") (class "Default")
      (node (ref "R160") (pin "1") (pinfunction "1_1") (pintype "passive"))
      (node (ref "U34") (pin "4") (pinfunction "C1_4") (pintype "bidirectional"))
    )
    (net (code "73") (name "/C58") (class "Default")
      (node (ref "R161") (pin "1") (pinfunction "1_1") (pintype "passive"))
      (node (ref "U34") (pin "6") (pinfunction "C2_6") (pintype "bidirectional"))
    )
    (net (code "74") (name "/C59") (class "Default")
      (node (ref "R162") (pin "1") (pinfunction "1_1") (pintype "passive"))
      (node (ref "U34") (pin "8") (pinfunction "C3_8") (pintype "bidirectional"))
    )
    (net (code "75") (name "/C60") (class "Default")
      (node (ref "R167") (pin "1") (pinfunction "1_1") (pintype "passive"))
      (node (ref "U35") (pin "2") (pinfunction "C0_2") (pintype "bidirectional"))
    )
    (net (code "76") (name "/C61") (class "Default")
      (node (ref "R168") (pin "1") (pinfunction "1_1") (pintype "passive"))
      (node (ref "U35") (pin "4") (pinfunction "C1_4") (pintype "bidirectional"))
    )
    (net (code "77") (name "/C62") (class "Default")
      (node (ref "R169") (pin "1") (pinfunction "1_1") (pintype "passive"))
      (node (ref "U35") (pin "6") (pinfunction "C2_6") (pintype "bidirectional"))
    )
    (net (code "78") (name "/C63") (class "Default")
      (node (ref "R170") (pin "1") (pinfunction "1_1") (pintype "passive"))
      (node (ref "U35") (pin "8") (pinfunction "C3_8") (pintype "bidirectional"))
    )
    (net (code "79") (name "/D+") (class "Default")
      (node (ref "U3") (pin "1") (pinfunction "I/O1A_1") (pintype "bidirectional"))
      (node (ref "USB") (pin "3") (pinfunction "D+_3") (pintype "bidirectional"))
    )
    (net (code "80") (name "/D-") (class "Default")
      (node (ref "U3") (pin "6") (pinfunction "I/O1B_6") (pintype "bidirectional"))
      (node (ref "USB") (pin "2") (pinfunction "D-_2") (pintype "bidirectional"))
    )
    (net (code "81") (name "/DATA_CLK") (class "Default")
      (node (ref "U1") (pin "3") (pinfunction "P6_3") (pintype "bidirectional"))
      (node (ref "U10") (pin "2") (pinfunction "CLK_2") (pintype "bidirectional"))
      (node (ref "U11") (pin "2") (pinfunction "CLK_2") (pintype "bidirectional"))
      (node (ref "U12") (pin "2") (pinfunction "CLK_2") (pintype "bidirectional"))
      (node (ref "U13") (pin "2") (pinfunction "CLK_2") (pintype "bidirectional"))
      (node (ref "U14") (pin "2") (pinfunction "CLK_2") (pintype "bidirectional"))
      (node (ref "U15") (pin "2") (pinfunction "CLK_2") (pintype "bidirectional"))
      (node (ref "U16") (pin "2") (pinfunction "CLK_2") (pintype "bidirectional"))
      (node (ref "U39") (pin "12") (pinfunction "STCP_12") (pintype "bidirectional"))
      (node (ref "U40") (pin "12") (pinfunction "STCP_12") (pintype "bidirectional"))
      (node (ref "U41") (pin "12") (pinfunction "STCP_12") (pintype "bidirectional"))
      (node (ref "U42") (pin "12") (pinfunction "STCP_12") (pintype "bidirectional"))
      (node (ref "U5") (pin "12") (pinfunction "STCP_12") (pintype "bidirectional"))
      (node (ref "U6") (pin "12") (pinfunction "STCP_12") (pintype "bidirectional"))
      (node (ref "U7") (pin "12") (pinfunction "STCP_12") (pintype "bidirectional"))
      (node (ref "U8") (pin "12") (pinfunction "STCP_12") (pintype "bidirectional"))
      (node (ref "U80") (pin "4") (pinfunction "I/O2B_4") (pintype "bidirectional"))
      (node (ref "U81") (pin "7") (pinfunction "/ST_7") (pintype "bidirectional"))
      (node (ref "U9") (pin "2") (pinfunction "CLK_2") (pintype "bidirectional"))
    )
    (net (code "82") (name "/DATA_CLK_OUT") (class "Default")
      (node (ref "AUX") (pin "3") (pinfunction "3_3") (pintype "bidirectional"))
      (node (ref "U80") (pin "6") (pinfunction "I/O1B_6") (pintype "bidirectional"))
    )
    (net (code "83") (name "/DATA_IN") (class "Default")
      (node (ref "U1") (pin "2") (pinfunction "P5_2") (pintype "bidirectional"))
      (node (ref "U9") (pin "9") (pinfunction "QH_9") (pintype "bidirectional"))
    )
    (net (code "84") (name "/DATA_IN1") (class "Default")
      (node (ref "U10") (pin "9") (pinfunction "QH_9") (pintype "bidirectional"))
      (node (ref "U9") (pin "10") (pinfunction "SER_10") (pintype "bidirectional"))
    )
    (net (code "85") (name "/DATA_IN2") (class "Default")
      (node (ref "U10") (pin "10") (pinfunction "SER_10") (pintype "bidirectional"))
      (node (ref "U11") (pin "9") (pinfunction "QH_9") (pintype "bidirectional"))
    )
    (net (code "86") (name "/DATA_IN3") (class "Default")
      (node (ref "U11") (pin "10") (pinfunction "SER_10") (pintype "bidirectional"))
      (node (ref "U12") (pin "9") (pinfunction "QH_9") (pintype "bidirectional"))
    )
    (net (code "87") (name "/DATA_IN4") (class "Default")
      (node (ref "U12") (pin "10") (pinfunction "SER_10") (pintype "bidirectional"))
      (node (ref "U13") (pin "9") (pinfunction "QH_9") (pintype "bidirectional"))
    )
    (net (code "88") (name "/DATA_IN5") (class "Default")
      (node (ref "U13") (pin "10") (pinfunction "SER_10") (pintype "bidirectional"))
      (node (ref "U14") (pin "9") (pinfunction "QH_9") (pintype "bidirectional"))
    )
    (net (code "89") (name "/DATA_IN6") (class "Default")
      (node (ref "U14") (pin "10") (pinfunction "SER_10") (pintype "bidirectional"))
      (node (ref "U15") (pin "9") (pinfunction "QH_9") (pintype "bidirectional"))
    )
    (net (code "90") (name "/DATA_IN7") (class "Default")
      (node (ref "U15") (pin "10") (pinfunction "SER_10") (pintype "bidirectional"))
      (node (ref "U16") (pin "9") (pinfunction "QH_9") (pintype "bidirectional"))
    )
    (net (code "91") (name "/DATA_IN8") (class "Default")
      (node (ref "U16") (pin "10") (pinfunction "SER_10") (pintype "bidirectional"))
      (node (ref "U79") (pin "4") (pinfunction "I/O2B_4") (pintype "bidirectional"))
    )
    (net (code "92") (name "/DATA_IN8_OUT") (class "Default")
      (node (ref "AUX") (pin "5") (pinfunction "5_5") (pintype "bidirectional"))
      (node (ref "U79") (pin "6") (pinfunction "I/O1B_6") (pintype "bidirectional"))
    )
    (net (code "93") (name "/DATA_LAT") (class "Default")
      (node (ref "U1") (pin "4") (pinfunction "P7_4") (pintype "bidirectional"))
      (node (ref "U10") (pin "1") (pinfunction "LAT_1") (pintype "bidirectional"))
      (node (ref "U11") (pin "1") (pinfunction "LAT_1") (pintype "bidirectional"))
      (node (ref "U12") (pin "1") (pinfunction "LAT_1") (pintype "bidirectional"))
      (node (ref "U13") (pin "1") (pinfunction "LAT_1") (pintype "bidirectional"))
      (node (ref "U14") (pin "1") (pinfunction "LAT_1") (pintype "bidirectional"))
      (node (ref "U15") (pin "1") (pinfunction "LAT_1") (pintype "bidirectional"))
      (node (ref "U16") (pin "1") (pinfunction "LAT_1") (pintype "bidirectional"))
      (node (ref "U39") (pin "11") (pinfunction "SHCP_11") (pintype "bidirectional"))
      (node (ref "U40") (pin "11") (pinfunction "SHCP_11") (pintype "bidirectional"))
      (node (ref "U41") (pin "11") (pinfunction "SHCP_11") (pintype "bidirectional"))
      (node (ref "U42") (pin "11") (pinfunction "SHCP_11") (pintype "bidirectional"))
      (node (ref "U5") (pin "11") (pinfunction "SHCP_11") (pintype "bidirectional"))
      (node (ref "U6") (pin "11") (pinfunction "SHCP_11") (pintype "bidirectional"))
      (node (ref "U7") (pin "11") (pinfunction "SHCP_11") (pintype "bidirectional"))
      (node (ref "U8") (pin "11") (pinfunction "SHCP_11") (pintype "bidirectional"))
      (node (ref "U80") (pin "3") (pinfunction "I/O2A_3") (pintype "bidirectional"))
      (node (ref "U9") (pin "1") (pinfunction "LAT_1") (pintype "bidirectional"))
    )
    (net (code "94") (name "/DATA_LAT_OUT") (class "Default")
      (node (ref "AUX") (pin "2") (pinfunction "2_2") (pintype "bidirectional"))
      (node (ref "U80") (pin "1") (pinfunction "I/O1A_1") (pintype "bidirectional"))
    )
    (net (code "95") (name "/DATA_OUT") (class "Default")
      (node (ref "U1") (pin "1") (pinfunction "P4_1") (pintype "bidirectional"))
      (node (ref "U5") (pin "14") (pinfunction "DS_14") (pintype "bidirectional"))
    )
    (net (code "96") (name "/DATA_OUT1") (class "Default")
      (node (ref "U5") (pin "9") (pinfunction "Q7S_9") (pintype "bidirectional"))
      (node (ref "U6") (pin "14") (pinfunction "DS_14") (pintype "bidirectional"))
    )
    (net (code "97") (name "/DATA_OUT2") (class "Default")
      (node (ref "U6") (pin "9") (pinfunction "Q7S_9") (pintype "bidirectional"))
      (node (ref "U7") (pin "14") (pinfunction "DS_14") (pintype "bidirectional"))
    )
    (net (code "98") (name "/DATA_OUT3") (class "Default")
      (node (ref "U7") (pin "9") (pinfunction "Q7S_9") (pintype "bidirectional"))
      (node (ref "U8") (pin "14") (pinfunction "DS_14") (pintype "bidirectional"))
    )
    (net (code "99") (name "/DATA_OUT4") (class "Default")
      (node (ref "U39") (pin "14") (pinfunction "DS_14") (pintype "bidirectional"))
      (node (ref "U8") (pin "9") (pinfunction "Q7S_9") (pintype "bidirectional"))
    )
    (net (code "100") (name "/DATA_OUT5") (class "Default")
      (node (ref "U39") (pin "9") (pinfunction "Q7S_9") (pintype "bidirectional"))
      (node (ref "U40") (pin "14") (pinfunction "DS_14") (pintype "bidirectional"))
    )
    (net (code "101") (name "/DATA_OUT6") (class "Default")
      (node (ref "U40") (pin "9") (pinfunction "Q7S_9") (pintype "bidirectional"))
      (node (ref "U41") (pin "14") (pinfunction "DS_14") (pintype "bidirectional"))
    )
    (net (code "102") (name "/DATA_OUT7") (class "Default")
      (node (ref "U41") (pin "9") (pinfunction "Q7S_9") (pintype "bidirectional"))
      (node (ref "U42") (pin "14") (pinfunction "DS_14") (pintype "bidirectional"))
    )
    (net (code "103") (name "/DATA_OUT8") (class "Default")
      (node (ref "U42") (pin "9") (pinfunction "Q7S_9") (pintype "bidirectional"))
      (node (ref "U79") (pin "3") (pinfunction "I/O2A_3") (pintype "bidirectional"))
    )
    (net (code "104") (name "/DATA_OUT8_OUT") (class "Default")
      (node (ref "AUX") (pin "4") (pinfunction "4_4") (pintype "bidirectional"))
      (node (ref "U79") (pin "1") (pinfunction "I/O1A_1") (pintype "bidirectional"))
    )
    (net (code "105") (name "/DMD0") (class "Default")
      (node (ref "U1") (pin "14") (pinfunction "P13_14") (pintype "bidirectional"))
      (node (ref "U78") (pin "3") (pinfunction "I/O2A_3") (pintype "bidirectional"))
    )
    (net (code "106") (name "/DMD1") (class "Default")
      (node (ref "U1") (pin "13") (pinfunction "P12_13") (pintype "bidirectional"))
      (node (ref "U78") (pin "4") (pinfunction "I/O2B_4") (pintype "bidirectional"))
    )
    (net (code "107") (name "/DMD2") (class "Default")
      (node (ref "U1") (pin "12") (pinfunction "P11_12") (pintype "bidirectional"))
      (node (ref "U77") (pin "3") (pinfunction "I/O2A_3") (pintype "bidirectional"))
    )
    (net (code "108") (name "/DMD3") (class "Default")
      (node (ref "U1") (pin "11") (pinfunction "P10_11") (pintype "bidirectional"))
      (node (ref "U77") (pin "4") (pinfunction "I/O2B_4") (pintype "bidirectional"))
    )
    (net (code "109") (name "/DMD4") (class "Default")
      (node (ref "U1") (pin "10") (pinfunction "P9_10") (pintype "bidirectional"))
      (node (ref "U76") (pin "3") (pinfunction "I/O2A_3") (pintype "bidirectional"))
    )
    (net (code "110") (name "/DMD5") (class "Default")
      (node (ref "U1") (pin "9") (pinfunction "P8_9") (pintype "bidirectional"))
      (node (ref "U76") (pin "4") (pinfunction "I/O2B_4") (pintype "bidirectional"))
    )
    (net (code "111") (name "/DMD_OUT0") (class "Default")
      (node (ref "DMD_CONN") (pin "1") (pinfunction "1_1") (pintype "bidirectional"))
      (node (ref "U78") (pin "1") (pinfunction "I/O1A_1") (pintype "bidirectional"))
    )
    (net (code "112") (name "/DMD_OUT1") (class "Default")
      (node (ref "DMD_CONN") (pin "2") (pinfunction "2_2") (pintype "bidirectional"))
      (node (ref "U78") (pin "6") (pinfunction "I/O1B_6") (pintype "bidirectional"))
    )
    (net (code "113") (name "/DMD_OUT2") (class "Default")
      (node (ref "DMD_CONN") (pin "3") (pinfunction "3_3") (pintype "bidirectional"))
      (node (ref "U77") (pin "1") (pinfunction "I/O1A_1") (pintype "bidirectional"))
    )
    (net (code "114") (name "/DMD_OUT3") (class "Default")
      (node (ref "DMD_CONN") (pin "4") (pinfunction "4_4") (pintype "bidirectional"))
      (node (ref "U77") (pin "6") (pinfunction "I/O1B_6") (pintype "bidirectional"))
    )
    (net (code "115") (name "/DMD_OUT4") (class "Default")
      (node (ref "DMD_CONN") (pin "5") (pinfunction "5_5") (pintype "bidirectional"))
      (node (ref "U76") (pin "1") (pinfunction "I/O1A_1") (pintype "bidirectional"))
    )
    (net (code "116") (name "/DMD_OUT5") (class "Default")
      (node (ref "DMD_CONN") (pin "6") (pinfunction "6_6") (pintype "bidirectional"))
      (node (ref "U76") (pin "6") (pinfunction "I/O1B_6") (pintype "bidirectional"))
    )
    (net (code "117") (name "/GND") (class "Default")
      (node (ref "ANALOG_0") (pin "2") (pinfunction "2_2") (pintype "passive"))
      (node (ref "ANALOG_1") (pin "2") (pinfunction "2_2") (pintype "passive"))
      (node (ref "ANALOG_2") (pin "2") (pinfunction "2_2") (pintype "passive"))
      (node (ref "ANALOG_3") (pin "2") (pinfunction "2_2") (pintype "passive"))
      (node (ref "AUDIO") (pin "1") (pinfunction "S_1") (pintype "bidirectional"))
      (node (ref "AUX") (pin "10") (pinfunction "10_10") (pintype "bidirectional"))
      (node (ref "AUX") (pin "11") (pinfunction "11_11") (pintype "bidirectional"))
      (node (ref "AUX") (pin "12") (pinfunction "12_12") (pintype "bidirectional"))
      (node (ref "AUX") (pin "13") (pinfunction "13_13") (pintype "bidirectional"))
      (node (ref "AUX") (pin "14") (pinfunction "14_14") (pintype "bidirectional"))
      (node (ref "AUX") (pin "8") (pinfunction "8_8") (pintype "bidirectional"))
      (node (ref "AUX") (pin "9") (pinfunction "9_9") (pintype "bidirectional"))
      (node (ref "C1") (pin "2") (pinfunction "2_2") (pintype "passive"))
      (node (ref "C10") (pin "1") (pinfunction "1_1") (pintype "passive"))
      (node (ref "C11") (pin "1") (pinfunction "1_1") (pintype "passive"))
      (node (ref "C12") (pin "1") (pinfunction "1_1") (pintype "passive"))
      (node (ref "C13") (pin "1") (pinfunction "1_1") (pintype "passive"))
      (node (ref "C14") (pin "1") (pinfunction "1_1") (pintype "passive"))
      (node (ref "C15") (pin "1") (pinfunction "1_1") (pintype "passive"))
      (node (ref "C16") (pin "1") (pinfunction "1_1") (pintype "passive"))
      (node (ref "C17") (pin "1") (pinfunction "1_1") (pintype "passive"))
      (node (ref "C18") (pin "1") (pinfunction "1_1") (pintype "passive"))
      (node (ref "C19") (pin "1") (pinfunction "1_1") (pintype "passive"))
      (node (ref "C2") (pin "2") (pinfunction "2_2") (pintype "passive"))
      (node (ref "C20") (pin "1") (pinfunction "1_1") (pintype "passive"))
      (node (ref "C21") (pin "2") (pinfunction "2_2") (pintype "passive"))
      (node (ref "C22") (pin "1") (pinfunction "1_1") (pintype "passive"))
      (node (ref "C23") (pin "1") (pinfunction "1_1") (pintype "passive"))
      (node (ref "C24") (pin "1") (pinfunction "1_1") (pintype "passive"))
      (node (ref "C25") (pin "1") (pinfunction "1_1") (pintype "passive"))
      (node (ref "C26") (pin "1") (pinfunction "1_1") (pintype "passive"))
      (node (ref "C27") (pin "1") (pinfunction "1_1") (pintype "passive"))
      (node (ref "C28") (pin "1") (pinfunction "1_1") (pintype "passive"))
      (node (ref "C29") (pin "1") (pinfunction "1_1") (pintype "passive"))
      (node (ref "C3") (pin "1") (pinfunction "1_1") (pintype "passive"))
      (node (ref "C30") (pin "1") (pinfunction "1_1") (pintype "passive"))
      (node (ref "C31") (pin "1") (pinfunction "1_1") (pintype "passive"))
      (node (ref "C32") (pin "-") (pinfunction "NEG_-") (pintype "bidirectional"))
      (node (ref "C33") (pin "-") (pinfunction "NEG_-") (pintype "bidirectional"))
      (node (ref "C34") (pin "NEG") (pinfunction "NEG_NEG") (pintype "bidirectional"))
      (node (ref "C35") (pin "2") (pinfunction "2_2") (pintype "passive"))
      (node (ref "C36") (pin "2") (pinfunction "2_2") (pintype "passive"))
      (node (ref "C37") (pin "-") (pinfunction "NEG_-") (pintype "bidirectional"))
      (node (ref "C38") (pin "-") (pinfunction "NEG_-") (pintype "bidirectional"))
      (node (ref "C39") (pin "NEG") (pinfunction "NEG_NEG") (pintype "bidirectional"))
      (node (ref "C4") (pin "1") (pinfunction "1_1") (pintype "passive"))
      (node (ref "C40") (pin "2") (pinfunction "2_2") (pintype "passive"))
      (node (ref "C41") (pin "2") (pinfunction "2_2") (pintype "passive"))
      (node (ref "C44") (pin "2") (pinfunction "2_2") (pintype "passive"))
      (node (ref "C45") (pin "1") (pinfunction "1_1") (pintype "passive"))
      (node (ref "C46") (pin "1") (pinfunction "1_1") (pintype "passive"))
      (node (ref "C47") (pin "1") (pinfunction "1_1") (pintype "passive"))
      (node (ref "C48") (pin "1") (pinfunction "1_1") (pintype "passive"))
      (node (ref "C49") (pin "1") (pinfunction "1_1") (pintype "passive"))
      (node (ref "C5") (pin "1") (pinfunction "1_1") (pintype "passive"))
      (node (ref "C50") (pin "1") (pinfunction "1_1") (pintype "passive"))
      (node (ref "C51") (pin "1") (pinfunction "1_1") (pintype "passive"))
      (node (ref "C52") (pin "1") (pinfunction "1_1") (pintype "passive"))
      (node (ref "C53") (pin "1") (pinfunction "1_1") (pintype "passive"))
      (node (ref "C54") (pin "-") (pinfunction "NEG_-") (pintype "bidirectional"))
      (node (ref "C55") (pin "-") (pinfunction "NEG_-") (pintype "bidirectional"))
      (node (ref "C56") (pin "NEG") (pinfunction "NEG_NEG") (pintype "bidirectional"))
      (node (ref "C57") (pin "2") (pinfunction "2_2") (pintype "passive"))
      (node (ref "C58") (pin "2") (pinfunction "2_2") (pintype "passive"))
      (node (ref "C59") (pin "1") (pinfunction "1_1") (pintype "passive"))
      (node (ref "C6") (pin "1") (pinfunction "1_1") (pintype "passive"))
      (node (ref "C60") (pin "1") (pinfunction "1_1") (pintype "passive"))
      (node (ref "C61") (pin "1") (pinfunction "1_1") (pintype "passive"))
      (node (ref "C65") (pin "NEG") (pinfunction "NEG_NEG") (pintype "bidirectional"))
      (node (ref "C66") (pin "1") (pinfunction "1_1") (pintype "passive"))
      (node (ref "C67") (pin "1") (pinfunction "1_1") (pintype "passive"))
      (node (ref "C68") (pin "1") (pinfunction "1_1") (pintype "passive"))
      (node (ref "C69") (pin "1") (pinfunction "1_1") (pintype "passive"))
      (node (ref "C8") (pin "1") (pinfunction "1_1") (pintype "passive"))
      (node (ref "C9") (pin "1") (pinfunction "1_1") (pintype "passive"))
      (node (ref "D4") (pin "C") (pinfunction "C_C") (pintype "passive"))
      (node (ref "DMD_CONN") (pin "10") (pinfunction "10_10") (pintype "bidirectional"))
      (node (ref "DMD_CONN") (pin "11") (pinfunction "11_11") (pintype "bidirectional"))
      (node (ref "DMD_CONN") (pin "12") (pinfunction "12_12") (pintype "bidirectional"))
      (node (ref "DMD_CONN") (pin "13") (pinfunction "13_13") (pintype "bidirectional"))
      (node (ref "DMD_CONN") (pin "14") (pinfunction "14_14") (pintype "bidirectional"))
      (node (ref "DMD_CONN") (pin "8") (pinfunction "8_8") (pintype "bidirectional"))
      (node (ref "DMD_CONN") (pin "9") (pinfunction "9_9") (pintype "bidirectional"))
      (node (ref "DMD_PWR") (pin "P$1") (pinfunction "1_P$1") (pintype "passive"))
      (node (ref "PC_POWER_SUPPLY") (pin "10") (pinfunction "10_10") (pintype "bidirectional"))
      (node (ref "PC_POWER_SUPPLY") (pin "12") (pinfunction "12_12") (pintype "bidirectional"))
      (node (ref "PC_POWER_SUPPLY") (pin "13") (pinfunction "13_13") (pintype "bidirectional"))
      (node (ref "PC_POWER_SUPPLY") (pin "14") (pinfunction "14_14") (pintype "bidirectional"))
      (node (ref "PC_POWER_SUPPLY") (pin "5") (pinfunction "5_5") (pintype "bidirectional"))
      (node (ref "PC_POWER_SUPPLY") (pin "6") (pinfunction "6_6") (pintype "bidirectional"))
      (node (ref "PC_POWER_SUPPLY") (pin "9") (pinfunction "9_9") (pintype "bidirectional"))
      (node (ref "R1") (pin "1") (pinfunction "1_1") (pintype "passive"))
      (node (ref "R100") (pin "1") (pinfunction "1_1") (pintype "passive"))
      (node (ref "R101") (pin "1") (pinfunction "1_1") (pintype "passive"))
      (node (ref "R102") (pin "1") (pinfunction "1_1") (pintype "passive"))
      (node (ref "R103") (pin "2") (pinfunction "2_2") (pintype "passive"))
      (node (ref "R104") (pin "2") (pinfunction "2_2") (pintype "passive"))
      (node (ref "R105") (pin "2") (pinfunction "2_2") (pintype "passive"))
      (node (ref "R106") (pin "2") (pinfunction "2_2") (pintype "passive"))
      (node (ref "R107") (pin "1") (pinfunction "1_1") (pintype "passive"))
      (node (ref "R108") (pin "1") (pinfunction "1_1") (pintype "passive"))
      (node (ref "R109") (pin "1") (pinfunction "1_1") (pintype "passive"))
      (node (ref "R110") (pin "1") (pinfunction "1_1") (pintype "passive"))
      (node (ref "R111") (pin "2") (pinfunction "2_2") (pintype "passive"))
      (node (ref "R112") (pin "2") (pinfunction "2_2") (pintype "passive"))
      (node (ref "R113") (pin "2") (pinfunction "2_2") (pintype "passive"))
      (node (ref "R114") (pin "2") (pinfunction "2_2") (pintype "passive"))
      (node (ref "R115") (pin "1") (pinfunction "1_1") (pintype "passive"))
      (node (ref "R116") (pin "1") (pinfunction "1_1") (pintype "passive"))
      (node (ref "R117") (pin "1") (pinfunction "1_1") (pintype "passive"))
      (node (ref "R118") (pin "1") (pinfunction "1_1") (pintype "passive"))
      (node (ref "R119") (pin "2") (pinfunction "2_2") (pintype "passive"))
      (node (ref "R12") (pin "2") (pinfunction "2_2") (pintype "passive"))
      (node (ref "R120") (pin "2") (pinfunction "2_2") (pintype "passive"))
      (node (ref "R121") (pin "2") (pinfunction "2_2") (pintype "passive"))
      (node (ref "R122") (pin "2") (pinfunction "2_2") (pintype "passive"))
      (node (ref "R123") (pin "1") (pinfunction "1_1") (pintype "passive"))
      (node (ref "R124") (pin "1") (pinfunction "1_1") (pintype "passive"))
      (node (ref "R125") (pin "1") (pinfunction "1_1") (pintype "passive"))
      (node (ref "R126") (pin "1") (pinfunction "1_1") (pintype "passive"))
      (node (ref "R127") (pin "2") (pinfunction "2_2") (pintype "passive"))
      (node (ref "R128") (pin "2") (pinfunction "2_2") (pintype "passive"))
      (node (ref "R129") (pin "2") (pinfunction "2_2") (pintype "passive"))
      (node (ref "R13") (pin "2") (pinfunction "2_2") (pintype "passive"))
      (node (ref "R130") (pin "2") (pinfunction "2_2") (pintype "passive"))
      (node (ref "R131") (pin "1") (pinfunction "1_1") (pintype "passive"))
      (node (ref "R132") (pin "1") (pinfunction "1_1") (pintype "passive"))
      (node (ref "R133") (pin "1") (pinfunction "1_1") (pintype "passive"))
      (node (ref "R134") (pin "1") (pinfunction "1_1") (pintype "passive"))
      (node (ref "R135") (pin "2") (pinfunction "2_2") (pintype "passive"))
      (node (ref "R136") (pin "2") (pinfunction "2_2") (pintype "passive"))
      (node (ref "R137") (pin "2") (pinfunction "2_2") (pintype "passive"))
      (node (ref "R138") (pin "2") (pinfunction "2_2") (pintype "passive"))
      (node (ref "R139") (pin "1") (pinfunction "1_1") (pintype "passive"))
      (node (ref "R14") (pin "2") (pinfunction "2_2") (pintype "passive"))
      (node (ref "R140") (pin "1") (pinfunction "1_1") (pintype "passive"))
      (node (ref "R141") (pin "1") (pinfunction "1_1") (pintype "passive"))
      (node (ref "R142") (pin "1") (pinfunction "1_1") (pintype "passive"))
      (node (ref "R143") (pin "2") (pinfunction "2_2") (pintype "passive"))
      (node (ref "R144") (pin "2") (pinfunction "2_2") (pintype "passive"))
      (node (ref "R145") (pin "2") (pinfunction "2_2") (pintype "passive"))
      (node (ref "R146") (pin "2") (pinfunction "2_2") (pintype "passive"))
      (node (ref "R147") (pin "1") (pinfunction "1_1") (pintype "passive"))
      (node (ref "R148") (pin "1") (pinfunction "1_1") (pintype "passive"))
      (node (ref "R149") (pin "1") (pinfunction "1_1") (pintype "passive"))
      (node (ref "R15") (pin "1") (pinfunction "1_1") (pintype "passive"))
      (node (ref "R150") (pin "1") (pinfunction "1_1") (pintype "passive"))
      (node (ref "R151") (pin "2") (pinfunction "2_2") (pintype "passive"))
      (node (ref "R152") (pin "2") (pinfunction "2_2") (pintype "passive"))
      (node (ref "R153") (pin "2") (pinfunction "2_2") (pintype "passive"))
      (node (ref "R154") (pin "2") (pinfunction "2_2") (pintype "passive"))
      (node (ref "R155") (pin "1") (pinfunction "1_1") (pintype "passive"))
      (node (ref "R156") (pin "1") (pinfunction "1_1") (pintype "passive"))
      (node (ref "R157") (pin "1") (pinfunction "1_1") (pintype "passive"))
      (node (ref "R158") (pin "1") (pinfunction "1_1") (pintype "passive"))
      (node (ref "R159") (pin "2") (pinfunction "2_2") (pintype "passive"))
      (node (ref "R16") (pin "1") (pinfunction "1_1") (pintype "passive"))
      (node (ref "R160") (pin "2") (pinfunction "2_2") (pintype "passive"))
      (node (ref "R161") (pin "2") (pinfunction "2_2") (pintype "passive"))
      (node (ref "R162") (pin "2") (pinfunction "2_2") (pintype "passive"))
      (node (ref "R163") (pin "1") (pinfunction "1_1") (pintype "passive"))
      (node (ref "R164") (pin "1") (pinfunction "1_1") (pintype "passive"))
      (node (ref "R165") (pin "1") (pinfunction "1_1") (pintype "passive"))
      (node (ref "R166") (pin "1") (pinfunction "1_1") (pintype "passive"))
      (node (ref "R167") (pin "2") (pinfunction "2_2") (pintype "passive"))
      (node (ref "R168") (pin "2") (pinfunction "2_2") (pintype "passive"))
      (node (ref "R169") (pin "2") (pinfunction "2_2") (pintype "passive"))
      (node (ref "R17") (pin "1") (pinfunction "1_1") (pintype "passive"))
      (node (ref "R170") (pin "2") (pinfunction "2_2") (pintype "passive"))
      (node (ref "R171") (pin "1") (pinfunction "1_1") (pintype "passive"))
      (node (ref "R172") (pin "1") (pinfunction "1_1") (pintype "passive"))
      (node (ref "R173") (pin "1") (pinfunction "1_1") (pintype "passive"))
      (node (ref "R174") (pin "1") (pinfunction "1_1") (pintype "passive"))
      (node (ref "R175") (pin "2") (pinfunction "2_2") (pintype "passive"))
      (node (ref "R179") (pin "2") (pinfunction "2_2") (pintype "passive"))
      (node (ref "R18") (pin "1") (pinfunction "1_1") (pintype "passive"))
      (node (ref "R182") (pin "2") (pinfunction "2_2") (pintype "passive"))
      (node (ref "R183") (pin "2") (pinfunction "2_2") (pintype "passive"))
      (node (ref "R187") (pin "1") (pinfunction "1_1") (pintype "passive"))
      (node (ref "R189") (pin "2") (pinfunction "2_2") (pintype "passive"))
      (node (ref "R19") (pin "1") (pinfunction "1_1") (pintype "passive"))
      (node (ref "R20") (pin "1") (pinfunction "1_1") (pintype "passive"))
      (node (ref "R21") (pin "1") (pinfunction "1_1") (pintype "passive"))
      (node (ref "R22") (pin "1") (pinfunction "1_1") (pintype "passive"))
      (node (ref "R23") (pin "1") (pinfunction "1_1") (pintype "passive"))
      (node (ref "R24") (pin "1") (pinfunction "1_1") (pintype "passive"))
      (node (ref "R25") (pin "1") (pinfunction "1_1") (pintype "passive"))
      (node (ref "R26") (pin "1") (pinfunction "1_1") (pintype "passive"))
      (node (ref "R27") (pin "1") (pinfunction "1_1") (pintype "passive"))
      (node (ref "R28") (pin "1") (pinfunction "1_1") (pintype "passive"))
      (node (ref "R29") (pin "1") (pinfunction "1_1") (pintype "passive"))
      (node (ref "R30") (pin "1") (pinfunction "1_1") (pintype "passive"))
      (node (ref "R31") (pin "1") (pinfunction "1_1") (pintype "passive"))
      (node (ref "R32") (pin "1") (pinfunction "1_1") (pintype "passive"))
      (node (ref "R33") (pin "1") (pinfunction "1_1") (pintype "passive"))
      (node (ref "R34") (pin "1") (pinfunction "1_1") (pintype "passive"))
      (node (ref "R35") (pin "1") (pinfunction "1_1") (pintype "passive"))
      (node (ref "R36") (pin "1") (pinfunction "1_1") (pintype "passive"))
      (node (ref "R37") (pin "1") (pinfunction "1_1") (pintype "passive"))
      (node (ref "R38") (pin "1") (pinfunction "1_1") (pintype "passive"))
      (node (ref "R39") (pin "1") (pinfunction "1_1") (pintype "passive"))
      (node (ref "R40") (pin "1") (pinfunction "1_1") (pintype "passive"))
      (node (ref "R41") (pin "1") (pinfunction "1_1") (pintype "passive"))
      (node (ref "R42") (pin "1") (pinfunction "1_1") (pintype "passive"))
      (node (ref "R43") (pin "1") (pinfunction "1_1") (pintype "passive"))
      (node (ref "R44") (pin "1") (pinfunction "1_1") (pintype "passive"))
      (node (ref "R45") (pin "1") (pinfunction "1_1") (pintype "passive"))
      (node (ref "R46") (pin "1") (pinfunction "1_1") (pintype "passive"))
      (node (ref "R47") (pin "2") (pinfunction "2_2") (pintype "passive"))
      (node (ref "R48") (pin "2") (pinfunction "2_2") (pintype "passive"))
      (node (ref "R49") (pin "2") (pinfunction "2_2") (pintype "passive"))
      (node (ref "R50") (pin "2") (pinfunction "2_2") (pintype "passive"))
      (node (ref "R51") (pin "1") (pinfunction "1_1") (pintype "passive"))
      (node (ref "R52") (pin "1") (pinfunction "1_1") (pintype "passive"))
      (node (ref "R53") (pin "1") (pinfunction "1_1") (pintype "passive"))
      (node (ref "R54") (pin "1") (pinfunction "1_1") (pintype "passive"))
      (node (ref "R55") (pin "2") (pinfunction "2_2") (pintype "passive"))
      (node (ref "R56") (pin "2") (pinfunction "2_2") (pintype "passive"))
      (node (ref "R57") (pin "2") (pinfunction "2_2") (pintype "passive"))
      (node (ref "R58") (pin "2") (pinfunction "2_2") (pintype "passive"))
      (node (ref "R59") (pin "1") (pinfunction "1_1") (pintype "passive"))
      (node (ref "R60") (pin "1") (pinfunction "1_1") (pintype "passive"))
      (node (ref "R61") (pin "1") (pinfunction "1_1") (pintype "passive"))
      (node (ref "R62") (pin "1") (pinfunction "1_1") (pintype "passive"))
      (node (ref "R63") (pin "2") (pinfunction "2_2") (pintype "passive"))
      (node (ref "R64") (pin "2") (pinfunction "2_2") (pintype "passive"))
      (node (ref "R65") (pin "2") (pinfunction "2_2") (pintype "passive"))
      (node (ref "R66") (pin "2") (pinfunction "2_2") (pintype "passive"))
      (node (ref "R67") (pin "1") (pinfunction "1_1") (pintype "passive"))
      (node (ref "R68") (pin "1") (pinfunction "1_1") (pintype "passive"))
      (node (ref "R69") (pin "1") (pinfunction "1_1") (pintype "passive"))
      (node (ref "R70") (pin "1") (pinfunction "1_1") (pintype "passive"))
      (node (ref "R71") (pin "2") (pinfunction "2_2") (pintype "passive"))
      (node (ref "R72") (pin "2") (pinfunction "2_2") (pintype "passive"))
      (node (ref "R73") (pin "2") (pinfunction "2_2") (pintype "passive"))
      (node (ref "R74") (pin "2") (pinfunction "2_2") (pintype "passive"))
      (node (ref "R75") (pin "1") (pinfunction "1_1") (pintype "passive"))
      (node (ref "R76") (pin "1") (pinfunction "1_1") (pintype "passive"))
      (node (ref "R77") (pin "1") (pinfunction "1_1") (pintype "passive"))
      (node (ref "R78") (pin "1") (pinfunction "1_1") (pintype "passive"))
      (node (ref "R79") (pin "2") (pinfunction "2_2") (pintype "passive"))
      (node (ref "R80") (pin "2") (pinfunction "2_2") (pintype "passive"))
      (node (ref "R81") (pin "2") (pinfunction "2_2") (pintype "passive"))
      (node (ref "R82") (pin "2") (pinfunction "2_2") (pintype "passive"))
      (node (ref "R83") (pin "1") (pinfunction "1_1") (pintype "passive"))
      (node (ref "R84") (pin "1") (pinfunction "1_1") (pintype "passive"))
      (node (ref "R85") (pin "1") (pinfunction "1_1") (pintype "passive"))
      (node (ref "R86") (pin "1") (pinfunction "1_1") (pintype "passive"))
      (node (ref "R87") (pin "2") (pinfunction "2_2") (pintype "passive"))
      (node (ref "R88") (pin "2") (pinfunction "2_2") (pintype "passive"))
      (node (ref "R89") (pin "2") (pinfunction "2_2") (pintype "passive"))
      (node (ref "R90") (pin "2") (pinfunction "2_2") (pintype "passive"))
      (node (ref "R91") (pin "1") (pinfunction "1_1") (pintype "passive"))
      (node (ref "R92") (pin "1") (pinfunction "1_1") (pintype "passive"))
      (node (ref "R93") (pin "1") (pinfunction "1_1") (pintype "passive"))
      (node (ref "R94") (pin "1") (pinfunction "1_1") (pintype "passive"))
      (node (ref "R95") (pin "2") (pinfunction "2_2") (pintype "passive"))
      (node (ref "R96") (pin "2") (pinfunction "2_2") (pintype "passive"))
      (node (ref "R97") (pin "2") (pinfunction "2_2") (pintype "passive"))
      (node (ref "R98") (pin "2") (pinfunction "2_2") (pintype "passive"))
      (node (ref "R99") (pin "1") (pinfunction "1_1") (pintype "passive"))
      (node (ref "RESET") (pin "1") (pinfunction "A_1") (pintype "bidirectional"))
      (node (ref "RGB_CONN") (pin "3") (pinfunction "3_3") (pintype "passive"))
      (node (ref "SD1") (pin "3") (pinfunction "GND_3") (pintype "bidirectional"))
      (node (ref "SD1") (pin "SHIELD0") (pinfunction "GND_SHIELD0") (pintype "bidirectional"))
      (node (ref "SD1") (pin "SHIELD1") (pinfunction "GND_SHIELD1") (pintype "bidirectional"))
      (node (ref "SD1") (pin "SHIELD2") (pinfunction "GND_SHIELD2") (pintype "bidirectional"))
      (node (ref "SD1") (pin "SHIELD3") (pinfunction "GND_SHIELD3") (pintype "bidirectional"))
      (node (ref "SEG1") (pin "1") (pinfunction "COM_1") (pintype "bidirectional"))
      (node (ref "SEG1") (pin "6") (pinfunction "COM_6") (pintype "bidirectional"))
      (node (ref "SEG2") (pin "1") (pinfunction "COM_1") (pintype "bidirectional"))
      (node (ref "SEG2") (pin "6") (pinfunction "COM_6") (pintype "bidirectional"))
      (node (ref "SEG3") (pin "1") (pinfunction "COM_1") (pintype "bidirectional"))
      (node (ref "SEG3") (pin "6") (pinfunction "COM_6") (pintype "bidirectional"))
      (node (ref "SERVO_0") (pin "3") (pinfunction "3_3") (pintype "passive"))
      (node (ref "SERVO_1") (pin "3") (pinfunction "3_3") (pintype "passive"))
      (node (ref "SERVO_2") (pin "3") (pinfunction "3_3") (pintype "passive"))
      (node (ref "SERVO_3") (pin "3") (pinfunction "3_3") (pintype "passive"))
      (node (ref "SERVO_4") (pin "3") (pinfunction "3_3") (pintype "passive"))
      (node (ref "SERVO_5") (pin "3") (pinfunction "3_3") (pintype "passive"))
      (node (ref "SERVO_6") (pin "3") (pinfunction "3_3") (pintype "passive"))
      (node (ref "SERVO_7") (pin "3") (pinfunction "3_3") (pintype "passive"))
      (node (ref "SERVO_EXT_PWR") (pin "P$1") (pinfunction "1_P$1") (pintype "passive"))
      (node (ref "SW2") (pin "1") (pinfunction "1_1") (pintype "bidirectional"))
      (node (ref "U1") (pin "17") (pinfunction "VSS_17") (pintype "bidirectional"))
      (node (ref "U1") (pin "27") (pinfunction "VSS_27") (pintype "bidirectional"))
      (node (ref "U1") (pin "39") (pinfunction "VSS_39") (pintype "bidirectional"))
      (node (ref "U1") (pin "5") (pinfunction "VSS_5") (pintype "bidirectional"))
      (node (ref "U1") (pin "6") (pinfunction "BOE'_6") (pintype "bidirectional"))
      (node (ref "U10") (pin "15") (pinfunction "C_INH_15") (pintype "bidirectional"))
      (node (ref "U10") (pin "8") (pinfunction "GND_8") (pintype "bidirectional"))
      (node (ref "U11") (pin "15") (pinfunction "C_INH_15") (pintype "bidirectional"))
      (node (ref "U11") (pin "8") (pinfunction "GND_8") (pintype "bidirectional"))
      (node (ref "U12") (pin "15") (pinfunction "C_INH_15") (pintype "bidirectional"))
      (node (ref "U12") (pin "8") (pinfunction "GND_8") (pintype "bidirectional"))
      (node (ref "U13") (pin "15") (pinfunction "C_INH_15") (pintype "bidirectional"))
      (node (ref "U13") (pin "8") (pinfunction "GND_8") (pintype "bidirectional"))
      (node (ref "U14") (pin "15") (pinfunction "C_INH_15") (pintype "bidirectional"))
      (node (ref "U14") (pin "8") (pinfunction "GND_8") (pintype "bidirectional"))
      (node (ref "U15") (pin "15") (pinfunction "C_INH_15") (pintype "bidirectional"))
      (node (ref "U15") (pin "8") (pinfunction "GND_8") (pintype "bidirectional"))
      (node (ref "U16") (pin "15") (pinfunction "C_INH_15") (pintype "bidirectional"))
      (node (ref "U16") (pin "8") (pinfunction "GND_8") (pintype "bidirectional"))
      (node (ref "U17") (pin "1") (pinfunction "GND_1") (pintype "bidirectional"))
      (node (ref "U18") (pin "1") (pinfunction "GND_1") (pintype "bidirectional"))
      (node (ref "U19") (pin "1") (pinfunction "GND_1") (pintype "bidirectional"))
      (node (ref "U2") (pin "13") (pinfunction "GND_13") (pintype "bidirectional"))
      (node (ref "U2") (pin "5") (pinfunction "GND_5") (pintype "bidirectional"))
      (node (ref "U3") (pin "2") (pinfunction "GND_2") (pintype "bidirectional"))
      (node (ref "U36") (pin "1") (pinfunction "CS'_1") (pintype "bidirectional"))
      (node (ref "U36") (pin "4") (pinfunction "GND_4") (pintype "bidirectional"))
      (node (ref "U37") (pin "1") (pinfunction "CS'_1") (pintype "bidirectional"))
      (node (ref "U37") (pin "4") (pinfunction "GND_4") (pintype "bidirectional"))
      (node (ref "U38") (pin "1") (pinfunction "GND_1") (pintype "bidirectional"))
      (node (ref "U39") (pin "8") (pinfunction "GND_8") (pintype "bidirectional"))
      (node (ref "U4") (pin "2") (pinfunction "A1_2") (pintype "bidirectional"))
      (node (ref "U4") (pin "3") (pinfunction "A2_3") (pintype "bidirectional"))
      (node (ref "U4") (pin "4") (pinfunction "GND_4") (pintype "bidirectional"))
      (node (ref "U4") (pin "7") (pinfunction "WP_7") (pintype "bidirectional"))
      (node (ref "U40") (pin "8") (pinfunction "GND_8") (pintype "bidirectional"))
      (node (ref "U41") (pin "8") (pinfunction "GND_8") (pintype "bidirectional"))
      (node (ref "U42") (pin "8") (pinfunction "GND_8") (pintype "bidirectional"))
      (node (ref "U5") (pin "8") (pinfunction "GND_8") (pintype "bidirectional"))
      (node (ref "U6") (pin "8") (pinfunction "GND_8") (pintype "bidirectional"))
      (node (ref "U7") (pin "8") (pinfunction "GND_8") (pintype "bidirectional"))
      (node (ref "U75") (pin "2") (pinfunction "GND_2") (pintype "bidirectional"))
      (node (ref "U76") (pin "2") (pinfunction "GND_2") (pintype "bidirectional"))
      (node (ref "U77") (pin "2") (pinfunction "GND_2") (pintype "bidirectional"))
      (node (ref "U78") (pin "2") (pinfunction "GND_2") (pintype "bidirectional"))
      (node (ref "U79") (pin "2") (pinfunction "GND_2") (pintype "bidirectional"))
      (node (ref "U8") (pin "8") (pinfunction "GND_8") (pintype "bidirectional"))
      (node (ref "U80") (pin "2") (pinfunction "GND_2") (pintype "bidirectional"))
      (node (ref "U81") (pin "4") (pinfunction "GND_4") (pintype "bidirectional"))
      (node (ref "U82") (pin "2") (pinfunction "GND_2") (pintype "bidirectional"))
      (node (ref "U83") (pin "7") (pinfunction "GND_7") (pintype "bidirectional"))
      (node (ref "U84") (pin "2") (pinfunction "EMITTER_2") (pintype "bidirectional"))
      (node (ref "U9") (pin "15") (pinfunction "C_INH_15") (pintype "bidirectional"))
      (node (ref "U9") (pin "8") (pinfunction "GND_8") (pintype "bidirectional"))
      (node (ref "USB") (pin "5") (pinfunction "GND_5") (pintype "bidirectional"))
      (node (ref "USB") (pin "S1") (pinfunction "GND_S1") (pintype "bidirectional"))
      (node (ref "USB") (pin "S2") (pinfunction "GND_S2") (pintype "bidirectional"))
      (node (ref "USB") (pin "S3") (pinfunction "GND_S3") (pintype "bidirectional"))
      (node (ref "USB") (pin "S4") (pinfunction "GND_S4") (pintype "bidirectional"))
    )
    (net (code "118") (name "/IN0") (class "Default")
      (node (ref "R51") (pin "2") (pinfunction "2_2") (pintype "passive"))
      (node (ref "U20") (pin "15") (pinfunction "E0_15") (pintype "bidirectional"))
      (node (ref "U9") (pin "11") (pinfunction "D0_11") (pintype "bidirectional"))
    )
    (net (code "119") (name "/IN1") (class "Default")
      (node (ref "R52") (pin "2") (pinfunction "2_2") (pintype "passive"))
      (node (ref "U20") (pin "13") (pinfunction "E1_13") (pintype "bidirectional"))
      (node (ref "U9") (pin "12") (pinfunction "D1_12") (pintype "bidirectional"))
    )
    (net (code "120") (name "/IN2") (class "Default")
      (node (ref "R53") (pin "2") (pinfunction "2_2") (pintype "passive"))
      (node (ref "U20") (pin "11") (pinfunction "E2_11") (pintype "bidirectional"))
      (node (ref "U9") (pin "13") (pinfunction "D2_13") (pintype "bidirectional"))
    )
    (net (code "121") (name "/IN3") (class "Default")
      (node (ref "R54") (pin "2") (pinfunction "2_2") (pintype "passive"))
      (node (ref "U20") (pin "9") (pinfunction "E3_9") (pintype "bidirectional"))
      (node (ref "U9") (pin "14") (pinfunction "D3_14") (pintype "bidirectional"))
    )
    (net (code "122") (name "/IN4") (class "Default")
      (node (ref "R59") (pin "2") (pinfunction "2_2") (pintype "passive"))
      (node (ref "U21") (pin "15") (pinfunction "E0_15") (pintype "bidirectional"))
      (node (ref "U9") (pin "3") (pinfunction "D4_3") (pintype "bidirectional"))
    )
    (net (code "123") (name "/IN5") (class "Default")
      (node (ref "R60") (pin "2") (pinfunction "2_2") (pintype "passive"))
      (node (ref "U21") (pin "13") (pinfunction "E1_13") (pintype "bidirectional"))
      (node (ref "U9") (pin "4") (pinfunction "D5_4") (pintype "bidirectional"))
    )
    (net (code "124") (name "/IN6") (class "Default")
      (node (ref "R61") (pin "2") (pinfunction "2_2") (pintype "passive"))
      (node (ref "U21") (pin "11") (pinfunction "E2_11") (pintype "bidirectional"))
      (node (ref "U9") (pin "5") (pinfunction "D6_5") (pintype "bidirectional"))
    )
    (net (code "125") (name "/IN7") (class "Default")
      (node (ref "R62") (pin "2") (pinfunction "2_2") (pintype "passive"))
      (node (ref "U21") (pin "9") (pinfunction "E3_9") (pintype "bidirectional"))
      (node (ref "U9") (pin "6") (pinfunction "D7_6") (pintype "bidirectional"))
    )
    (net (code "126") (name "/IN8") (class "Default")
      (node (ref "R67") (pin "2") (pinfunction "2_2") (pintype "passive"))
      (node (ref "U10") (pin "11") (pinfunction "D0_11") (pintype "bidirectional"))
      (node (ref "U22") (pin "15") (pinfunction "E0_15") (pintype "bidirectional"))
    )
    (net (code "127") (name "/IN9") (class "Default")
      (node (ref "R68") (pin "2") (pinfunction "2_2") (pintype "passive"))
      (node (ref "U10") (pin "12") (pinfunction "D1_12") (pintype "bidirectional"))
      (node (ref "U22") (pin "13") (pinfunction "E1_13") (pintype "bidirectional"))
    )
    (net (code "128") (name "/IN10") (class "Default")
      (node (ref "R69") (pin "2") (pinfunction "2_2") (pintype "passive"))
      (node (ref "U10") (pin "13") (pinfunction "D2_13") (pintype "bidirectional"))
      (node (ref "U22") (pin "11") (pinfunction "E2_11") (pintype "bidirectional"))
    )
    (net (code "129") (name "/IN11") (class "Default")
      (node (ref "R70") (pin "2") (pinfunction "2_2") (pintype "passive"))
      (node (ref "U10") (pin "14") (pinfunction "D3_14") (pintype "bidirectional"))
      (node (ref "U22") (pin "9") (pinfunction "E3_9") (pintype "bidirectional"))
    )
    (net (code "130") (name "/IN12") (class "Default")
      (node (ref "R75") (pin "2") (pinfunction "2_2") (pintype "passive"))
      (node (ref "U10") (pin "3") (pinfunction "D4_3") (pintype "bidirectional"))
      (node (ref "U23") (pin "15") (pinfunction "E0_15") (pintype "bidirectional"))
    )
    (net (code "131") (name "/IN13") (class "Default")
      (node (ref "R76") (pin "2") (pinfunction "2_2") (pintype "passive"))
      (node (ref "U10") (pin "4") (pinfunction "D5_4") (pintype "bidirectional"))
      (node (ref "U23") (pin "13") (pinfunction "E1_13") (pintype "bidirectional"))
    )
    (net (code "132") (name "/IN14") (class "Default")
      (node (ref "R77") (pin "2") (pinfunction "2_2") (pintype "passive"))
      (node (ref "U10") (pin "5") (pinfunction "D6_5") (pintype "bidirectional"))
      (node (ref "U23") (pin "11") (pinfunction "E2_11") (pintype "bidirectional"))
    )
    (net (code "133") (name "/IN15") (class "Default")
      (node (ref "R78") (pin "2") (pinfunction "2_2") (pintype "passive"))
      (node (ref "U10") (pin "6") (pinfunction "D7_6") (pintype "bidirectional"))
      (node (ref "U23") (pin "9") (pinfunction "E3_9") (pintype "bidirectional"))
    )
    (net (code "134") (name "/IN16") (class "Default")
      (node (ref "R83") (pin "2") (pinfunction "2_2") (pintype "passive"))
      (node (ref "U11") (pin "11") (pinfunction "D0_11") (pintype "bidirectional"))
      (node (ref "U24") (pin "15") (pinfunction "E0_15") (pintype "bidirectional"))
    )
    (net (code "135") (name "/IN17") (class "Default")
      (node (ref "R84") (pin "2") (pinfunction "2_2") (pintype "passive"))
      (node (ref "U11") (pin "12") (pinfunction "D1_12") (pintype "bidirectional"))
      (node (ref "U24") (pin "13") (pinfunction "E1_13") (pintype "bidirectional"))
    )
    (net (code "136") (name "/IN18") (class "Default")
      (node (ref "R85") (pin "2") (pinfunction "2_2") (pintype "passive"))
      (node (ref "U11") (pin "13") (pinfunction "D2_13") (pintype "bidirectional"))
      (node (ref "U24") (pin "11") (pinfunction "E2_11") (pintype "bidirectional"))
    )
    (net (code "137") (name "/IN19") (class "Default")
      (node (ref "R86") (pin "2") (pinfunction "2_2") (pintype "passive"))
      (node (ref "U11") (pin "14") (pinfunction "D3_14") (pintype "bidirectional"))
      (node (ref "U24") (pin "9") (pinfunction "E3_9") (pintype "bidirectional"))
    )
    (net (code "138") (name "/IN20") (class "Default")
      (node (ref "R91") (pin "2") (pinfunction "2_2") (pintype "passive"))
      (node (ref "U11") (pin "3") (pinfunction "D4_3") (pintype "bidirectional"))
      (node (ref "U25") (pin "15") (pinfunction "E0_15") (pintype "bidirectional"))
    )
    (net (code "139") (name "/IN21") (class "Default")
      (node (ref "R92") (pin "2") (pinfunction "2_2") (pintype "passive"))
      (node (ref "U11") (pin "4") (pinfunction "D5_4") (pintype "bidirectional"))
      (node (ref "U25") (pin "13") (pinfunction "E1_13") (pintype "bidirectional"))
    )
    (net (code "140") (name "/IN22") (class "Default")
      (node (ref "R93") (pin "2") (pinfunction "2_2") (pintype "passive"))
      (node (ref "U11") (pin "5") (pinfunction "D6_5") (pintype "bidirectional"))
      (node (ref "U25") (pin "11") (pinfunction "E2_11") (pintype "bidirectional"))
    )
    (net (code "141") (name "/IN23") (class "Default")
      (node (ref "R94") (pin "2") (pinfunction "2_2") (pintype "passive"))
      (node (ref "U11") (pin "6") (pinfunction "D7_6") (pintype "bidirectional"))
      (node (ref "U25") (pin "9") (pinfunction "E3_9") (pintype "bidirectional"))
    )
    (net (code "142") (name "/IN24") (class "Default")
      (node (ref "R99") (pin "2") (pinfunction "2_2") (pintype "passive"))
      (node (ref "U12") (pin "11") (pinfunction "D0_11") (pintype "bidirectional"))
      (node (ref "U26") (pin "15") (pinfunction "E0_15") (pintype "bidirectional"))
    )
    (net (code "143") (name "/IN25") (class "Default")
      (node (ref "R100") (pin "2") (pinfunction "2_2") (pintype "passive"))
      (node (ref "U12") (pin "12") (pinfunction "D1_12") (pintype "bidirectional"))
      (node (ref "U26") (pin "13") (pinfunction "E1_13") (pintype "bidirectional"))
    )
    (net (code "144") (name "/IN26") (class "Default")
      (node (ref "R101") (pin "2") (pinfunction "2_2") (pintype "passive"))
      (node (ref "U12") (pin "13") (pinfunction "D2_13") (pintype "bidirectional"))
      (node (ref "U26") (pin "11") (pinfunction "E2_11") (pintype "bidirectional"))
    )
    (net (code "145") (name "/IN27") (class "Default")
      (node (ref "R102") (pin "2") (pinfunction "2_2") (pintype "passive"))
      (node (ref "U12") (pin "14") (pinfunction "D3_14") (pintype "bidirectional"))
      (node (ref "U26") (pin "9") (pinfunction "E3_9") (pintype "bidirectional"))
    )
    (net (code "146") (name "/IN28") (class "Default")
      (node (ref "R107") (pin "2") (pinfunction "2_2") (pintype "passive"))
      (node (ref "U12") (pin "3") (pinfunction "D4_3") (pintype "bidirectional"))
      (node (ref "U27") (pin "15") (pinfunction "E0_15") (pintype "bidirectional"))
    )
    (net (code "147") (name "/IN29") (class "Default")
      (node (ref "R108") (pin "2") (pinfunction "2_2") (pintype "passive"))
      (node (ref "U12") (pin "4") (pinfunction "D5_4") (pintype "bidirectional"))
      (node (ref "U27") (pin "13") (pinfunction "E1_13") (pintype "bidirectional"))
    )
    (net (code "148") (name "/IN30") (class "Default")
      (node (ref "R109") (pin "2") (pinfunction "2_2") (pintype "passive"))
      (node (ref "U12") (pin "5") (pinfunction "D6_5") (pintype "bidirectional"))
      (node (ref "U27") (pin "11") (pinfunction "E2_11") (pintype "bidirectional"))
    )
    (net (code "149") (name "/IN31") (class "Default")
      (node (ref "R110") (pin "2") (pinfunction "2_2") (pintype "passive"))
      (node (ref "U12") (pin "6") (pinfunction "D7_6") (pintype "bidirectional"))
      (node (ref "U27") (pin "9") (pinfunction "E3_9") (pintype "bidirectional"))
    )
    (net (code "150") (name "/IN32") (class "Default")
      (node (ref "R115") (pin "2") (pinfunction "2_2") (pintype "passive"))
      (node (ref "U13") (pin "11") (pinfunction "D0_11") (pintype "bidirectional"))
      (node (ref "U28") (pin "15") (pinfunction "E0_15") (pintype "bidirectional"))
    )
    (net (code "151") (name "/IN33") (class "Default")
      (node (ref "R116") (pin "2") (pinfunction "2_2") (pintype "passive"))
      (node (ref "U13") (pin "12") (pinfunction "D1_12") (pintype "bidirectional"))
      (node (ref "U28") (pin "13") (pinfunction "E1_13") (pintype "bidirectional"))
    )
    (net (code "152") (name "/IN34") (class "Default")
      (node (ref "R117") (pin "2") (pinfunction "2_2") (pintype "passive"))
      (node (ref "U13") (pin "13") (pinfunction "D2_13") (pintype "bidirectional"))
      (node (ref "U28") (pin "11") (pinfunction "E2_11") (pintype "bidirectional"))
    )
    (net (code "153") (name "/IN35") (class "Default")
      (node (ref "R118") (pin "2") (pinfunction "2_2") (pintype "passive"))
      (node (ref "U13") (pin "14") (pinfunction "D3_14") (pintype "bidirectional"))
      (node (ref "U28") (pin "9") (pinfunction "E3_9") (pintype "bidirectional"))
    )
    (net (code "154") (name "/IN36") (class "Default")
      (node (ref "R123") (pin "2") (pinfunction "2_2") (pintype "passive"))
      (node (ref "U13") (pin "3") (pinfunction "D4_3") (pintype "bidirectional"))
      (node (ref "U29") (pin "15") (pinfunction "E0_15") (pintype "bidirectional"))
    )
    (net (code "155") (name "/IN37") (class "Default")
      (node (ref "R124") (pin "2") (pinfunction "2_2") (pintype "passive"))
      (node (ref "U13") (pin "4") (pinfunction "D5_4") (pintype "bidirectional"))
      (node (ref "U29") (pin "13") (pinfunction "E1_13") (pintype "bidirectional"))
    )
    (net (code "156") (name "/IN38") (class "Default")
      (node (ref "R125") (pin "2") (pinfunction "2_2") (pintype "passive"))
      (node (ref "U13") (pin "5") (pinfunction "D6_5") (pintype "bidirectional"))
      (node (ref "U29") (pin "11") (pinfunction "E2_11") (pintype "bidirectional"))
    )
    (net (code "157") (name "/IN39") (class "Default")
      (node (ref "R126") (pin "2") (pinfunction "2_2") (pintype "passive"))
      (node (ref "U13") (pin "6") (pinfunction "D7_6") (pintype "bidirectional"))
      (node (ref "U29") (pin "9") (pinfunction "E3_9") (pintype "bidirectional"))
    )
    (net (code "158") (name "/IN40") (class "Default")
      (node (ref "R131") (pin "2") (pinfunction "2_2") (pintype "passive"))
      (node (ref "U14") (pin "11") (pinfunction "D0_11") (pintype "bidirectional"))
      (node (ref "U30") (pin "15") (pinfunction "E0_15") (pintype "bidirectional"))
    )
    (net (code "159") (name "/IN41") (class "Default")
      (node (ref "R132") (pin "2") (pinfunction "2_2") (pintype "passive"))
      (node (ref "U14") (pin "12") (pinfunction "D1_12") (pintype "bidirectional"))
      (node (ref "U30") (pin "13") (pinfunction "E1_13") (pintype "bidirectional"))
    )
    (net (code "160") (name "/IN42") (class "Default")
      (node (ref "R133") (pin "2") (pinfunction "2_2") (pintype "passive"))
      (node (ref "U14") (pin "13") (pinfunction "D2_13") (pintype "bidirectional"))
      (node (ref "U30") (pin "11") (pinfunction "E2_11") (pintype "bidirectional"))
    )
    (net (code "161") (name "/IN43") (class "Default")
      (node (ref "R134") (pin "2") (pinfunction "2_2") (pintype "passive"))
      (node (ref "U14") (pin "14") (pinfunction "D3_14") (pintype "bidirectional"))
      (node (ref "U30") (pin "9") (pinfunction "E3_9") (pintype "bidirectional"))
    )
    (net (code "162") (name "/IN44") (class "Default")
      (node (ref "R139") (pin "2") (pinfunction "2_2") (pintype "passive"))
      (node (ref "U14") (pin "3") (pinfunction "D4_3") (pintype "bidirectional"))
      (node (ref "U31") (pin "15") (pinfunction "E0_15") (pintype "bidirectional"))
    )
    (net (code "163") (name "/IN45") (class "Default")
      (node (ref "R140") (pin "2") (pinfunction "2_2") (pintype "passive"))
      (node (ref "U14") (pin "4") (pinfunction "D5_4") (pintype "bidirectional"))
      (node (ref "U31") (pin "13") (pinfunction "E1_13") (pintype "bidirectional"))
    )
    (net (code "164") (name "/IN46") (class "Default")
      (node (ref "R141") (pin "2") (pinfunction "2_2") (pintype "passive"))
      (node (ref "U14") (pin "5") (pinfunction "D6_5") (pintype "bidirectional"))
      (node (ref "U31") (pin "11") (pinfunction "E2_11") (pintype "bidirectional"))
    )
    (net (code "165") (name "/IN47") (class "Default")
      (node (ref "R142") (pin "2") (pinfunction "2_2") (pintype "passive"))
      (node (ref "U14") (pin "6") (pinfunction "D7_6") (pintype "bidirectional"))
      (node (ref "U31") (pin "9") (pinfunction "E3_9") (pintype "bidirectional"))
    )
    (net (code "166") (name "/IN48") (class "Default")
      (node (ref "R147") (pin "2") (pinfunction "2_2") (pintype "passive"))
      (node (ref "U15") (pin "11") (pinfunction "D0_11") (pintype "bidirectional"))
      (node (ref "U32") (pin "15") (pinfunction "E0_15") (pintype "bidirectional"))
    )
    (net (code "167") (name "/IN49") (class "Default")
      (node (ref "R148") (pin "2") (pinfunction "2_2") (pintype "passive"))
      (node (ref "U15") (pin "12") (pinfunction "D1_12") (pintype "bidirectional"))
      (node (ref "U32") (pin "13") (pinfunction "E1_13") (pintype "bidirectional"))
    )
    (net (code "168") (name "/IN50") (class "Default")
      (node (ref "R149") (pin "2") (pinfunction "2_2") (pintype "passive"))
      (node (ref "U15") (pin "13") (pinfunction "D2_13") (pintype "bidirectional"))
      (node (ref "U32") (pin "11") (pinfunction "E2_11") (pintype "bidirectional"))
    )
    (net (code "169") (name "/IN51") (class "Default")
      (node (ref "R150") (pin "2") (pinfunction "2_2") (pintype "passive"))
      (node (ref "U15") (pin "14") (pinfunction "D3_14") (pintype "bidirectional"))
      (node (ref "U32") (pin "9") (pinfunction "E3_9") (pintype "bidirectional"))
    )
    (net (code "170") (name "/IN52") (class "Default")
      (node (ref "R155") (pin "2") (pinfunction "2_2") (pintype "passive"))
      (node (ref "U15") (pin "3") (pinfunction "D4_3") (pintype "bidirectional"))
      (node (ref "U33") (pin "15") (pinfunction "E0_15") (pintype "bidirectional"))
    )
    (net (code "171") (name "/IN53") (class "Default")
      (node (ref "R156") (pin "2") (pinfunction "2_2") (pintype "passive"))
      (node (ref "U15") (pin "4") (pinfunction "D5_4") (pintype "bidirectional"))
      (node (ref "U33") (pin "13") (pinfunction "E1_13") (pintype "bidirectional"))
    )
    (net (code "172") (name "/IN54") (class "Default")
      (node (ref "R157") (pin "2") (pinfunction "2_2") (pintype "passive"))
      (node (ref "U15") (pin "5") (pinfunction "D6_5") (pintype "bidirectional"))
      (node (ref "U33") (pin "11") (pinfunction "E2_11") (pintype "bidirectional"))
    )
    (net (code "173") (name "/IN55") (class "Default")
      (node (ref "R158") (pin "2") (pinfunction "2_2") (pintype "passive"))
      (node (ref "U15") (pin "6") (pinfunction "D7_6") (pintype "bidirectional"))
      (node (ref "U33") (pin "9") (pinfunction "E3_9") (pintype "bidirectional"))
    )
    (net (code "174") (name "/IN56") (class "Default")
      (node (ref "R163") (pin "2") (pinfunction "2_2") (pintype "passive"))
      (node (ref "U16") (pin "11") (pinfunction "D0_11") (pintype "bidirectional"))
      (node (ref "U34") (pin "15") (pinfunction "E0_15") (pintype "bidirectional"))
    )
    (net (code "175") (name "/IN57") (class "Default")
      (node (ref "R164") (pin "2") (pinfunction "2_2") (pintype "passive"))
      (node (ref "U16") (pin "12") (pinfunction "D1_12") (pintype "bidirectional"))
      (node (ref "U34") (pin "13") (pinfunction "E1_13") (pintype "bidirectional"))
    )
    (net (code "176") (name "/IN58") (class "Default")
      (node (ref "R165") (pin "2") (pinfunction "2_2") (pintype "passive"))
      (node (ref "U16") (pin "13") (pinfunction "D2_13") (pintype "bidirectional"))
      (node (ref "U34") (pin "11") (pinfunction "E2_11") (pintype "bidirectional"))
    )
    (net (code "177") (name "/IN59") (class "Default")
      (node (ref "R166") (pin "2") (pinfunction "2_2") (pintype "passive"))
      (node (ref "U16") (pin "14") (pinfunction "D3_14") (pintype "bidirectional"))
      (node (ref "U34") (pin "9") (pinfunction "E3_9") (pintype "bidirectional"))
    )
    (net (code "178") (name "/IN60") (class "Default")
      (node (ref "R171") (pin "2") (pinfunction "2_2") (pintype "passive"))
      (node (ref "U16") (pin "3") (pinfunction "D4_3") (pintype "bidirectional"))
      (node (ref "U35") (pin "15") (pinfunction "E0_15") (pintype "bidirectional"))
    )
    (net (code "179") (name "/IN61") (class "Default")
      (node (ref "R172") (pin "2") (pinfunction "2_2") (pintype "passive"))
      (node (ref "U16") (pin "4") (pinfunction "D5_4") (pintype "bidirectional"))
      (node (ref "U35") (pin "13") (pinfunction "E1_13") (pintype "bidirectional"))
    )
    (net (code "180") (name "/IN62") (class "Default")
      (node (ref "R173") (pin "2") (pinfunction "2_2") (pintype "passive"))
      (node (ref "U16") (pin "5") (pinfunction "D6_5") (pintype "bidirectional"))
      (node (ref "U35") (pin "11") (pinfunction "E2_11") (pintype "bidirectional"))
    )
    (net (code "181") (name "/IN63") (class "Default")
      (node (ref "R174") (pin "2") (pinfunction "2_2") (pintype "passive"))
      (node (ref "U16") (pin "6") (pinfunction "D7_6") (pintype "bidirectional"))
      (node (ref "U35") (pin "9") (pinfunction "E3_9") (pintype "bidirectional"))
    )
    (net (code "182") (name "/INPUT0") (class "Default")
      (node (ref "INPUT_BANK_0") (pin "1") (pinfunction "1_1") (pintype "bidirectional"))
      (node (ref "U20") (pin "1") (pinfunction "A0_1") (pintype "bidirectional"))
    )
    (net (code "183") (name "/INPUT1") (class "Default")
      (node (ref "INPUT_BANK_0") (pin "2") (pinfunction "2_2") (pintype "bidirectional"))
      (node (ref "U20") (pin "3") (pinfunction "A1_3") (pintype "bidirectional"))
    )
    (net (code "184") (name "/INPUT2") (class "Default")
      (node (ref "INPUT_BANK_0") (pin "3") (pinfunction "3_3") (pintype "bidirectional"))
      (node (ref "U20") (pin "5") (pinfunction "A2_5") (pintype "bidirectional"))
    )
    (net (code "185") (name "/INPUT3") (class "Default")
      (node (ref "INPUT_BANK_0") (pin "4") (pinfunction "4_4") (pintype "bidirectional"))
      (node (ref "U20") (pin "7") (pinfunction "A3_7") (pintype "bidirectional"))
    )
    (net (code "186") (name "/INPUT4") (class "Default")
      (node (ref "INPUT_BANK_0") (pin "5") (pinfunction "5_5") (pintype "bidirectional"))
      (node (ref "U21") (pin "1") (pinfunction "A0_1") (pintype "bidirectional"))
    )
    (net (code "187") (name "/INPUT5") (class "Default")
      (node (ref "INPUT_BANK_0") (pin "6") (pinfunction "6_6") (pintype "bidirectional"))
      (node (ref "U21") (pin "3") (pinfunction "A1_3") (pintype "bidirectional"))
    )
    (net (code "188") (name "/INPUT6") (class "Default")
      (node (ref "INPUT_BANK_0") (pin "7") (pinfunction "7_7") (pintype "bidirectional"))
      (node (ref "U21") (pin "5") (pinfunction "A2_5") (pintype "bidirectional"))
    )
    (net (code "189") (name "/INPUT7") (class "Default")
      (node (ref "INPUT_BANK_0") (pin "8") (pinfunction "8_8") (pintype "bidirectional"))
      (node (ref "U21") (pin "7") (pinfunction "A3_7") (pintype "bidirectional"))
    )
    (net (code "190") (name "/INPUT8") (class "Default")
      (node (ref "INPUT_BANK_1") (pin "1") (pinfunction "1_1") (pintype "bidirectional"))
      (node (ref "U22") (pin "1") (pinfunction "A0_1") (pintype "bidirectional"))
    )
    (net (code "191") (name "/INPUT9") (class "Default")
      (node (ref "INPUT_BANK_1") (pin "2") (pinfunction "2_2") (pintype "bidirectional"))
      (node (ref "U22") (pin "3") (pinfunction "A1_3") (pintype "bidirectional"))
    )
    (net (code "192") (name "/INPUT10") (class "Default")
      (node (ref "INPUT_BANK_1") (pin "3") (pinfunction "3_3") (pintype "bidirectional"))
      (node (ref "U22") (pin "5") (pinfunction "A2_5") (pintype "bidirectional"))
    )
    (net (code "193") (name "/INPUT11") (class "Default")
      (node (ref "INPUT_BANK_1") (pin "4") (pinfunction "4_4") (pintype "bidirectional"))
      (node (ref "U22") (pin "7") (pinfunction "A3_7") (pintype "bidirectional"))
    )
    (net (code "194") (name "/INPUT12") (class "Default")
      (node (ref "INPUT_BANK_1") (pin "5") (pinfunction "5_5") (pintype "bidirectional"))
      (node (ref "U23") (pin "1") (pinfunction "A0_1") (pintype "bidirectional"))
    )
    (net (code "195") (name "/INPUT13") (class "Default")
      (node (ref "INPUT_BANK_1") (pin "6") (pinfunction "6_6") (pintype "bidirectional"))
      (node (ref "U23") (pin "3") (pinfunction "A1_3") (pintype "bidirectional"))
    )
    (net (code "196") (name "/INPUT14") (class "Default")
      (node (ref "INPUT_BANK_1") (pin "7") (pinfunction "7_7") (pintype "bidirectional"))
      (node (ref "U23") (pin "5") (pinfunction "A2_5") (pintype "bidirectional"))
    )
    (net (code "197") (name "/INPUT15") (class "Default")
      (node (ref "INPUT_BANK_1") (pin "8") (pinfunction "8_8") (pintype "bidirectional"))
      (node (ref "U23") (pin "7") (pinfunction "A3_7") (pintype "bidirectional"))
    )
    (net (code "198") (name "/INPUT16") (class "Default")
      (node (ref "INPUT_BANK_2") (pin "1") (pinfunction "1_1") (pintype "bidirectional"))
      (node (ref "U24") (pin "1") (pinfunction "A0_1") (pintype "bidirectional"))
    )
    (net (code "199") (name "/INPUT17") (class "Default")
      (node (ref "INPUT_BANK_2") (pin "2") (pinfunction "2_2") (pintype "bidirectional"))
      (node (ref "U24") (pin "3") (pinfunction "A1_3") (pintype "bidirectional"))
    )
    (net (code "200") (name "/INPUT18") (class "Default")
      (node (ref "INPUT_BANK_2") (pin "3") (pinfunction "3_3") (pintype "bidirectional"))
      (node (ref "U24") (pin "5") (pinfunction "A2_5") (pintype "bidirectional"))
    )
    (net (code "201") (name "/INPUT19") (class "Default")
      (node (ref "INPUT_BANK_2") (pin "4") (pinfunction "4_4") (pintype "bidirectional"))
      (node (ref "U24") (pin "7") (pinfunction "A3_7") (pintype "bidirectional"))
    )
    (net (code "202") (name "/INPUT20") (class "Default")
      (node (ref "INPUT_BANK_2") (pin "5") (pinfunction "5_5") (pintype "bidirectional"))
      (node (ref "U25") (pin "1") (pinfunction "A0_1") (pintype "bidirectional"))
    )
    (net (code "203") (name "/INPUT21") (class "Default")
      (node (ref "INPUT_BANK_2") (pin "6") (pinfunction "6_6") (pintype "bidirectional"))
      (node (ref "U25") (pin "3") (pinfunction "A1_3") (pintype "bidirectional"))
    )
    (net (code "204") (name "/INPUT22") (class "Default")
      (node (ref "INPUT_BANK_2") (pin "7") (pinfunction "7_7") (pintype "bidirectional"))
      (node (ref "U25") (pin "5") (pinfunction "A2_5") (pintype "bidirectional"))
    )
    (net (code "205") (name "/INPUT23") (class "Default")
      (node (ref "INPUT_BANK_2") (pin "8") (pinfunction "8_8") (pintype "bidirectional"))
      (node (ref "U25") (pin "7") (pinfunction "A3_7") (pintype "bidirectional"))
    )
    (net (code "206") (name "/INPUT24") (class "Default")
      (node (ref "INPUT_BANK_3") (pin "1") (pinfunction "1_1") (pintype "bidirectional"))
      (node (ref "U26") (pin "1") (pinfunction "A0_1") (pintype "bidirectional"))
    )
    (net (code "207") (name "/INPUT25") (class "Default")
      (node (ref "INPUT_BANK_3") (pin "2") (pinfunction "2_2") (pintype "bidirectional"))
      (node (ref "U26") (pin "3") (pinfunction "A1_3") (pintype "bidirectional"))
    )
    (net (code "208") (name "/INPUT26") (class "Default")
      (node (ref "INPUT_BANK_3") (pin "3") (pinfunction "3_3") (pintype "bidirectional"))
      (node (ref "U26") (pin "5") (pinfunction "A2_5") (pintype "bidirectional"))
    )
    (net (code "209") (name "/INPUT27") (class "Default")
      (node (ref "INPUT_BANK_3") (pin "4") (pinfunction "4_4") (pintype "bidirectional"))
      (node (ref "U26") (pin "7") (pinfunction "A3_7") (pintype "bidirectional"))
    )
    (net (code "210") (name "/INPUT28") (class "Default")
      (node (ref "INPUT_BANK_3") (pin "5") (pinfunction "5_5") (pintype "bidirectional"))
      (node (ref "U27") (pin "1") (pinfunction "A0_1") (pintype "bidirectional"))
    )
    (net (code "211") (name "/INPUT29") (class "Default")
      (node (ref "INPUT_BANK_3") (pin "6") (pinfunction "6_6") (pintype "bidirectional"))
      (node (ref "U27") (pin "3") (pinfunction "A1_3") (pintype "bidirectional"))
    )
    (net (code "212") (name "/INPUT30") (class "Default")
      (node (ref "INPUT_BANK_3") (pin "7") (pinfunction "7_7") (pintype "bidirectional"))
      (node (ref "U27") (pin "5") (pinfunction "A2_5") (pintype "bidirectional"))
    )
    (net (code "213") (name "/INPUT31") (class "Default")
      (node (ref "INPUT_BANK_3") (pin "8") (pinfunction "8_8") (pintype "bidirectional"))
      (node (ref "U27") (pin "7") (pinfunction "A3_7") (pintype "bidirectional"))
    )
    (net (code "214") (name "/INPUT32") (class "Default")
      (node (ref "INPUT_BANK_4") (pin "1") (pinfunction "1_1") (pintype "bidirectional"))
      (node (ref "U28") (pin "1") (pinfunction "A0_1") (pintype "bidirectional"))
    )
    (net (code "215") (name "/INPUT33") (class "Default")
      (node (ref "INPUT_BANK_4") (pin "2") (pinfunction "2_2") (pintype "bidirectional"))
      (node (ref "U28") (pin "3") (pinfunction "A1_3") (pintype "bidirectional"))
    )
    (net (code "216") (name "/INPUT34") (class "Default")
      (node (ref "INPUT_BANK_4") (pin "3") (pinfunction "3_3") (pintype "bidirectional"))
      (node (ref "U28") (pin "5") (pinfunction "A2_5") (pintype "bidirectional"))
    )
    (net (code "217") (name "/INPUT35") (class "Default")
      (node (ref "INPUT_BANK_4") (pin "4") (pinfunction "4_4") (pintype "bidirectional"))
      (node (ref "U28") (pin "7") (pinfunction "A3_7") (pintype "bidirectional"))
    )
    (net (code "218") (name "/INPUT36") (class "Default")
      (node (ref "INPUT_BANK_4") (pin "5") (pinfunction "5_5") (pintype "bidirectional"))
      (node (ref "U29") (pin "1") (pinfunction "A0_1") (pintype "bidirectional"))
    )
    (net (code "219") (name "/INPUT37") (class "Default")
      (node (ref "INPUT_BANK_4") (pin "6") (pinfunction "6_6") (pintype "bidirectional"))
      (node (ref "U29") (pin "3") (pinfunction "A1_3") (pintype "bidirectional"))
    )
    (net (code "220") (name "/INPUT38") (class "Default")
      (node (ref "INPUT_BANK_4") (pin "7") (pinfunction "7_7") (pintype "bidirectional"))
      (node (ref "U29") (pin "5") (pinfunction "A2_5") (pintype "bidirectional"))
    )
    (net (code "221") (name "/INPUT39") (class "Default")
      (node (ref "INPUT_BANK_4") (pin "8") (pinfunction "8_8") (pintype "bidirectional"))
      (node (ref "U29") (pin "7") (pinfunction "A3_7") (pintype "bidirectional"))
    )
    (net (code "222") (name "/INPUT40") (class "Default")
      (node (ref "INPUT_BANK_5") (pin "1") (pinfunction "1_1") (pintype "bidirectional"))
      (node (ref "U30") (pin "1") (pinfunction "A0_1") (pintype "bidirectional"))
    )
    (net (code "223") (name "/INPUT41") (class "Default")
      (node (ref "INPUT_BANK_5") (pin "2") (pinfunction "2_2") (pintype "bidirectional"))
      (node (ref "U30") (pin "3") (pinfunction "A1_3") (pintype "bidirectional"))
    )
    (net (code "224") (name "/INPUT42") (class "Default")
      (node (ref "INPUT_BANK_5") (pin "3") (pinfunction "3_3") (pintype "bidirectional"))
      (node (ref "U30") (pin "5") (pinfunction "A2_5") (pintype "bidirectional"))
    )
    (net (code "225") (name "/INPUT43") (class "Default")
      (node (ref "INPUT_BANK_5") (pin "4") (pinfunction "4_4") (pintype "bidirectional"))
      (node (ref "U30") (pin "7") (pinfunction "A3_7") (pintype "bidirectional"))
    )
    (net (code "226") (name "/INPUT44") (class "Default")
      (node (ref "INPUT_BANK_5") (pin "5") (pinfunction "5_5") (pintype "bidirectional"))
      (node (ref "U31") (pin "1") (pinfunction "A0_1") (pintype "bidirectional"))
    )
    (net (code "227") (name "/INPUT45") (class "Default")
      (node (ref "INPUT_BANK_5") (pin "6") (pinfunction "6_6") (pintype "bidirectional"))
      (node (ref "U31") (pin "3") (pinfunction "A1_3") (pintype "bidirectional"))
    )
    (net (code "228") (name "/INPUT46") (class "Default")
      (node (ref "INPUT_BANK_5") (pin "7") (pinfunction "7_7") (pintype "bidirectional"))
      (node (ref "U31") (pin "5") (pinfunction "A2_5") (pintype "bidirectional"))
    )
    (net (code "229") (name "/INPUT47") (class "Default")
      (node (ref "INPUT_BANK_5") (pin "8") (pinfunction "8_8") (pintype "bidirectional"))
      (node (ref "U31") (pin "7") (pinfunction "A3_7") (pintype "bidirectional"))
    )
    (net (code "230") (name "/INPUT48") (class "Default")
      (node (ref "INPUT_BANK_6") (pin "1") (pinfunction "1_1") (pintype "bidirectional"))
      (node (ref "U32") (pin "1") (pinfunction "A0_1") (pintype "bidirectional"))
    )
    (net (code "231") (name "/INPUT49") (class "Default")
      (node (ref "INPUT_BANK_6") (pin "2") (pinfunction "2_2") (pintype "bidirectional"))
      (node (ref "U32") (pin "3") (pinfunction "A1_3") (pintype "bidirectional"))
    )
    (net (code "232") (name "/INPUT50") (class "Default")
      (node (ref "INPUT_BANK_6") (pin "3") (pinfunction "3_3") (pintype "bidirectional"))
      (node (ref "U32") (pin "5") (pinfunction "A2_5") (pintype "bidirectional"))
    )
    (net (code "233") (name "/INPUT51") (class "Default")
      (node (ref "INPUT_BANK_6") (pin "4") (pinfunction "4_4") (pintype "bidirectional"))
      (node (ref "U32") (pin "7") (pinfunction "A3_7") (pintype "bidirectional"))
    )
    (net (code "234") (name "/INPUT52") (class "Default")
      (node (ref "INPUT_BANK_6") (pin "5") (pinfunction "5_5") (pintype "bidirectional"))
      (node (ref "U33") (pin "1") (pinfunction "A0_1") (pintype "bidirectional"))
    )
    (net (code "235") (name "/INPUT53") (class "Default")
      (node (ref "INPUT_BANK_6") (pin "6") (pinfunction "6_6") (pintype "bidirectional"))
      (node (ref "U33") (pin "3") (pinfunction "A1_3") (pintype "bidirectional"))
    )
    (net (code "236") (name "/INPUT54") (class "Default")
      (node (ref "INPUT_BANK_6") (pin "7") (pinfunction "7_7") (pintype "bidirectional"))
      (node (ref "U33") (pin "5") (pinfunction "A2_5") (pintype "bidirectional"))
    )
    (net (code "237") (name "/INPUT55") (class "Default")
      (node (ref "INPUT_BANK_6") (pin "8") (pinfunction "8_8") (pintype "bidirectional"))
      (node (ref "U33") (pin "7") (pinfunction "A3_7") (pintype "bidirectional"))
    )
    (net (code "238") (name "/INPUT56") (class "Default")
      (node (ref "INPUT_BANK_7") (pin "1") (pinfunction "1_1") (pintype "bidirectional"))
      (node (ref "U34") (pin "1") (pinfunction "A0_1") (pintype "bidirectional"))
    )
    (net (code "239") (name "/INPUT57") (class "Default")
      (node (ref "INPUT_BANK_7") (pin "2") (pinfunction "2_2") (pintype "bidirectional"))
      (node (ref "U34") (pin "3") (pinfunction "A1_3") (pintype "bidirectional"))
    )
    (net (code "240") (name "/INPUT58") (class "Default")
      (node (ref "INPUT_BANK_7") (pin "3") (pinfunction "3_3") (pintype "bidirectional"))
      (node (ref "U34") (pin "5") (pinfunction "A2_5") (pintype "bidirectional"))
    )
    (net (code "241") (name "/INPUT59") (class "Default")
      (node (ref "INPUT_BANK_7") (pin "4") (pinfunction "4_4") (pintype "bidirectional"))
      (node (ref "U34") (pin "7") (pinfunction "A3_7") (pintype "bidirectional"))
    )
    (net (code "242") (name "/INPUT60") (class "Default")
      (node (ref "INPUT_BANK_7") (pin "5") (pinfunction "5_5") (pintype "bidirectional"))
      (node (ref "U35") (pin "1") (pinfunction "A0_1") (pintype "bidirectional"))
    )
    (net (code "243") (name "/INPUT61") (class "Default")
      (node (ref "INPUT_BANK_7") (pin "6") (pinfunction "6_6") (pintype "bidirectional"))
      (node (ref "U35") (pin "3") (pinfunction "A1_3") (pintype "bidirectional"))
    )
    (net (code "244") (name "/INPUT62") (class "Default")
      (node (ref "INPUT_BANK_7") (pin "7") (pinfunction "7_7") (pintype "bidirectional"))
      (node (ref "U35") (pin "5") (pinfunction "A2_5") (pintype "bidirectional"))
    )
    (net (code "245") (name "/INPUT63") (class "Default")
      (node (ref "INPUT_BANK_7") (pin "8") (pinfunction "8_8") (pintype "bidirectional"))
      (node (ref "U35") (pin "7") (pinfunction "A3_7") (pintype "bidirectional"))
    )
    (net (code "246") (name "/IREF0") (class "Default")
      (node (ref "R12") (pin "1") (pinfunction "1_1") (pintype "passive"))
      (node (ref "U17") (pin "3") (pinfunction "IREF_3") (pintype "bidirectional"))
    )
    (net (code "247") (name "/IREF1") (class "Default")
      (node (ref "R13") (pin "1") (pinfunction "1_1") (pintype "passive"))
      (node (ref "U18") (pin "3") (pinfunction "IREF_3") (pintype "bidirectional"))
    )
    (net (code "248") (name "/IREF2") (class "Default")
      (node (ref "R14") (pin "1") (pinfunction "1_1") (pintype "passive"))
      (node (ref "U19") (pin "3") (pinfunction "IREF_3") (pintype "bidirectional"))
    )
    (net (code "249") (name "/IREF3") (class "Default")
      (node (ref "R175") (pin "1") (pinfunction "1_1") (pintype "passive"))
      (node (ref "U38") (pin "3") (pinfunction "IREF_3") (pintype "bidirectional"))
    )
    (net (code "250") (name "/IRQ") (class "Default")
      (node (ref "R6") (pin "1") (pinfunction "1_1") (pintype "passive"))
      (node (ref "SD1") (pin "1") (pinfunction "IRQ_1") (pintype "bidirectional"))
    )
    (net (code "251") (name "/LED0") (class "Default")
      (node (ref "LIGHT_BANK_0") (pin "1") (pinfunction "1_1") (pintype "bidirectional"))
      (node (ref "U17") (pin "6") (pinfunction "OUT0_6") (pintype "bidirectional"))
    )
    (net (code "252") (name "/LED1") (class "Default")
      (node (ref "LIGHT_BANK_0") (pin "2") (pinfunction "2_2") (pintype "bidirectional"))
      (node (ref "U17") (pin "7") (pinfunction "OUT1_7") (pintype "bidirectional"))
    )
    (net (code "253") (name "/LED2") (class "Default")
      (node (ref "LIGHT_BANK_0") (pin "3") (pinfunction "3_3") (pintype "bidirectional"))
      (node (ref "U17") (pin "8") (pinfunction "OUT2_8") (pintype "bidirectional"))
    )
    (net (code "254") (name "/LED3") (class "Default")
      (node (ref "LIGHT_BANK_0") (pin "4") (pinfunction "4_4") (pintype "bidirectional"))
      (node (ref "U17") (pin "9") (pinfunction "OUT3_9") (pintype "bidirectional"))
    )
    (net (code "255") (name "/LED4") (class "Default")
      (node (ref "LIGHT_BANK_0") (pin "5") (pinfunction "5_5") (pintype "bidirectional"))
      (node (ref "U17") (pin "10") (pinfunction "OUT4_10") (pintype "bidirectional"))
    )
    (net (code "256") (name "/LED5") (class "Default")
      (node (ref "LIGHT_BANK_0") (pin "6") (pinfunction "6_6") (pintype "bidirectional"))
      (node (ref "U17") (pin "11") (pinfunction "OUT5_11") (pintype "bidirectional"))
    )
    (net (code "257") (name "/LED6") (class "Default")
      (node (ref "LIGHT_BANK_0") (pin "7") (pinfunction "7_7") (pintype "bidirectional"))
      (node (ref "U17") (pin "12") (pinfunction "OUT6_12") (pintype "bidirectional"))
    )
    (net (code "258") (name "/LED7") (class "Default")
      (node (ref "LIGHT_BANK_0") (pin "8") (pinfunction "8_8") (pintype "bidirectional"))
      (node (ref "U17") (pin "13") (pinfunction "OUT7_13") (pintype "bidirectional"))
    )
    (net (code "259") (name "/LED8") (class "Default")
      (node (ref "LIGHT_BANK_0") (pin "9") (pinfunction "9_9") (pintype "bidirectional"))
      (node (ref "U17") (pin "14") (pinfunction "OUT8_14") (pintype "bidirectional"))
    )
    (net (code "260") (name "/LED9") (class "Default")
      (node (ref "LIGHT_BANK_1") (pin "9") (pinfunction "9_9") (pintype "bidirectional"))
      (node (ref "U17") (pin "15") (pinfunction "OUT9_15") (pintype "bidirectional"))
    )
    (net (code "261") (name "/LED10") (class "Default")
      (node (ref "LIGHT_BANK_1") (pin "8") (pinfunction "8_8") (pintype "bidirectional"))
      (node (ref "U17") (pin "16") (pinfunction "OUT10_16") (pintype "bidirectional"))
    )
    (net (code "262") (name "/LED11") (class "Default")
      (node (ref "LIGHT_BANK_1") (pin "7") (pinfunction "7_7") (pintype "bidirectional"))
      (node (ref "U17") (pin "17") (pinfunction "OUT11_17") (pintype "bidirectional"))
    )
    (net (code "263") (name "/LED12") (class "Default")
      (node (ref "LIGHT_BANK_1") (pin "6") (pinfunction "6_6") (pintype "bidirectional"))
      (node (ref "U17") (pin "18") (pinfunction "OUT12_18") (pintype "bidirectional"))
    )
    (net (code "264") (name "/LED13") (class "Default")
      (node (ref "LIGHT_BANK_1") (pin "5") (pinfunction "5_5") (pintype "bidirectional"))
      (node (ref "U17") (pin "19") (pinfunction "OUT13_19") (pintype "bidirectional"))
    )
    (net (code "265") (name "/LED14") (class "Default")
      (node (ref "LIGHT_BANK_1") (pin "4") (pinfunction "4_4") (pintype "bidirectional"))
      (node (ref "U17") (pin "20") (pinfunction "OUT14_20") (pintype "bidirectional"))
    )
    (net (code "266") (name "/LED15") (class "Default")
      (node (ref "LIGHT_BANK_1") (pin "3") (pinfunction "3_3") (pintype "bidirectional"))
      (node (ref "U17") (pin "21") (pinfunction "OUT15_21") (pintype "bidirectional"))
    )
    (net (code "267") (name "/LED16") (class "Default")
      (node (ref "LIGHT_BANK_1") (pin "2") (pinfunction "2_2") (pintype "bidirectional"))
      (node (ref "U17") (pin "22") (pinfunction "OUT16_22") (pintype "bidirectional"))
    )
    (net (code "268") (name "/LED17") (class "Default")
      (node (ref "LIGHT_BANK_1") (pin "1") (pinfunction "1_1") (pintype "bidirectional"))
      (node (ref "U17") (pin "23") (pinfunction "OUT17_23") (pintype "bidirectional"))
    )
    (net (code "269") (name "/LED18") (class "Default")
      (node (ref "LIGHT_BANK_2") (pin "1") (pinfunction "1_1") (pintype "bidirectional"))
      (node (ref "U18") (pin "6") (pinfunction "OUT0_6") (pintype "bidirectional"))
    )
    (net (code "270") (name "/LED19") (class "Default")
      (node (ref "LIGHT_BANK_2") (pin "2") (pinfunction "2_2") (pintype "bidirectional"))
      (node (ref "U18") (pin "7") (pinfunction "OUT1_7") (pintype "bidirectional"))
    )
    (net (code "271") (name "/LED20") (class "Default")
      (node (ref "LIGHT_BANK_2") (pin "3") (pinfunction "3_3") (pintype "bidirectional"))
      (node (ref "U18") (pin "8") (pinfunction "OUT2_8") (pintype "bidirectional"))
    )
    (net (code "272") (name "/LED21") (class "Default")
      (node (ref "LIGHT_BANK_2") (pin "4") (pinfunction "4_4") (pintype "bidirectional"))
      (node (ref "U18") (pin "9") (pinfunction "OUT3_9") (pintype "bidirectional"))
    )
    (net (code "273") (name "/LED22") (class "Default")
      (node (ref "LIGHT_BANK_2") (pin "5") (pinfunction "5_5") (pintype "bidirectional"))
      (node (ref "U18") (pin "10") (pinfunction "OUT4_10") (pintype "bidirectional"))
    )
    (net (code "274") (name "/LED23") (class "Default")
      (node (ref "LIGHT_BANK_2") (pin "6") (pinfunction "6_6") (pintype "bidirectional"))
      (node (ref "U18") (pin "11") (pinfunction "OUT5_11") (pintype "bidirectional"))
    )
    (net (code "275") (name "/LED24") (class "Default")
      (node (ref "LIGHT_BANK_2") (pin "7") (pinfunction "7_7") (pintype "bidirectional"))
      (node (ref "U18") (pin "12") (pinfunction "OUT6_12") (pintype "bidirectional"))
    )
    (net (code "276") (name "/LED25") (class "Default")
      (node (ref "LIGHT_BANK_2") (pin "8") (pinfunction "8_8") (pintype "bidirectional"))
      (node (ref "U18") (pin "13") (pinfunction "OUT7_13") (pintype "bidirectional"))
    )
    (net (code "277") (name "/LED26") (class "Default")
      (node (ref "LIGHT_BANK_2") (pin "9") (pinfunction "9_9") (pintype "bidirectional"))
      (node (ref "U18") (pin "14") (pinfunction "OUT8_14") (pintype "bidirectional"))
    )
    (net (code "278") (name "/LED27") (class "Default")
      (node (ref "LIGHT_BANK_3") (pin "9") (pinfunction "9_9") (pintype "bidirectional"))
      (node (ref "U18") (pin "15") (pinfunction "OUT9_15") (pintype "bidirectional"))
    )
    (net (code "279") (name "/LED28") (class "Default")
      (node (ref "LIGHT_BANK_3") (pin "8") (pinfunction "8_8") (pintype "bidirectional"))
      (node (ref "U18") (pin "16") (pinfunction "OUT10_16") (pintype "bidirectional"))
    )
    (net (code "280") (name "/LED29") (class "Default")
      (node (ref "LIGHT_BANK_3") (pin "7") (pinfunction "7_7") (pintype "bidirectional"))
      (node (ref "U18") (pin "17") (pinfunction "OUT11_17") (pintype "bidirectional"))
    )
    (net (code "281") (name "/LED30") (class "Default")
      (node (ref "LIGHT_BANK_3") (pin "6") (pinfunction "6_6") (pintype "bidirectional"))
      (node (ref "U18") (pin "18") (pinfunction "OUT12_18") (pintype "bidirectional"))
    )
    (net (code "282") (name "/LED31") (class "Default")
      (node (ref "LIGHT_BANK_3") (pin "5") (pinfunction "5_5") (pintype "bidirectional"))
      (node (ref "U18") (pin "19") (pinfunction "OUT13_19") (pintype "bidirectional"))
    )
    (net (code "283") (name "/LED32") (class "Default")
      (node (ref "LIGHT_BANK_3") (pin "4") (pinfunction "4_4") (pintype "bidirectional"))
      (node (ref "U18") (pin "20") (pinfunction "OUT14_20") (pintype "bidirectional"))
    )
    (net (code "284") (name "/LED33") (class "Default")
      (node (ref "LIGHT_BANK_3") (pin "3") (pinfunction "3_3") (pintype "bidirectional"))
      (node (ref "U18") (pin "21") (pinfunction "OUT15_21") (pintype "bidirectional"))
    )
    (net (code "285") (name "/LED34") (class "Default")
      (node (ref "LIGHT_BANK_3") (pin "2") (pinfunction "2_2") (pintype "bidirectional"))
      (node (ref "U18") (pin "22") (pinfunction "OUT16_22") (pintype "bidirectional"))
    )
    (net (code "286") (name "/LED35") (class "Default")
      (node (ref "LIGHT_BANK_3") (pin "1") (pinfunction "1_1") (pintype "bidirectional"))
      (node (ref "U18") (pin "23") (pinfunction "OUT17_23") (pintype "bidirectional"))
    )
    (net (code "287") (name "/LED36") (class "Default")
      (node (ref "LIGHT_BANK_4") (pin "1") (pinfunction "1_1") (pintype "bidirectional"))
      (node (ref "U19") (pin "6") (pinfunction "OUT0_6") (pintype "bidirectional"))
    )
    (net (code "288") (name "/LED37") (class "Default")
      (node (ref "LIGHT_BANK_4") (pin "2") (pinfunction "2_2") (pintype "bidirectional"))
      (node (ref "U19") (pin "7") (pinfunction "OUT1_7") (pintype "bidirectional"))
    )
    (net (code "289") (name "/LED38") (class "Default")
      (node (ref "LIGHT_BANK_4") (pin "3") (pinfunction "3_3") (pintype "bidirectional"))
      (node (ref "U19") (pin "8") (pinfunction "OUT2_8") (pintype "bidirectional"))
    )
    (net (code "290") (name "/LED39") (class "Default")
      (node (ref "LIGHT_BANK_4") (pin "4") (pinfunction "4_4") (pintype "bidirectional"))
      (node (ref "U19") (pin "9") (pinfunction "OUT3_9") (pintype "bidirectional"))
    )
    (net (code "291") (name "/LED40") (class "Default")
      (node (ref "LIGHT_BANK_4") (pin "5") (pinfunction "5_5") (pintype "bidirectional"))
      (node (ref "U19") (pin "10") (pinfunction "OUT4_10") (pintype "bidirectional"))
    )
    (net (code "292") (name "/LED41") (class "Default")
      (node (ref "LIGHT_BANK_4") (pin "6") (pinfunction "6_6") (pintype "bidirectional"))
      (node (ref "U19") (pin "11") (pinfunction "OUT5_11") (pintype "bidirectional"))
    )
    (net (code "293") (name "/LED42") (class "Default")
      (node (ref "LIGHT_BANK_4") (pin "7") (pinfunction "7_7") (pintype "bidirectional"))
      (node (ref "U19") (pin "12") (pinfunction "OUT6_12") (pintype "bidirectional"))
    )
    (net (code "294") (name "/LED43") (class "Default")
      (node (ref "LIGHT_BANK_4") (pin "8") (pinfunction "8_8") (pintype "bidirectional"))
      (node (ref "U19") (pin "13") (pinfunction "OUT7_13") (pintype "bidirectional"))
    )
    (net (code "295") (name "/LED44") (class "Default")
      (node (ref "LIGHT_BANK_4") (pin "9") (pinfunction "9_9") (pintype "bidirectional"))
      (node (ref "U19") (pin "14") (pinfunction "OUT8_14") (pintype "bidirectional"))
    )
    (net (code "296") (name "/LED45") (class "Default")
      (node (ref "LIGHT_BANK_5") (pin "9") (pinfunction "9_9") (pintype "bidirectional"))
      (node (ref "U19") (pin "15") (pinfunction "OUT9_15") (pintype "bidirectional"))
    )
    (net (code "297") (name "/LED46") (class "Default")
      (node (ref "LIGHT_BANK_5") (pin "8") (pinfunction "8_8") (pintype "bidirectional"))
      (node (ref "U19") (pin "16") (pinfunction "OUT10_16") (pintype "bidirectional"))
    )
    (net (code "298") (name "/LED47") (class "Default")
      (node (ref "LIGHT_BANK_5") (pin "7") (pinfunction "7_7") (pintype "bidirectional"))
      (node (ref "U19") (pin "17") (pinfunction "OUT11_17") (pintype "bidirectional"))
    )
    (net (code "299") (name "/LED48") (class "Default")
      (node (ref "LIGHT_BANK_5") (pin "6") (pinfunction "6_6") (pintype "bidirectional"))
      (node (ref "U19") (pin "18") (pinfunction "OUT12_18") (pintype "bidirectional"))
    )
    (net (code "300") (name "/LED49") (class "Default")
      (node (ref "LIGHT_BANK_5") (pin "5") (pinfunction "5_5") (pintype "bidirectional"))
      (node (ref "U19") (pin "19") (pinfunction "OUT13_19") (pintype "bidirectional"))
    )
    (net (code "301") (name "/LED50") (class "Default")
      (node (ref "LIGHT_BANK_5") (pin "4") (pinfunction "4_4") (pintype "bidirectional"))
      (node (ref "U19") (pin "20") (pinfunction "OUT14_20") (pintype "bidirectional"))
    )
    (net (code "302") (name "/LED51") (class "Default")
      (node (ref "LIGHT_BANK_5") (pin "3") (pinfunction "3_3") (pintype "bidirectional"))
      (node (ref "U19") (pin "21") (pinfunction "OUT15_21") (pintype "bidirectional"))
    )
    (net (code "303") (name "/LED52") (class "Default")
      (node (ref "LIGHT_BANK_5") (pin "2") (pinfunction "2_2") (pintype "bidirectional"))
      (node (ref "U19") (pin "22") (pinfunction "OUT16_22") (pintype "bidirectional"))
    )
    (net (code "304") (name "/LED53") (class "Default")
      (node (ref "LIGHT_BANK_5") (pin "1") (pinfunction "1_1") (pintype "bidirectional"))
      (node (ref "U19") (pin "23") (pinfunction "OUT17_23") (pintype "bidirectional"))
    )
    (net (code "305") (name "/LED54") (class "Default")
      (node (ref "LIGHT_BANK_6") (pin "1") (pinfunction "1_1") (pintype "bidirectional"))
      (node (ref "U38") (pin "6") (pinfunction "OUT0_6") (pintype "bidirectional"))
    )
    (net (code "306") (name "/LED55") (class "Default")
      (node (ref "LIGHT_BANK_6") (pin "2") (pinfunction "2_2") (pintype "bidirectional"))
      (node (ref "U38") (pin "7") (pinfunction "OUT1_7") (pintype "bidirectional"))
    )
    (net (code "307") (name "/LED56") (class "Default")
      (node (ref "LIGHT_BANK_6") (pin "3") (pinfunction "3_3") (pintype "bidirectional"))
      (node (ref "U38") (pin "8") (pinfunction "OUT2_8") (pintype "bidirectional"))
    )
    (net (code "308") (name "/LED57") (class "Default")
      (node (ref "LIGHT_BANK_6") (pin "4") (pinfunction "4_4") (pintype "bidirectional"))
      (node (ref "U38") (pin "9") (pinfunction "OUT3_9") (pintype "bidirectional"))
    )
    (net (code "309") (name "/LED58") (class "Default")
      (node (ref "LIGHT_BANK_6") (pin "5") (pinfunction "5_5") (pintype "bidirectional"))
      (node (ref "U38") (pin "10") (pinfunction "OUT4_10") (pintype "bidirectional"))
    )
    (net (code "310") (name "/LED59") (class "Default")
      (node (ref "LIGHT_BANK_6") (pin "6") (pinfunction "6_6") (pintype "bidirectional"))
      (node (ref "U38") (pin "11") (pinfunction "OUT5_11") (pintype "bidirectional"))
    )
    (net (code "311") (name "/LED60") (class "Default")
      (node (ref "LIGHT_BANK_6") (pin "7") (pinfunction "7_7") (pintype "bidirectional"))
      (node (ref "U38") (pin "12") (pinfunction "OUT6_12") (pintype "bidirectional"))
    )
    (net (code "312") (name "/LED61") (class "Default")
      (node (ref "LIGHT_BANK_6") (pin "8") (pinfunction "8_8") (pintype "bidirectional"))
      (node (ref "U38") (pin "13") (pinfunction "OUT7_13") (pintype "bidirectional"))
    )
    (net (code "313") (name "/LED62") (class "Default")
      (node (ref "LIGHT_BANK_6") (pin "9") (pinfunction "9_9") (pintype "bidirectional"))
      (node (ref "U38") (pin "14") (pinfunction "OUT8_14") (pintype "bidirectional"))
    )
    (net (code "314") (name "/LED63") (class "Default")
      (node (ref "LIGHT_BANK_7") (pin "9") (pinfunction "9_9") (pintype "bidirectional"))
      (node (ref "U38") (pin "15") (pinfunction "OUT9_15") (pintype "bidirectional"))
    )
    (net (code "315") (name "/LED64") (class "Default")
      (node (ref "LIGHT_BANK_7") (pin "8") (pinfunction "8_8") (pintype "bidirectional"))
      (node (ref "U38") (pin "16") (pinfunction "OUT10_16") (pintype "bidirectional"))
    )
    (net (code "316") (name "/LED65") (class "Default")
      (node (ref "LIGHT_BANK_7") (pin "7") (pinfunction "7_7") (pintype "bidirectional"))
      (node (ref "U38") (pin "17") (pinfunction "OUT11_17") (pintype "bidirectional"))
    )
    (net (code "317") (name "/LED66") (class "Default")
      (node (ref "LIGHT_BANK_7") (pin "6") (pinfunction "6_6") (pintype "bidirectional"))
      (node (ref "U38") (pin "18") (pinfunction "OUT12_18") (pintype "bidirectional"))
    )
    (net (code "318") (name "/LED67") (class "Default")
      (node (ref "LIGHT_BANK_7") (pin "5") (pinfunction "5_5") (pintype "bidirectional"))
      (node (ref "U38") (pin "19") (pinfunction "OUT13_19") (pintype "bidirectional"))
    )
    (net (code "319") (name "/LED68") (class "Default")
      (node (ref "LIGHT_BANK_7") (pin "4") (pinfunction "4_4") (pintype "bidirectional"))
      (node (ref "U38") (pin "20") (pinfunction "OUT14_20") (pintype "bidirectional"))
    )
    (net (code "320") (name "/LED69") (class "Default")
      (node (ref "LIGHT_BANK_7") (pin "3") (pinfunction "3_3") (pintype "bidirectional"))
      (node (ref "U38") (pin "21") (pinfunction "OUT15_21") (pintype "bidirectional"))
    )
    (net (code "321") (name "/LED70") (class "Default")
      (node (ref "LIGHT_BANK_7") (pin "2") (pinfunction "2_2") (pintype "bidirectional"))
      (node (ref "U38") (pin "22") (pinfunction "OUT16_22") (pintype "bidirectional"))
    )
    (net (code "322") (name "/LED71") (class "Default")
      (node (ref "LIGHT_BANK_7") (pin "1") (pinfunction "1_1") (pintype "bidirectional"))
      (node (ref "U38") (pin "23") (pinfunction "OUT17_23") (pintype "bidirectional"))
    )
    (net (code "323") (name "/LED_CK0") (class "Default")
      (node (ref "U1") (pin "32") (pinfunction "P25_32") (pintype "bidirectional"))
      (node (ref "U17") (pin "4") (pinfunction "CKI_4") (pintype "bidirectional"))
    )
    (net (code "324") (name "/LED_CK1") (class "Default")
      (node (ref "U17") (pin "25") (pinfunction "CKO_25") (pintype "bidirectional"))
      (node (ref "U18") (pin "4") (pinfunction "CKI_4") (pintype "bidirectional"))
    )
    (net (code "325") (name "/LED_CK2") (class "Default")
      (node (ref "U18") (pin "25") (pinfunction "CKO_25") (pintype "bidirectional"))
      (node (ref "U19") (pin "4") (pinfunction "CKI_4") (pintype "bidirectional"))
    )
    (net (code "326") (name "/LED_CK3") (class "Default")
      (node (ref "U19") (pin "25") (pinfunction "CKO_25") (pintype "bidirectional"))
      (node (ref "U38") (pin "4") (pinfunction "CKI_4") (pintype "bidirectional"))
    )
    (net (code "327") (name "/LED_CK4") (class "Default")
      (node (ref "U38") (pin "25") (pinfunction "CKO_25") (pintype "bidirectional"))
      (node (ref "U82") (pin "3") (pinfunction "I/O2A_3") (pintype "bidirectional"))
    )
    (net (code "328") (name "/LED_CK4_OUT") (class "Default")
      (node (ref "RGB_CONN") (pin "1") (pinfunction "1_1") (pintype "passive"))
      (node (ref "U82") (pin "1") (pinfunction "I/O1A_1") (pintype "bidirectional"))
    )
    (net (code "329") (name "/LED_SD0") (class "Default")
      (node (ref "U1") (pin "31") (pinfunction "P24_31") (pintype "bidirectional"))
      (node (ref "U17") (pin "5") (pinfunction "SDI_5") (pintype "bidirectional"))
    )
    (net (code "330") (name "/LED_SD1") (class "Default")
      (node (ref "U17") (pin "24") (pinfunction "SDO_24") (pintype "bidirectional"))
      (node (ref "U18") (pin "5") (pinfunction "SDI_5") (pintype "bidirectional"))
    )
    (net (code "331") (name "/LED_SD2") (class "Default")
      (node (ref "U18") (pin "24") (pinfunction "SDO_24") (pintype "bidirectional"))
      (node (ref "U19") (pin "5") (pinfunction "SDI_5") (pintype "bidirectional"))
    )
    (net (code "332") (name "/LED_SD3") (class "Default")
      (node (ref "U19") (pin "24") (pinfunction "SDO_24") (pintype "bidirectional"))
      (node (ref "U38") (pin "5") (pinfunction "SDI_5") (pintype "bidirectional"))
    )
    (net (code "333") (name "/LED_SD4") (class "Default")
      (node (ref "U38") (pin "24") (pinfunction "SDO_24") (pintype "bidirectional"))
      (node (ref "U82") (pin "4") (pinfunction "I/O2B_4") (pintype "bidirectional"))
    )
    (net (code "334") (name "/LED_SD4_OUT") (class "Default")
      (node (ref "RGB_CONN") (pin "2") (pinfunction "2_2") (pintype "passive"))
      (node (ref "U82") (pin "6") (pinfunction "I/O1B_6") (pintype "bidirectional"))
    )
    (net (code "335") (name "/OUT0") (class "Default")
      (node (ref "R16") (pin "2") (pinfunction "2_2") (pintype "passive"))
      (node (ref "S0") (pin "G") (pinfunction "GATE_G") (pintype "bidirectional"))
      (node (ref "U5") (pin "15") (pinfunction "Q0_15") (pintype "bidirectional"))
    )
    (net (code "336") (name "/OUT1") (class "Default")
      (node (ref "R15") (pin "2") (pinfunction "2_2") (pintype "passive"))
      (node (ref "S1") (pin "G") (pinfunction "GATE_G") (pintype "bidirectional"))
      (node (ref "U5") (pin "1") (pinfunction "Q1_1") (pintype "bidirectional"))
    )
    (net (code "337") (name "/OUT2") (class "Default")
      (node (ref "R18") (pin "2") (pinfunction "2_2") (pintype "passive"))
      (node (ref "S2") (pin "G") (pinfunction "GATE_G") (pintype "bidirectional"))
      (node (ref "U5") (pin "2") (pinfunction "Q2_2") (pintype "bidirectional"))
    )
    (net (code "338") (name "/OUT3") (class "Default")
      (node (ref "R17") (pin "2") (pinfunction "2_2") (pintype "passive"))
      (node (ref "S3") (pin "G") (pinfunction "GATE_G") (pintype "bidirectional"))
      (node (ref "U5") (pin "3") (pinfunction "Q3_3") (pintype "bidirectional"))
    )
    (net (code "339") (name "/OUT4") (class "Default")
      (node (ref "R20") (pin "2") (pinfunction "2_2") (pintype "passive"))
      (node (ref "S4") (pin "G") (pinfunction "GATE_G") (pintype "bidirectional"))
      (node (ref "U5") (pin "4") (pinfunction "Q4_4") (pintype "bidirectional"))
    )
    (net (code "340") (name "/OUT5") (class "Default")
      (node (ref "R19") (pin "2") (pinfunction "2_2") (pintype "passive"))
      (node (ref "S5") (pin "G") (pinfunction "GATE_G") (pintype "bidirectional"))
      (node (ref "U5") (pin "5") (pinfunction "Q5_5") (pintype "bidirectional"))
    )
    (net (code "341") (name "/OUT6") (class "Default")
      (node (ref "R22") (pin "2") (pinfunction "2_2") (pintype "passive"))
      (node (ref "S6") (pin "G") (pinfunction "GATE_G") (pintype "bidirectional"))
      (node (ref "U5") (pin "6") (pinfunction "Q6_6") (pintype "bidirectional"))
    )
    (net (code "342") (name "/OUT7") (class "Default")
      (node (ref "R21") (pin "2") (pinfunction "2_2") (pintype "passive"))
      (node (ref "S7") (pin "G") (pinfunction "GATE_G") (pintype "bidirectional"))
      (node (ref "U5") (pin "7") (pinfunction "Q7_7") (pintype "bidirectional"))
    )
    (net (code "343") (name "/OUT8") (class "Default")
      (node (ref "R24") (pin "2") (pinfunction "2_2") (pintype "passive"))
      (node (ref "S8") (pin "G") (pinfunction "GATE_G") (pintype "bidirectional"))
      (node (ref "U6") (pin "15") (pinfunction "Q0_15") (pintype "bidirectional"))
    )
    (net (code "344") (name "/OUT9") (class "Default")
      (node (ref "R23") (pin "2") (pinfunction "2_2") (pintype "passive"))
      (node (ref "S9") (pin "G") (pinfunction "GATE_G") (pintype "bidirectional"))
      (node (ref "U6") (pin "1") (pinfunction "Q1_1") (pintype "bidirectional"))
    )
    (net (code "345") (name "/OUT10") (class "Default")
      (node (ref "R26") (pin "2") (pinfunction "2_2") (pintype "passive"))
      (node (ref "S10") (pin "G") (pinfunction "GATE_G") (pintype "bidirectional"))
      (node (ref "U6") (pin "2") (pinfunction "Q2_2") (pintype "bidirectional"))
    )
    (net (code "346") (name "/OUT11") (class "Default")
      (node (ref "R25") (pin "2") (pinfunction "2_2") (pintype "passive"))
      (node (ref "S11") (pin "G") (pinfunction "GATE_G") (pintype "bidirectional"))
      (node (ref "U6") (pin "3") (pinfunction "Q3_3") (pintype "bidirectional"))
    )
    (net (code "347") (name "/OUT12") (class "Default")
      (node (ref "R28") (pin "2") (pinfunction "2_2") (pintype "passive"))
      (node (ref "S12") (pin "G") (pinfunction "GATE_G") (pintype "bidirectional"))
      (node (ref "U6") (pin "4") (pinfunction "Q4_4") (pintype "bidirectional"))
    )
    (net (code "348") (name "/OUT13") (class "Default")
      (node (ref "R27") (pin "2") (pinfunction "2_2") (pintype "passive"))
      (node (ref "S13") (pin "G") (pinfunction "GATE_G") (pintype "bidirectional"))
      (node (ref "U6") (pin "5") (pinfunction "Q5_5") (pintype "bidirectional"))
    )
    (net (code "349") (name "/OUT14") (class "Default")
      (node (ref "R30") (pin "2") (pinfunction "2_2") (pintype "passive"))
      (node (ref "S14") (pin "G") (pinfunction "GATE_G") (pintype "bidirectional"))
      (node (ref "U6") (pin "6") (pinfunction "Q6_6") (pintype "bidirectional"))
    )
    (net (code "350") (name "/OUT15") (class "Default")
      (node (ref "R29") (pin "2") (pinfunction "2_2") (pintype "passive"))
      (node (ref "S15") (pin "G") (pinfunction "GATE_G") (pintype "bidirectional"))
      (node (ref "U6") (pin "7") (pinfunction "Q7_7") (pintype "bidirectional"))
    )
    (net (code "351") (name "/OUT16") (class "Default")
      (node (ref "R32") (pin "2") (pinfunction "2_2") (pintype "passive"))
      (node (ref "S16") (pin "G") (pinfunction "GATE_G") (pintype "bidirectional"))
      (node (ref "U7") (pin "15") (pinfunction "Q0_15") (pintype "bidirectional"))
    )
    (net (code "352") (name "/OUT17") (class "Default")
      (node (ref "R31") (pin "2") (pinfunction "2_2") (pintype "passive"))
      (node (ref "S17") (pin "G") (pinfunction "GATE_G") (pintype "bidirectional"))
      (node (ref "U7") (pin "1") (pinfunction "Q1_1") (pintype "bidirectional"))
    )
    (net (code "353") (name "/OUT18") (class "Default")
      (node (ref "R34") (pin "2") (pinfunction "2_2") (pintype "passive"))
      (node (ref "S18") (pin "G") (pinfunction "GATE_G") (pintype "bidirectional"))
      (node (ref "U7") (pin "2") (pinfunction "Q2_2") (pintype "bidirectional"))
    )
    (net (code "354") (name "/OUT19") (class "Default")
      (node (ref "R33") (pin "2") (pinfunction "2_2") (pintype "passive"))
      (node (ref "S19") (pin "G") (pinfunction "GATE_G") (pintype "bidirectional"))
      (node (ref "U7") (pin "3") (pinfunction "Q3_3") (pintype "bidirectional"))
    )
    (net (code "355") (name "/OUT20") (class "Default")
      (node (ref "R36") (pin "2") (pinfunction "2_2") (pintype "passive"))
      (node (ref "S20") (pin "G") (pinfunction "GATE_G") (pintype "bidirectional"))
      (node (ref "U7") (pin "4") (pinfunction "Q4_4") (pintype "bidirectional"))
    )
    (net (code "356") (name "/OUT21") (class "Default")
      (node (ref "R35") (pin "2") (pinfunction "2_2") (pintype "passive"))
      (node (ref "S21") (pin "G") (pinfunction "GATE_G") (pintype "bidirectional"))
      (node (ref "U7") (pin "5") (pinfunction "Q5_5") (pintype "bidirectional"))
    )
    (net (code "357") (name "/OUT22") (class "Default")
      (node (ref "R38") (pin "2") (pinfunction "2_2") (pintype "passive"))
      (node (ref "S22") (pin "G") (pinfunction "GATE_G") (pintype "bidirectional"))
      (node (ref "U7") (pin "6") (pinfunction "Q6_6") (pintype "bidirectional"))
    )
    (net (code "358") (name "/OUT23") (class "Default")
      (node (ref "R37") (pin "2") (pinfunction "2_2") (pintype "passive"))
      (node (ref "S23") (pin "G") (pinfunction "GATE_G") (pintype "bidirectional"))
      (node (ref "U7") (pin "7") (pinfunction "Q7_7") (pintype "bidirectional"))
    )
    (net (code "359") (name "/OUT24") (class "Default")
      (node (ref "R40") (pin "2") (pinfunction "2_2") (pintype "passive"))
      (node (ref "S24") (pin "G") (pinfunction "GATE_G") (pintype "bidirectional"))
      (node (ref "U8") (pin "15") (pinfunction "Q0_15") (pintype "bidirectional"))
    )
    (net (code "360") (name "/OUT25") (class "Default")
      (node (ref "R39") (pin "2") (pinfunction "2_2") (pintype "passive"))
      (node (ref "S25") (pin "G") (pinfunction "GATE_G") (pintype "bidirectional"))
      (node (ref "U8") (pin "1") (pinfunction "Q1_1") (pintype "bidirectional"))
    )
    (net (code "361") (name "/OUT26") (class "Default")
      (node (ref "R42") (pin "2") (pinfunction "2_2") (pintype "passive"))
      (node (ref "S26") (pin "G") (pinfunction "GATE_G") (pintype "bidirectional"))
      (node (ref "U8") (pin "2") (pinfunction "Q2_2") (pintype "bidirectional"))
    )
    (net (code "362") (name "/OUT27") (class "Default")
      (node (ref "R41") (pin "2") (pinfunction "2_2") (pintype "passive"))
      (node (ref "S27") (pin "G") (pinfunction "GATE_G") (pintype "bidirectional"))
      (node (ref "U8") (pin "3") (pinfunction "Q3_3") (pintype "bidirectional"))
    )
    (net (code "363") (name "/OUT28") (class "Default")
      (node (ref "R44") (pin "2") (pinfunction "2_2") (pintype "passive"))
      (node (ref "S28") (pin "G") (pinfunction "GATE_G") (pintype "bidirectional"))
      (node (ref "U8") (pin "4") (pinfunction "Q4_4") (pintype "bidirectional"))
    )
    (net (code "364") (name "/OUT29") (class "Default")
      (node (ref "R43") (pin "2") (pinfunction "2_2") (pintype "passive"))
      (node (ref "S29") (pin "G") (pinfunction "GATE_G") (pintype "bidirectional"))
      (node (ref "U8") (pin "5") (pinfunction "Q5_5") (pintype "bidirectional"))
    )
    (net (code "365") (name "/OUT30") (class "Default")
      (node (ref "R46") (pin "2") (pinfunction "2_2") (pintype "passive"))
      (node (ref "S30") (pin "G") (pinfunction "GATE_G") (pintype "bidirectional"))
      (node (ref "U8") (pin "6") (pinfunction "Q6_6") (pintype "bidirectional"))
    )
    (net (code "366") (name "/OUT31") (class "Default")
      (node (ref "R45") (pin "2") (pinfunction "2_2") (pintype "passive"))
      (node (ref "S31") (pin "G") (pinfunction "GATE_G") (pintype "bidirectional"))
      (node (ref "U8") (pin "7") (pinfunction "Q7_7") (pintype "bidirectional"))
    )
    (net (code "367") (name "/OUTPUT_00") (class "Default")
      (node (ref "OUTPUT_BANK_0") (pin "P$1") (pinfunction "1_P$1") (pintype "bidirectional"))
      (node (ref "S0") (pin "D") (pinfunction "DRAIN_D") (pintype "bidirectional"))
    )
    (net (code "368") (name "/OUTPUT_01") (class "Default")
      (node (ref "OUTPUT_BANK_0") (pin "P$2") (pinfunction "2_P$2") (pintype "bidirectional"))
      (node (ref "S1") (pin "D") (pinfunction "DRAIN_D") (pintype "bidirectional"))
    )
    (net (code "369") (name "/OUTPUT_02") (class "Default")
      (node (ref "OUTPUT_BANK_0") (pin "P$3") (pinfunction "3_P$3") (pintype "bidirectional"))
      (node (ref "S2") (pin "D") (pinfunction "DRAIN_D") (pintype "bidirectional"))
    )
    (net (code "370") (name "/OUTPUT_03") (class "Default")
      (node (ref "OUTPUT_BANK_0") (pin "P$4") (pinfunction "4_P$4") (pintype "bidirectional"))
      (node (ref "S3") (pin "D") (pinfunction "DRAIN_D") (pintype "bidirectional"))
    )
    (net (code "371") (name "/OUTPUT_04") (class "Default")
      (node (ref "OUTPUT_BANK_0") (pin "P$5") (pinfunction "5_P$5") (pintype "bidirectional"))
      (node (ref "S4") (pin "D") (pinfunction "DRAIN_D") (pintype "bidirectional"))
    )
    (net (code "372") (name "/OUTPUT_05") (class "Default")
      (node (ref "OUTPUT_BANK_0") (pin "P$6") (pinfunction "6_P$6") (pintype "bidirectional"))
      (node (ref "S5") (pin "D") (pinfunction "DRAIN_D") (pintype "bidirectional"))
    )
    (net (code "373") (name "/OUTPUT_06") (class "Default")
      (node (ref "OUTPUT_BANK_0") (pin "P$7") (pinfunction "7_P$7") (pintype "bidirectional"))
      (node (ref "S6") (pin "D") (pinfunction "DRAIN_D") (pintype "bidirectional"))
    )
    (net (code "374") (name "/OUTPUT_07") (class "Default")
      (node (ref "OUTPUT_BANK_0") (pin "P$8") (pinfunction "8_P$8") (pintype "bidirectional"))
      (node (ref "S7") (pin "D") (pinfunction "DRAIN_D") (pintype "bidirectional"))
    )
    (net (code "375") (name "/OUTPUT_08") (class "Default")
      (node (ref "OUTPUT_BANK_1") (pin "P$1") (pinfunction "1_P$1") (pintype "bidirectional"))
      (node (ref "S8") (pin "D") (pinfunction "DRAIN_D") (pintype "bidirectional"))
    )
    (net (code "376") (name "/OUTPUT_09") (class "Default")
      (node (ref "OUTPUT_BANK_1") (pin "P$2") (pinfunction "2_P$2") (pintype "bidirectional"))
      (node (ref "S9") (pin "D") (pinfunction "DRAIN_D") (pintype "bidirectional"))
    )
    (net (code "377") (name "/OUTPUT_10") (class "Default")
      (node (ref "OUTPUT_BANK_1") (pin "P$3") (pinfunction "3_P$3") (pintype "bidirectional"))
      (node (ref "S10") (pin "D") (pinfunction "DRAIN_D") (pintype "bidirectional"))
    )
    (net (code "378") (name "/OUTPUT_11") (class "Default")
      (node (ref "OUTPUT_BANK_1") (pin "P$4") (pinfunction "4_P$4") (pintype "bidirectional"))
      (node (ref "S11") (pin "D") (pinfunction "DRAIN_D") (pintype "bidirectional"))
    )
    (net (code "379") (name "/OUTPUT_12") (class "Default")
      (node (ref "OUTPUT_BANK_1") (pin "P$5") (pinfunction "5_P$5") (pintype "bidirectional"))
      (node (ref "S12") (pin "D") (pinfunction "DRAIN_D") (pintype "bidirectional"))
    )
    (net (code "380") (name "/OUTPUT_13") (class "Default")
      (node (ref "OUTPUT_BANK_1") (pin "P$6") (pinfunction "6_P$6") (pintype "bidirectional"))
      (node (ref "S13") (pin "D") (pinfunction "DRAIN_D") (pintype "bidirectional"))
    )
    (net (code "381") (name "/OUTPUT_14") (class "Default")
      (node (ref "OUTPUT_BANK_1") (pin "P$7") (pinfunction "7_P$7") (pintype "bidirectional"))
      (node (ref "S14") (pin "D") (pinfunction "DRAIN_D") (pintype "bidirectional"))
    )
    (net (code "382") (name "/OUTPUT_15") (class "Default")
      (node (ref "OUTPUT_BANK_1") (pin "P$8") (pinfunction "8_P$8") (pintype "bidirectional"))
      (node (ref "S15") (pin "D") (pinfunction "DRAIN_D") (pintype "bidirectional"))
    )
    (net (code "383") (name "/OUTPUT_16") (class "Default")
      (node (ref "OUTPUT_BANK_2") (pin "P$1") (pinfunction "1_P$1") (pintype "bidirectional"))
      (node (ref "S16") (pin "D") (pinfunction "DRAIN_D") (pintype "bidirectional"))
    )
    (net (code "384") (name "/OUTPUT_17") (class "Default")
      (node (ref "OUTPUT_BANK_2") (pin "P$2") (pinfunction "2_P$2") (pintype "bidirectional"))
      (node (ref "S17") (pin "D") (pinfunction "DRAIN_D") (pintype "bidirectional"))
    )
    (net (code "385") (name "/OUTPUT_18") (class "Default")
      (node (ref "OUTPUT_BANK_2") (pin "P$3") (pinfunction "3_P$3") (pintype "bidirectional"))
      (node (ref "S18") (pin "D") (pinfunction "DRAIN_D") (pintype "bidirectional"))
    )
    (net (code "386") (name "/OUTPUT_19") (class "Default")
      (node (ref "OUTPUT_BANK_2") (pin "P$4") (pinfunction "4_P$4") (pintype "bidirectional"))
      (node (ref "S19") (pin "D") (pinfunction "DRAIN_D") (pintype "bidirectional"))
    )
    (net (code "387") (name "/OUTPUT_20") (class "Default")
      (node (ref "OUTPUT_BANK_2") (pin "P$5") (pinfunction "5_P$5") (pintype "bidirectional"))
      (node (ref "S20") (pin "D") (pinfunction "DRAIN_D") (pintype "bidirectional"))
    )
    (net (code "388") (name "/OUTPUT_21") (class "Default")
      (node (ref "OUTPUT_BANK_2") (pin "P$6") (pinfunction "6_P$6") (pintype "bidirectional"))
      (node (ref "S21") (pin "D") (pinfunction "DRAIN_D") (pintype "bidirectional"))
    )
    (net (code "389") (name "/OUTPUT_22") (class "Default")
      (node (ref "OUTPUT_BANK_2") (pin "P$7") (pinfunction "7_P$7") (pintype "bidirectional"))
      (node (ref "S22") (pin "D") (pinfunction "DRAIN_D") (pintype "bidirectional"))
    )
    (net (code "390") (name "/OUTPUT_23") (class "Default")
      (node (ref "OUTPUT_BANK_2") (pin "P$8") (pinfunction "8_P$8") (pintype "bidirectional"))
      (node (ref "S23") (pin "D") (pinfunction "DRAIN_D") (pintype "bidirectional"))
    )
    (net (code "391") (name "/OUTPUT_24") (class "Default")
      (node (ref "OUTPUT_BANK_3") (pin "P$1") (pinfunction "1_P$1") (pintype "bidirectional"))
      (node (ref "S24") (pin "D") (pinfunction "DRAIN_D") (pintype "bidirectional"))
    )
    (net (code "392") (name "/OUTPUT_25") (class "Default")
      (node (ref "OUTPUT_BANK_3") (pin "P$2") (pinfunction "2_P$2") (pintype "bidirectional"))
      (node (ref "S25") (pin "D") (pinfunction "DRAIN_D") (pintype "bidirectional"))
    )
    (net (code "393") (name "/OUTPUT_26") (class "Default")
      (node (ref "OUTPUT_BANK_3") (pin "P$3") (pinfunction "3_P$3") (pintype "bidirectional"))
      (node (ref "S26") (pin "D") (pinfunction "DRAIN_D") (pintype "bidirectional"))
    )
    (net (code "394") (name "/OUTPUT_27") (class "Default")
      (node (ref "OUTPUT_BANK_3") (pin "P$4") (pinfunction "4_P$4") (pintype "bidirectional"))
      (node (ref "S27") (pin "D") (pinfunction "DRAIN_D") (pintype "bidirectional"))
    )
    (net (code "395") (name "/OUTPUT_28") (class "Default")
      (node (ref "OUTPUT_BANK_3") (pin "P$5") (pinfunction "5_P$5") (pintype "bidirectional"))
      (node (ref "S28") (pin "D") (pinfunction "DRAIN_D") (pintype "bidirectional"))
    )
    (net (code "396") (name "/OUTPUT_29") (class "Default")
      (node (ref "OUTPUT_BANK_3") (pin "P$6") (pinfunction "6_P$6") (pintype "bidirectional"))
      (node (ref "S29") (pin "D") (pinfunction "DRAIN_D") (pintype "bidirectional"))
    )
    (net (code "397") (name "/OUTPUT_30") (class "Default")
      (node (ref "OUTPUT_BANK_3") (pin "P$7") (pinfunction "7_P$7") (pintype "bidirectional"))
      (node (ref "S30") (pin "D") (pinfunction "DRAIN_D") (pintype "bidirectional"))
    )
    (net (code "398") (name "/OUTPUT_31") (class "Default")
      (node (ref "OUTPUT_BANK_3") (pin "P$8") (pinfunction "8_P$8") (pintype "bidirectional"))
      (node (ref "S31") (pin "D") (pinfunction "DRAIN_D") (pintype "bidirectional"))
    )
    (net (code "399") (name "/OUTPUT_EN") (class "Default")
      (node (ref "R179") (pin "1") (pinfunction "1_1") (pintype "passive"))
      (node (ref "U39") (pin "13") (pinfunction "OE_13") (pintype "bidirectional"))
      (node (ref "U40") (pin "13") (pinfunction "OE_13") (pintype "bidirectional"))
      (node (ref "U41") (pin "13") (pinfunction "OE_13") (pintype "bidirectional"))
      (node (ref "U42") (pin "13") (pinfunction "OE_13") (pintype "bidirectional"))
      (node (ref "U5") (pin "13") (pinfunction "OE_13") (pintype "bidirectional"))
      (node (ref "U6") (pin "13") (pinfunction "OE_13") (pintype "bidirectional"))
      (node (ref "U7") (pin "13") (pinfunction "OE_13") (pintype "bidirectional"))
      (node (ref "U8") (pin "13") (pinfunction "OE_13") (pintype "bidirectional"))
      (node (ref "U81") (pin "5") (pinfunction "RST_5") (pintype "bidirectional"))
    )
    (net (code "400") (name "/PWR_EN") (class "Default")
      (node (ref "PC_POWER_SUPPLY") (pin "8") (pinfunction "8_8") (pintype "bidirectional"))
      (node (ref "SW2") (pin "2") (pinfunction "2_2") (pintype "bidirectional"))
    )
    (net (code "401") (name "/RES") (class "Default")
      (node (ref "C7") (pin "2") (pinfunction "2_2") (pintype "passive"))
      (node (ref "R176") (pin "1") (pinfunction "1_1") (pintype "passive"))
      (node (ref "RESET") (pin "2") (pinfunction "B_2") (pintype "bidirectional"))
      (node (ref "U1") (pin "7") (pinfunction "RES'_7") (pintype "bidirectional"))
    )
    (net (code "402") (name "/RTS") (class "Default")
      (node (ref "C7") (pin "1") (pinfunction "1_1") (pintype "passive"))
      (node (ref "U2") (pin "2") (pinfunction "RTS#_2") (pintype "bidirectional"))
    )
    (net (code "403") (name "/RW") (class "Default")
      (node (ref "R11") (pin "1") (pinfunction "1_1") (pintype "passive"))
      (node (ref "SD1") (pin "8") (pinfunction "RW_8") (pintype "bidirectional"))
    )
    (net (code "404") (name "/RX") (class "Default")
      (node (ref "U1") (pin "37") (pinfunction "P30_37") (pintype "bidirectional"))
      (node (ref "U2") (pin "4") (pinfunction "RXD_4") (pintype "bidirectional"))
    )
    (net (code "405") (name "/RXLED") (class "Default")
      (node (ref "R2") (pin "1") (pinfunction "1_1") (pintype "passive"))
      (node (ref "U2") (pin "14") (pinfunction "CBUS1_14") (pintype "bidirectional"))
    )
    (net (code "406") (name "/SCL") (class "Default")
      (node (ref "R4") (pin "1") (pinfunction "1_1") (pintype "passive"))
      (node (ref "U1") (pin "35") (pinfunction "P28_35") (pintype "bidirectional"))
      (node (ref "U4") (pin "6") (pinfunction "SCL_6") (pintype "bidirectional"))
      (node (ref "U75") (pin "4") (pinfunction "I/O2B_4") (pintype "bidirectional"))
      (node (ref "U83") (pin "1") (pinfunction "SCL_1") (pintype "bidirectional"))
    )
    (net (code "407") (name "/SCL_OUT") (class "Default")
      (node (ref "AUX") (pin "7") (pinfunction "7_7") (pintype "bidirectional"))
      (node (ref "U75") (pin "6") (pinfunction "I/O1B_6") (pintype "bidirectional"))
    )
    (net (code "408") (name "/SDA") (class "Default")
      (node (ref "R5") (pin "1") (pinfunction "1_1") (pintype "passive"))
      (node (ref "U1") (pin "36") (pinfunction "P29_36") (pintype "bidirectional"))
      (node (ref "U4") (pin "5") (pinfunction "SDA_5") (pintype "bidirectional"))
      (node (ref "U75") (pin "3") (pinfunction "I/O2A_3") (pintype "bidirectional"))
      (node (ref "U83") (pin "2") (pinfunction "SDA_2") (pintype "bidirectional"))
    )
    (net (code "409") (name "/SDA_OUT") (class "Default")
      (node (ref "AUX") (pin "6") (pinfunction "6_6") (pintype "bidirectional"))
      (node (ref "U75") (pin "1") (pinfunction "I/O1A_1") (pintype "bidirectional"))
    )
    (net (code "410") (name "/SD_CS") (class "Default")
      (node (ref "R10") (pin "1") (pinfunction "1_1") (pintype "passive"))
      (node (ref "SD1") (pin "7") (pinfunction "CS_7") (pintype "bidirectional"))
      (node (ref "U1") (pin "44") (pinfunction "P3_44") (pintype "bidirectional"))
    )
    (net (code "411") (name "/SD_DI") (class "Default")
      (node (ref "R9") (pin "1") (pinfunction "1_1") (pintype "passive"))
      (node (ref "SD1") (pin "6") (pinfunction "DI_6") (pintype "bidirectional"))
      (node (ref "U1") (pin "43") (pinfunction "P2_43") (pintype "bidirectional"))
    )
    (net (code "412") (name "/SD_DO") (class "Default")
      (node (ref "R7") (pin "1") (pinfunction "1_1") (pintype "passive"))
      (node (ref "SD1") (pin "2") (pinfunction "D0_2") (pintype "bidirectional"))
      (node (ref "U1") (pin "41") (pinfunction "P0_41") (pintype "bidirectional"))
    )
    (net (code "413") (name "/SD_SCLK") (class "Default")
      (node (ref "R8") (pin "1") (pinfunction "1_1") (pintype "passive"))
      (node (ref "SD1") (pin "4") (pinfunction "SCLK_4") (pintype "bidirectional"))
      (node (ref "U1") (pin "42") (pinfunction "P1_42") (pintype "bidirectional"))
    )
    (net (code "414") (name "/SEG0") (class "Default")
      (node (ref "SEG1") (pin "10") (pinfunction "A_10") (pintype "bidirectional"))
      (node (ref "U40") (pin "15") (pinfunction "Q0_15") (pintype "bidirectional"))
    )
    (net (code "415") (name "/SEG1") (class "Default")
      (node (ref "SEG1") (pin "9") (pinfunction "B_9") (pintype "bidirectional"))
      (node (ref "U40") (pin "1") (pinfunction "Q1_1") (pintype "bidirectional"))
    )
    (net (code "416") (name "/SEG2") (class "Default")
      (node (ref "SEG1") (pin "8") (pinfunction "C_8") (pintype "bidirectional"))
      (node (ref "U40") (pin "3") (pinfunction "Q3_3") (pintype "bidirectional"))
    )
    (net (code "417") (name "/SEG3") (class "Default")
      (node (ref "SEG1") (pin "5") (pinfunction "D_5") (pintype "bidirectional"))
      (node (ref "U40") (pin "7") (pinfunction "Q7_7") (pintype "bidirectional"))
    )
    (net (code "418") (name "/SEG4") (class "Default")
      (node (ref "SEG1") (pin "4") (pinfunction "E_4") (pintype "bidirectional"))
      (node (ref "U40") (pin "6") (pinfunction "Q6_6") (pintype "bidirectional"))
    )
    (net (code "419") (name "/SEG5") (class "Default")
      (node (ref "SEG1") (pin "2") (pinfunction "F_2") (pintype "bidirectional"))
      (node (ref "U40") (pin "4") (pinfunction "Q4_4") (pintype "bidirectional"))
    )
    (net (code "420") (name "/SEG6") (class "Default")
      (node (ref "SEG1") (pin "3") (pinfunction "G_3") (pintype "bidirectional"))
      (node (ref "U40") (pin "5") (pinfunction "Q5_5") (pintype "bidirectional"))
    )
    (net (code "421") (name "/SEG7") (class "Default")
      (node (ref "SEG1") (pin "7") (pinfunction "DP_7") (pintype "bidirectional"))
      (node (ref "U40") (pin "2") (pinfunction "Q2_2") (pintype "bidirectional"))
    )
    (net (code "422") (name "/SEG8") (class "Default")
      (node (ref "SEG2") (pin "10") (pinfunction "A_10") (pintype "bidirectional"))
      (node (ref "U41") (pin "15") (pinfunction "Q0_15") (pintype "bidirectional"))
    )
    (net (code "423") (name "/SEG9") (class "Default")
      (node (ref "SEG2") (pin "9") (pinfunction "B_9") (pintype "bidirectional"))
      (node (ref "U41") (pin "1") (pinfunction "Q1_1") (pintype "bidirectional"))
    )
    (net (code "424") (name "/SEG10") (class "Default")
      (node (ref "SEG2") (pin "8") (pinfunction "C_8") (pintype "bidirectional"))
      (node (ref "U41") (pin "3") (pinfunction "Q3_3") (pintype "bidirectional"))
    )
    (net (code "425") (name "/SEG11") (class "Default")
      (node (ref "SEG2") (pin "5") (pinfunction "D_5") (pintype "bidirectional"))
      (node (ref "U41") (pin "7") (pinfunction "Q7_7") (pintype "bidirectional"))
    )
    (net (code "426") (name "/SEG12") (class "Default")
      (node (ref "SEG2") (pin "4") (pinfunction "E_4") (pintype "bidirectional"))
      (node (ref "U41") (pin "6") (pinfunction "Q6_6") (pintype "bidirectional"))
    )
    (net (code "427") (name "/SEG13") (class "Default")
      (node (ref "SEG2") (pin "2") (pinfunction "F_2") (pintype "bidirectional"))
      (node (ref "U41") (pin "4") (pinfunction "Q4_4") (pintype "bidirectional"))
    )
    (net (code "428") (name "/SEG14") (class "Default")
      (node (ref "SEG2") (pin "3") (pinfunction "G_3") (pintype "bidirectional"))
      (node (ref "U41") (pin "5") (pinfunction "Q5_5") (pintype "bidirectional"))
    )
    (net (code "429") (name "/SEG15") (class "Default")
      (node (ref "SEG2") (pin "7") (pinfunction "DP_7") (pintype "bidirectional"))
      (node (ref "U41") (pin "2") (pinfunction "Q2_2") (pintype "bidirectional"))
    )
    (net (code "430") (name "/SEG16") (class "Default")
      (node (ref "SEG3") (pin "10") (pinfunction "A_10") (pintype "bidirectional"))
      (node (ref "U42") (pin "15") (pinfunction "Q0_15") (pintype "bidirectional"))
    )
    (net (code "431") (name "/SEG17") (class "Default")
      (node (ref "SEG3") (pin "9") (pinfunction "B_9") (pintype "bidirectional"))
      (node (ref "U42") (pin "1") (pinfunction "Q1_1") (pintype "bidirectional"))
    )
    (net (code "432") (name "/SEG18") (class "Default")
      (node (ref "SEG3") (pin "8") (pinfunction "C_8") (pintype "bidirectional"))
      (node (ref "U42") (pin "3") (pinfunction "Q3_3") (pintype "bidirectional"))
    )
    (net (code "433") (name "/SEG19") (class "Default")
      (node (ref "SEG3") (pin "5") (pinfunction "D_5") (pintype "bidirectional"))
      (node (ref "U42") (pin "7") (pinfunction "Q7_7") (pintype "bidirectional"))
    )
    (net (code "434") (name "/SEG20") (class "Default")
      (node (ref "SEG3") (pin "4") (pinfunction "E_4") (pintype "bidirectional"))
      (node (ref "U42") (pin "6") (pinfunction "Q6_6") (pintype "bidirectional"))
    )
    (net (code "435") (name "/SEG21") (class "Default")
      (node (ref "SEG3") (pin "2") (pinfunction "F_2") (pintype "bidirectional"))
      (node (ref "U42") (pin "4") (pinfunction "Q4_4") (pintype "bidirectional"))
    )
    (net (code "436") (name "/SEG22") (class "Default")
      (node (ref "SEG3") (pin "3") (pinfunction "G_3") (pintype "bidirectional"))
      (node (ref "U42") (pin "5") (pinfunction "Q5_5") (pintype "bidirectional"))
    )
    (net (code "437") (name "/SERVO_0") (class "Default")
      (node (ref "SERVO_0") (pin "1") (pinfunction "1_1") (pintype "passive"))
      (node (ref "U39") (pin "15") (pinfunction "Q0_15") (pintype "bidirectional"))
    )
    (net (code "438") (name "/SERVO_1") (class "Default")
      (node (ref "SERVO_1") (pin "1") (pinfunction "1_1") (pintype "passive"))
      (node (ref "U39") (pin "1") (pinfunction "Q1_1") (pintype "bidirectional"))
    )
    (net (code "439") (name "/SERVO_2") (class "Default")
      (node (ref "SERVO_2") (pin "1") (pinfunction "1_1") (pintype "passive"))
      (node (ref "U39") (pin "2") (pinfunction "Q2_2") (pintype "bidirectional"))
    )
    (net (code "440") (name "/SERVO_3") (class "Default")
      (node (ref "SERVO_3") (pin "1") (pinfunction "1_1") (pintype "passive"))
      (node (ref "U39") (pin "3") (pinfunction "Q3_3") (pintype "bidirectional"))
    )
    (net (code "441") (name "/SERVO_4") (class "Default")
      (node (ref "SERVO_4") (pin "1") (pinfunction "1_1") (pintype "passive"))
      (node (ref "U39") (pin "4") (pinfunction "Q4_4") (pintype "bidirectional"))
    )
    (net (code "442") (name "/SERVO_5") (class "Default")
      (node (ref "SERVO_5") (pin "1") (pinfunction "1_1") (pintype "passive"))
      (node (ref "U39") (pin "5") (pinfunction "Q5_5") (pintype "bidirectional"))
    )
    (net (code "443") (name "/SERVO_6") (class "Default")
      (node (ref "SERVO_6") (pin "1") (pinfunction "1_1") (pintype "passive"))
      (node (ref "U39") (pin "6") (pinfunction "Q6_6") (pintype "bidirectional"))
    )
    (net (code "444") (name "/SERVO_7") (class "Default")
      (node (ref "SERVO_7") (pin "1") (pinfunction "1_1") (pintype "passive"))
      (node (ref "U39") (pin "7") (pinfunction "Q7_7") (pintype "bidirectional"))
    )
    (net (code "445") (name "/SERVO_EXT") (class "Default")
      (node (ref "J36") (pin "2") (pinfunction "2_2") (pintype "bidirectional"))
      (node (ref "SERVO_EXT_PWR") (pin "P$2") (pinfunction "2_P$2") (pintype "passive"))
    )
    (net (code "446") (name "/SERVO_PWR") (class "Default")
      (node (ref "C65") (pin "POS") (pinfunction "POS_POS") (pintype "bidirectional"))
      (node (ref "J36") (pin "OUT") (pinfunction "OUT_OUT") (pintype "bidirectional"))
      (node (ref "SERVO_0") (pin "2") (pinfunction "2_2") (pintype "passive"))
      (node (ref "SERVO_1") (pin "2") (pinfunction "2_2") (pintype "passive"))
      (node (ref "SERVO_2") (pin "2") (pinfunction "2_2") (pintype "passive"))
      (node (ref "SERVO_3") (pin "2") (pinfunction "2_2") (pintype "passive"))
      (node (ref "SERVO_4") (pin "2") (pinfunction "2_2") (pintype "passive"))
      (node (ref "SERVO_5") (pin "2") (pinfunction "2_2") (pintype "passive"))
      (node (ref "SERVO_6") (pin "2") (pinfunction "2_2") (pintype "passive"))
      (node (ref "SERVO_7") (pin "2") (pinfunction "2_2") (pintype "passive"))
    )
    (net (code "447") (name "/SIO_0") (class "Default")
      (node (ref "U1") (pin "19") (pinfunction "P16_19") (pintype "bidirectional"))
      (node (ref "U36") (pin "5") (pinfunction "SI/SIO0_5") (pintype "bidirectional"))
    )
    (net (code "448") (name "/SIO_1") (class "Default")
      (node (ref "U1") (pin "20") (pinfunction "P17_20") (pintype "bidirectional"))
      (node (ref "U36") (pin "2") (pinfunction "SO/SIO1_2") (pintype "bidirectional"))
    )
    (net (code "449") (name "/SIO_2") (class "Default")
      (node (ref "U1") (pin "21") (pinfunction "P18_21") (pintype "bidirectional"))
      (node (ref "U36") (pin "3") (pinfunction "SIO2_3") (pintype "bidirectional"))
    )
    (net (code "450") (name "/SIO_3") (class "Default")
      (node (ref "U1") (pin "22") (pinfunction "P19_22") (pintype "bidirectional"))
      (node (ref "U36") (pin "7") (pinfunction "SIO3_7") (pintype "bidirectional"))
    )
    (net (code "451") (name "/SIO_4") (class "Default")
      (node (ref "U1") (pin "23") (pinfunction "P20_23") (pintype "bidirectional"))
      (node (ref "U37") (pin "5") (pinfunction "SI/SIO0_5") (pintype "bidirectional"))
    )
    (net (code "452") (name "/SIO_5") (class "Default")
      (node (ref "U1") (pin "24") (pinfunction "P21_24") (pintype "bidirectional"))
      (node (ref "U37") (pin "2") (pinfunction "SO/SIO1_2") (pintype "bidirectional"))
    )
    (net (code "453") (name "/SIO_6") (class "Default")
      (node (ref "U1") (pin "25") (pinfunction "P22_25") (pintype "bidirectional"))
      (node (ref "U37") (pin "3") (pinfunction "SIO2_3") (pintype "bidirectional"))
    )
    (net (code "454") (name "/SIO_7") (class "Default")
      (node (ref "U1") (pin "26") (pinfunction "P23_26") (pintype "bidirectional"))
      (node (ref "U37") (pin "7") (pinfunction "SIO3_7") (pintype "bidirectional"))
    )
    (net (code "455") (name "/SOLENOID_GND") (class "Default")
      (node (ref "C62") (pin "N") (pinfunction "NEG_N") (pintype "bidirectional"))
      (node (ref "C63") (pin "N") (pinfunction "NEG_N") (pintype "bidirectional"))
      (node (ref "C64") (pin "N") (pinfunction "NEG_N") (pintype "bidirectional"))
      (node (ref "R182") (pin "1") (pinfunction "1_1") (pintype "passive"))
      (node (ref "R183") (pin "1") (pinfunction "1_1") (pintype "passive"))
      (node (ref "S0") (pin "S") (pinfunction "SOURCE_S") (pintype "bidirectional"))
      (node (ref "S1") (pin "S") (pinfunction "SOURCE_S") (pintype "bidirectional"))
      (node (ref "S10") (pin "S") (pinfunction "SOURCE_S") (pintype "bidirectional"))
      (node (ref "S11") (pin "S") (pinfunction "SOURCE_S") (pintype "bidirectional"))
      (node (ref "S12") (pin "S") (pinfunction "SOURCE_S") (pintype "bidirectional"))
      (node (ref "S13") (pin "S") (pinfunction "SOURCE_S") (pintype "bidirectional"))
      (node (ref "S14") (pin "S") (pinfunction "SOURCE_S") (pintype "bidirectional"))
      (node (ref "S15") (pin "S") (pinfunction "SOURCE_S") (pintype "bidirectional"))
      (node (ref "S16") (pin "S") (pinfunction "SOURCE_S") (pintype "bidirectional"))
      (node (ref "S17") (pin "S") (pinfunction "SOURCE_S") (pintype "bidirectional"))
      (node (ref "S18") (pin "S") (pinfunction "SOURCE_S") (pintype "bidirectional"))
      (node (ref "S19") (pin "S") (pinfunction "SOURCE_S") (pintype "bidirectional"))
      (node (ref "S2") (pin "S") (pinfunction "SOURCE_S") (pintype "bidirectional"))
      (node (ref "S20") (pin "S") (pinfunction "SOURCE_S") (pintype "bidirectional"))
      (node (ref "S21") (pin "S") (pinfunction "SOURCE_S") (pintype "bidirectional"))
      (node (ref "S22") (pin "S") (pinfunction "SOURCE_S") (pintype "bidirectional"))
      (node (ref "S23") (pin "S") (pinfunction "SOURCE_S") (pintype "bidirectional"))
      (node (ref "S24") (pin "S") (pinfunction "SOURCE_S") (pintype "bidirectional"))
      (node (ref "S25") (pin "S") (pinfunction "SOURCE_S") (pintype "bidirectional"))
      (node (ref "S26") (pin "S") (pinfunction "SOURCE_S") (pintype "bidirectional"))
      (node (ref "S27") (pin "S") (pinfunction "SOURCE_S") (pintype "bidirectional"))
      (node (ref "S28") (pin "S") (pinfunction "SOURCE_S") (pintype "bidirectional"))
      (node (ref "S29") (pin "S") (pinfunction "SOURCE_S") (pintype "bidirectional"))
      (node (ref "S3") (pin "S") (pinfunction "SOURCE_S") (pintype "bidirectional"))
      (node (ref "S30") (pin "S") (pinfunction "SOURCE_S") (pintype "bidirectional"))
      (node (ref "S31") (pin "S") (pinfunction "SOURCE_S") (pintype "bidirectional"))
      (node (ref "S4") (pin "S") (pinfunction "SOURCE_S") (pintype "bidirectional"))
      (node (ref "S5") (pin "S") (pinfunction "SOURCE_S") (pintype "bidirectional"))
      (node (ref "S6") (pin "S") (pinfunction "SOURCE_S") (pintype "bidirectional"))
      (node (ref "S7") (pin "S") (pinfunction "SOURCE_S") (pintype "bidirectional"))
      (node (ref "S8") (pin "S") (pinfunction "SOURCE_S") (pintype "bidirectional"))
      (node (ref "S9") (pin "S") (pinfunction "SOURCE_S") (pintype "bidirectional"))
      (node (ref "SOLENOID_PWR") (pin "2") (pinfunction "2_2") (pintype "passive"))
      (node (ref "SOLENOID_PWR") (pin "3") (pinfunction "3_3") (pintype "passive"))
    )
    (net (code "456") (name "/SOLENOID_PWR") (class "Default")
      (node (ref "C62") (pin "P") (pinfunction "POS_P") (pintype "bidirectional"))
      (node (ref "C63") (pin "P") (pinfunction "POS_P") (pintype "bidirectional"))
      (node (ref "C64") (pin "P") (pinfunction "POS_P") (pintype "bidirectional"))
      (node (ref "EM1") (pin "1") (pinfunction "1_1") (pintype "bidirectional"))
      (node (ref "OUTPUT_BANK_0") (pin "P$9") (pinfunction "9_P$9") (pintype "bidirectional"))
      (node (ref "OUTPUT_BANK_1") (pin "P$9") (pinfunction "9_P$9") (pintype "bidirectional"))
      (node (ref "OUTPUT_BANK_2") (pin "P$9") (pinfunction "9_P$9") (pintype "bidirectional"))
      (node (ref "OUTPUT_BANK_3") (pin "P$9") (pinfunction "9_P$9") (pintype "bidirectional"))
    )
    (net (code "457") (name "/SOLENOID_PWR_IN") (class "Default")
      (node (ref "FUSE") (pin "2A") (pinfunction "P$2_2A") (pintype "bidirectional"))
      (node (ref "FUSE") (pin "2B") (pinfunction "P$2_2B") (pintype "bidirectional"))
      (node (ref "SOLENOID_PWR") (pin "1") (pinfunction "1_1") (pintype "passive"))
      (node (ref "SOLENOID_PWR") (pin "4") (pinfunction "4_4") (pintype "passive"))
    )
    (net (code "458") (name "/SOL_PWR_RELAY") (class "Default")
      (node (ref "EM1") (pin "3") (pinfunction "3_3") (pintype "bidirectional"))
      (node (ref "FUSE") (pin "1A") (pinfunction "P$1_1A") (pintype "bidirectional"))
      (node (ref "FUSE") (pin "1B") (pinfunction "P$1_1B") (pintype "bidirectional"))
    )
    (net (code "459") (name "/SOL_PWR_RELAY_CTRL") (class "Default")
      (node (ref "R188") (pin "1") (pinfunction "1_1") (pintype "passive"))
      (node (ref "R189") (pin "1") (pinfunction "1_1") (pintype "passive"))
      (node (ref "SEG3") (pin "7") (pinfunction "DP_7") (pintype "bidirectional"))
      (node (ref "U42") (pin "2") (pinfunction "Q2_2") (pintype "bidirectional"))
    )
    (net (code "460") (name "/SRAM_CLK_0") (class "Default")
      (node (ref "U1") (pin "15") (pinfunction "P14_15") (pintype "bidirectional"))
      (node (ref "U36") (pin "6") (pinfunction "SCK_6") (pintype "bidirectional"))
    )
    (net (code "461") (name "/SRAM_CLK_1") (class "Default")
      (node (ref "U1") (pin "16") (pinfunction "P15_16") (pintype "bidirectional"))
      (node (ref "U37") (pin "6") (pinfunction "SCK_6") (pintype "bidirectional"))
    )
    (net (code "462") (name "/TX") (class "Default")
      (node (ref "U1") (pin "38") (pinfunction "P31_38") (pintype "bidirectional"))
      (node (ref "U2") (pin "1") (pinfunction "TXD_1") (pintype "bidirectional"))
    )
    (net (code "463") (name "/TXLED") (class "Default")
      (node (ref "R3") (pin "1") (pinfunction "1_1") (pintype "passive"))
      (node (ref "U2") (pin "7") (pinfunction "CBUS2_7") (pintype "bidirectional"))
    )
    (net (code "464") (name "/USBDM") (class "Default")
      (node (ref "R180") (pin "1") (pinfunction "1_1") (pintype "passive"))
      (node (ref "U2") (pin "9") (pinfunction "USBDM_9") (pintype "bidirectional"))
    )
    (net (code "465") (name "/USBDP") (class "Default")
      (node (ref "R181") (pin "1") (pinfunction "1_1") (pintype "passive"))
      (node (ref "U2") (pin "8") (pinfunction "USBDP_8") (pintype "bidirectional"))
    )
    (net (code "466") (name "/VBUS") (class "Default")
      (node (ref "C1") (pin "1") (pinfunction "1_1") (pintype "passive"))
      (node (ref "D1") (pin "A") (pinfunction "A_A") (pintype "passive"))
      (node (ref "D2") (pin "A") (pinfunction "A_A") (pintype "passive"))
      (node (ref "D3") (pin "A") (pinfunction "A_A") (pintype "passive"))
      (node (ref "U2") (pin "12") (pinfunction "VCC_12") (pintype "bidirectional"))
      (node (ref "U3") (pin "5") (pinfunction "VB_5") (pintype "bidirectional"))
      (node (ref "USB") (pin "1") (pinfunction "5V_1") (pintype "bidirectional"))
    )
    (net (code "467") (name "/V_LED") (class "Default")
      (node (ref "C66") (pin "2") (pinfunction "2_2") (pintype "passive"))
      (node (ref "C67") (pin "2") (pinfunction "2_2") (pintype "passive"))
      (node (ref "C68") (pin "2") (pinfunction "2_2") (pintype "passive"))
      (node (ref "C69") (pin "2") (pinfunction "2_2") (pintype "passive"))
      (node (ref "J35") (pin "OUT") (pinfunction "OUT_OUT") (pintype "bidirectional"))
      (node (ref "LIGHT_BANK_0") (pin "10") (pinfunction "10_10") (pintype "bidirectional"))
      (node (ref "LIGHT_BANK_1") (pin "10") (pinfunction "10_10") (pintype "bidirectional"))
      (node (ref "LIGHT_BANK_2") (pin "10") (pinfunction "10_10") (pintype "bidirectional"))
      (node (ref "LIGHT_BANK_3") (pin "10") (pinfunction "10_10") (pintype "bidirectional"))
      (node (ref "LIGHT_BANK_4") (pin "10") (pinfunction "10_10") (pintype "bidirectional"))
      (node (ref "LIGHT_BANK_5") (pin "10") (pinfunction "10_10") (pintype "bidirectional"))
      (node (ref "LIGHT_BANK_6") (pin "10") (pinfunction "10_10") (pintype "bidirectional"))
      (node (ref "LIGHT_BANK_7") (pin "10") (pinfunction "10_10") (pintype "bidirectional"))
    )
    (net (code "468") (name "/X0") (class "Default")
      (node (ref "U1") (pin "29") (pinfunction "X0_29") (pintype "bidirectional"))
      (node (ref "X1") (pin "1") (pinfunction "P$1_1") (pintype "bidirectional"))
    )
    (net (code "469") (name "/X1") (class "Default")
      (node (ref "U1") (pin "28") (pinfunction "X1_28") (pintype "bidirectional"))
      (node (ref "X1") (pin "3") (pinfunction "P$2_3") (pintype "bidirectional"))
    )
    (net (code "470") (name "Net-(C42-Pad2)") (class "Default")
      (node (ref "C42") (pin "2") (pinfunction "2_2") (pintype "passive"))
      (node (ref "C44") (pin "1") (pinfunction "1_1") (pintype "passive"))
      (node (ref "R177") (pin "2") (pinfunction "2_2") (pintype "passive"))
    )
    (net (code "471") (name "Net-(C43-Pad2)") (class "Default")
      (node (ref "C43") (pin "2") (pinfunction "2_2") (pintype "passive"))
      (node (ref "C45") (pin "2") (pinfunction "2_2") (pintype "passive"))
      (node (ref "R178") (pin "2") (pinfunction "2_2") (pintype "passive"))
    )
    (net (code "472") (name "Net-(D1-PadC)") (class "Default")
      (node (ref "D1") (pin "C") (pinfunction "C_C") (pintype "passive"))
      (node (ref "R1") (pin "2") (pinfunction "2_2") (pintype "passive"))
    )
    (net (code "473") (name "Net-(D2-PadC)") (class "Default")
      (node (ref "D2") (pin "C") (pinfunction "C_C") (pintype "passive"))
      (node (ref "R2") (pin "2") (pinfunction "2_2") (pintype "passive"))
    )
    (net (code "474") (name "Net-(D3-PadC)") (class "Default")
      (node (ref "D3") (pin "C") (pinfunction "C_C") (pintype "passive"))
      (node (ref "R3") (pin "2") (pinfunction "2_2") (pintype "passive"))
    )
    (net (code "475") (name "Net-(D4-PadA)") (class "Default")
      (node (ref "D4") (pin "A") (pinfunction "A_A") (pintype "passive"))
      (node (ref "R186") (pin "1") (pinfunction "1_1") (pintype "passive"))
    )
    (net (code "476") (name "Net-(D5-PadC)") (class "Default")
      (node (ref "D5") (pin "C") (pinfunction "C_C") (pintype "passive"))
      (node (ref "R187") (pin "2") (pinfunction "2_2") (pintype "passive"))
    )
    (net (code "477") (name "Net-(U3-I{slash}O2A)") (class "Default")
      (node (ref "R181") (pin "2") (pinfunction "2_2") (pintype "passive"))
      (node (ref "U3") (pin "3") (pinfunction "I/O2A_3") (pintype "bidirectional"))
    )
    (net (code "478") (name "Net-(U3-I{slash}O2B)") (class "Default")
      (node (ref "R180") (pin "2") (pinfunction "2_2") (pintype "passive"))
      (node (ref "U3") (pin "4") (pinfunction "I/O2B_4") (pintype "bidirectional"))
    )
    (net (code "479") (name "Net-(U84-BASE)") (class "Default")
      (node (ref "R188") (pin "2") (pinfunction "2_2") (pintype "passive"))
      (node (ref "U84") (pin "1") (pinfunction "BASE_1") (pintype "bidirectional"))
    )
    (net (code "480") (name "Net-(U84-COLLECTOR)") (class "Default")
      (node (ref "D5") (pin "A") (pinfunction "A_A") (pintype "passive"))
      (node (ref "EM1") (pin "5") (pinfunction "5_5") (pintype "bidirectional"))
      (node (ref "U84") (pin "3") (pinfunction "COLLECTOR_3") (pintype "bidirectional"))
    )
    (net (code "481") (name "unconnected-(DMD_CONN-Pad7)") (class "Default")
      (node (ref "DMD_CONN") (pin "7") (pinfunction "7_7") (pintype "bidirectional"))
    )
    (net (code "482") (name "unconnected-(EM1-Pad4)") (class "Default")
      (node (ref "EM1") (pin "4") (pinfunction "4_4") (pintype "bidirectional"))
    )
    (net (code "483") (name "unconnected-(PC_POWER_SUPPLY-Pad15)") (class "Default")
      (node (ref "PC_POWER_SUPPLY") (pin "15") (pinfunction "15_15") (pintype "bidirectional"))
    )
    (net (code "484") (name "unconnected-(PC_POWER_SUPPLY-Pad17)") (class "Default")
      (node (ref "PC_POWER_SUPPLY") (pin "17") (pinfunction "17_17") (pintype "bidirectional"))
    )
    (net (code "485") (name "unconnected-(SW2-Pad3)") (class "Default")
      (node (ref "SW2") (pin "3") (pinfunction "3_3") (pintype "bidirectional"))
    )
    (net (code "486") (name "unconnected-(U2-CBUS0-Pad15)") (class "Default")
      (node (ref "U2") (pin "15") (pinfunction "CBUS0_15") (pintype "bidirectional"))
    )
    (net (code "487") (name "unconnected-(U2-CBUS3-Pad16)") (class "Default")
      (node (ref "U2") (pin "16") (pinfunction "CBUS3_16") (pintype "bidirectional"))
    )
    (net (code "488") (name "unconnected-(U2-CTS#-Pad6)") (class "Default")
      (node (ref "U2") (pin "6") (pinfunction "CTS#_6") (pintype "bidirectional"))
    )
    (net (code "489") (name "unconnected-(U9-QH'-Pad7)") (class "Default")
      (node (ref "U9") (pin "7") (pinfunction "QH'_7") (pintype "bidirectional"))
    )
    (net (code "490") (name "unconnected-(U10-QH'-Pad7)") (class "Default")
      (node (ref "U10") (pin "7") (pinfunction "QH'_7") (pintype "bidirectional"))
    )
    (net (code "491") (name "unconnected-(U11-QH'-Pad7)") (class "Default")
      (node (ref "U11") (pin "7") (pinfunction "QH'_7") (pintype "bidirectional"))
    )
    (net (code "492") (name "unconnected-(U12-QH'-Pad7)") (class "Default")
      (node (ref "U12") (pin "7") (pinfunction "QH'_7") (pintype "bidirectional"))
    )
    (net (code "493") (name "unconnected-(U13-QH'-Pad7)") (class "Default")
      (node (ref "U13") (pin "7") (pinfunction "QH'_7") (pintype "bidirectional"))
    )
    (net (code "494") (name "unconnected-(U14-QH'-Pad7)") (class "Default")
      (node (ref "U14") (pin "7") (pinfunction "QH'_7") (pintype "bidirectional"))
    )
    (net (code "495") (name "unconnected-(U15-QH'-Pad7)") (class "Default")
      (node (ref "U15") (pin "7") (pinfunction "QH'_7") (pintype "bidirectional"))
    )
    (net (code "496") (name "unconnected-(U16-QH'-Pad7)") (class "Default")
      (node (ref "U16") (pin "7") (pinfunction "QH'_7") (pintype "bidirectional"))
    )
    (net (code "497") (name "unconnected-(U81-{slash}PB-Pad1)") (class "Default")
      (node (ref "U81") (pin "1") (pinfunction "/PB_1") (pintype "bidirectional"))
    )
    (net (code "498") (name "unconnected-(U81-{slash}RST-Pad6)") (class "Default")
      (node (ref "U81") (pin "6") (pinfunction "/RST_6") (pintype "bidirectional"))
    )
    (net (code "499") (name "unconnected-(USB-ID-Pad4)") (class "Default")
      (node (ref "USB") (pin "4") (pinfunction "ID_4") (pintype "bidirectional"))
    )
  )
)
